# BUSBAR_18650_12S.net
KiCad netlist of a schematic drawn in Altium Designer
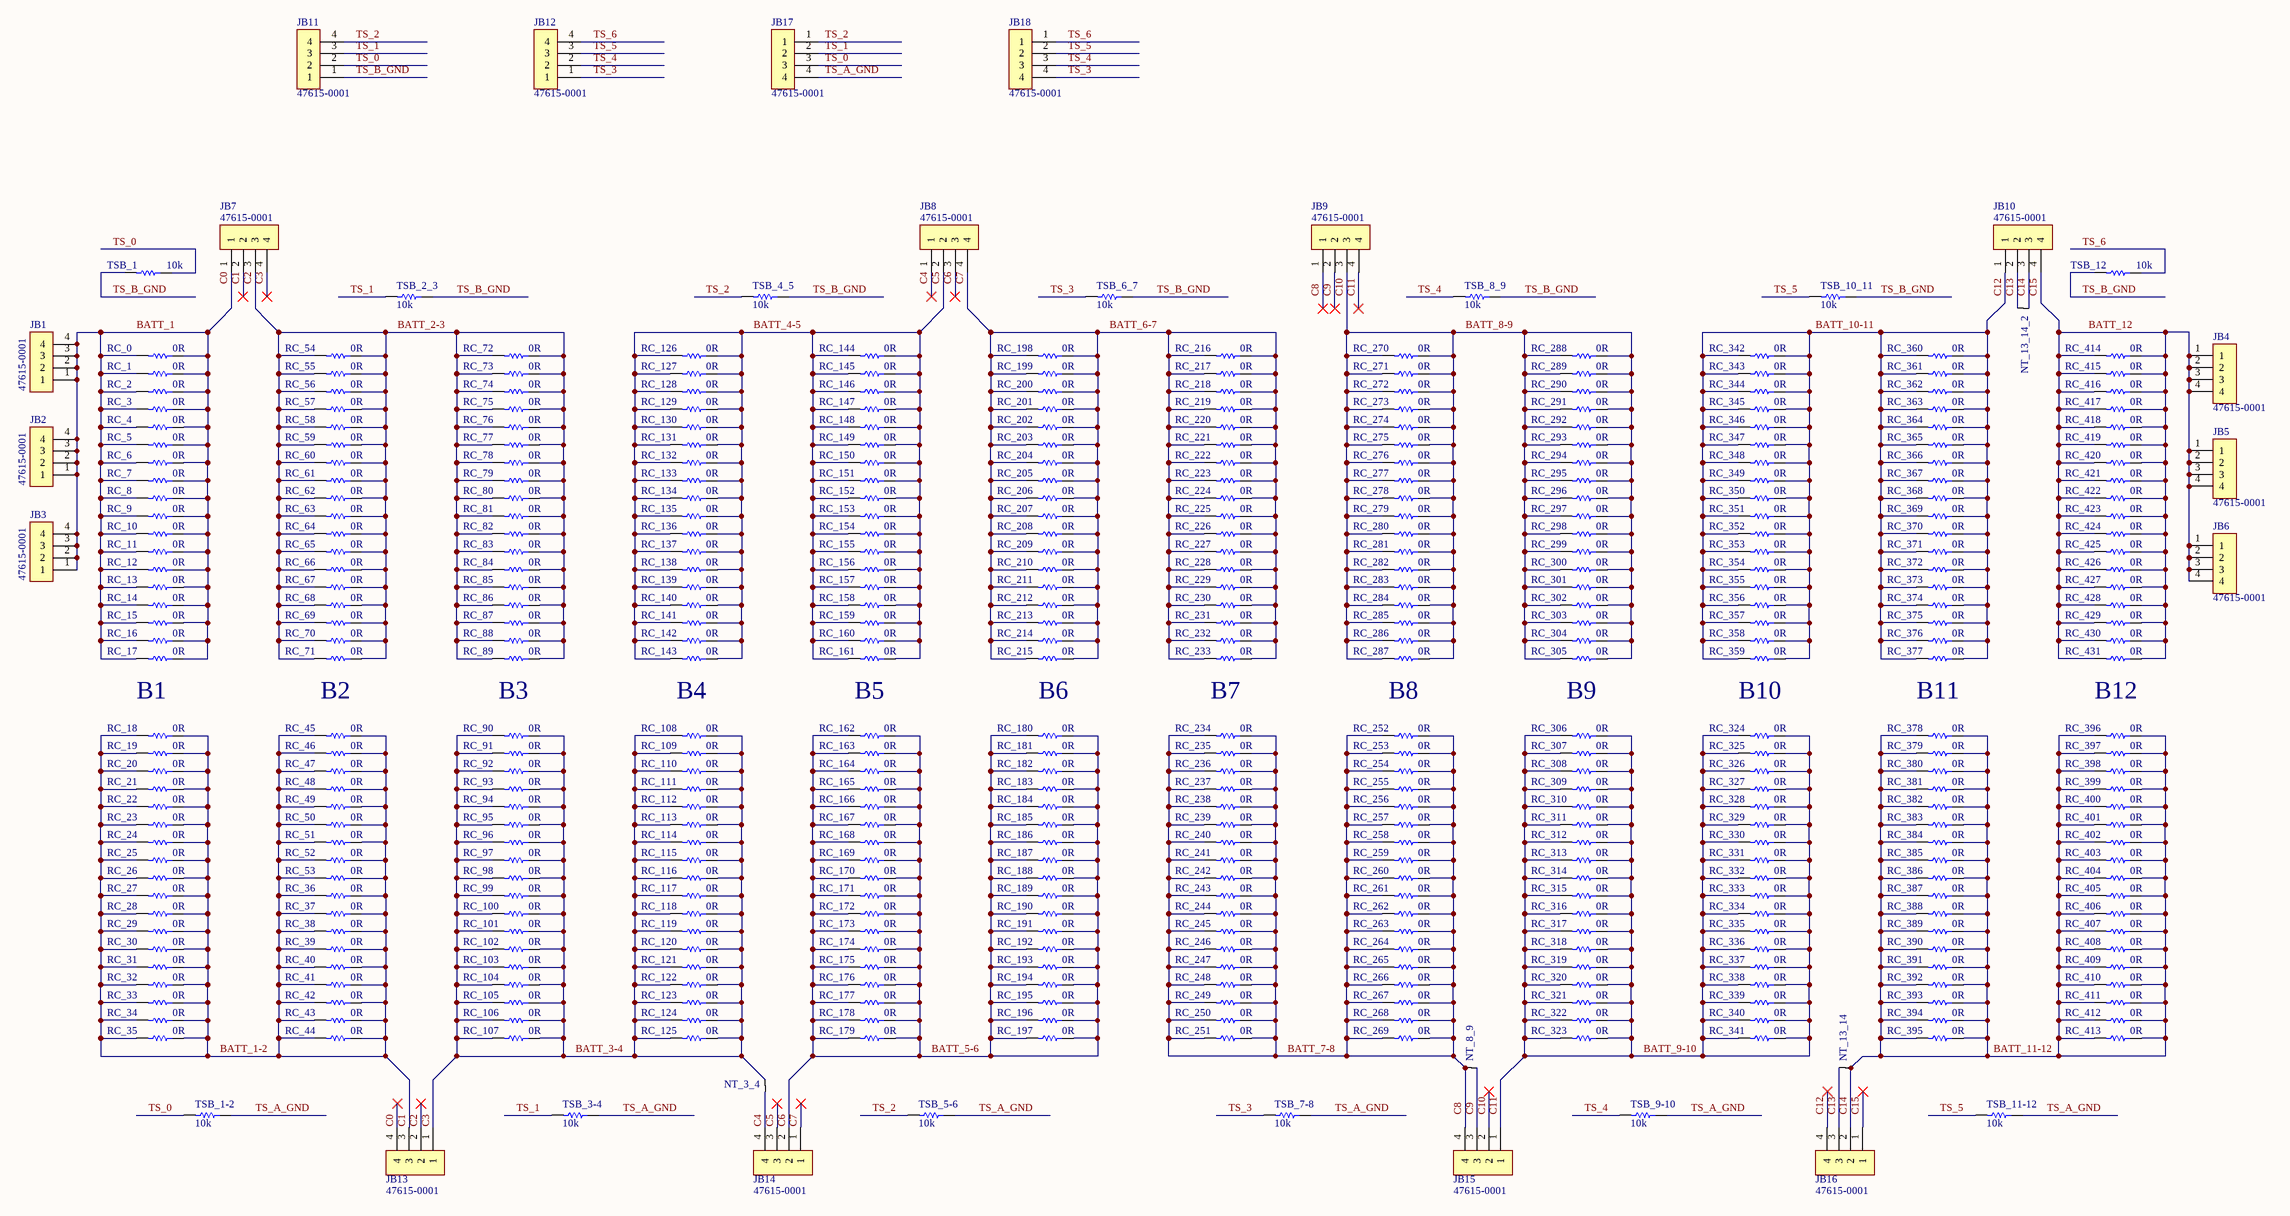
[diagram p0: BUSBAR_18650_12S.SchDoc]

(export (version "E")
  (design (tool "Eeschema 10.0.6"))
  (components
    (comp (ref "JB1")
      (value "47615-0001")
      (footprint "47615-0001")
      (description "Battery Spring x4")
      (libsource (lib "") (part "47615-0001_2"))
    )
    (comp (ref "JB2")
      (value "47615-0001")
      (footprint "47615-0001")
      (description "Battery Spring x4")
      (libsource (lib "") (part "47615-0001_2"))
    )
    (comp (ref "JB3")
      (value "47615-0001")
      (footprint "47615-0001")
      (description "Battery Spring x4")
      (libsource (lib "") (part "47615-0001_2"))
    )
    (comp (ref "JB4")
      (value "47615-0001")
      (footprint "47615-0001")
      (description "Battery Spring x4")
      (libsource (lib "") (part "47615-0001_3"))
    )
    (comp (ref "JB5")
      (value "47615-0001")
      (footprint "47615-0001")
      (description "Battery Spring x4")
      (libsource (lib "") (part "47615-0001_3"))
    )
    (comp (ref "JB6")
      (value "47615-0001")
      (footprint "47615-0001")
      (description "Battery Spring x4")
      (libsource (lib "") (part "47615-0001_3"))
    )
    (comp (ref "JB7")
      (value "47615-0001")
      (footprint "47615-0001")
      (description "Battery Spring x4")
      (libsource (lib "") (part "47615-0001_1"))
    )
    (comp (ref "JB8")
      (value "47615-0001")
      (footprint "47615-0001")
      (description "Battery Spring x4")
      (libsource (lib "") (part "47615-0001_1"))
    )
    (comp (ref "JB9")
      (value "47615-0001")
      (footprint "47615-0001")
      (description "Battery Spring x4")
      (libsource (lib "") (part "47615-0001_1"))
    )
    (comp (ref "JB10")
      (value "47615-0001")
      (footprint "47615-0001")
      (description "Battery Spring x4")
      (libsource (lib "") (part "47615-0001_1"))
    )
    (comp (ref "JB11")
      (value "47615-0001")
      (footprint "47615-0001")
      (description "Battery Spring x4")
      (libsource (lib "") (part "47615-0001_2"))
    )
    (comp (ref "JB12")
      (value "47615-0001")
      (footprint "47615-0001")
      (description "Battery Spring x4")
      (libsource (lib "") (part "47615-0001_2"))
    )
    (comp (ref "JB13")
      (value "47615-0001")
      (footprint "47615-0001")
      (description "Battery Spring x4")
      (libsource (lib "J") (part "47615-0001"))
    )
    (comp (ref "JB14")
      (value "47615-0001")
      (footprint "47615-0001")
      (description "Battery Spring x4")
      (libsource (lib "J") (part "47615-0001"))
    )
    (comp (ref "JB15")
      (value "47615-0001")
      (footprint "47615-0001")
      (description "Battery Spring x4")
      (libsource (lib "J") (part "47615-0001"))
    )
    (comp (ref "JB16")
      (value "47615-0001")
      (footprint "47615-0001")
      (description "Battery Spring x4")
      (libsource (lib "J") (part "47615-0001"))
    )
    (comp (ref "JB17")
      (value "47615-0001")
      (footprint "47615-0001")
      (description "Battery Spring x4")
      (libsource (lib "J") (part "47615-0001"))
    )
    (comp (ref "JB18")
      (value "47615-0001")
      (footprint "47615-0001")
      (description "Battery Spring x4")
      (libsource (lib "J") (part "47615-0001"))
    )
    (comp (ref "NT_3_4")
      (value "0")
      (footprint "NET_TIE")
      (description "R - Net Tie")
      (libsource (lib "JLC_PCB") (part "NET_TIE"))
    )
    (comp (ref "NT_8_9")
      (value "0")
      (footprint "NET_TIE")
      (description "R - Net Tie")
      (libsource (lib "JLC_PCB") (part "NET_TIE"))
    )
    (comp (ref "NT_13_14")
      (value "0")
      (footprint "NET_TIE")
      (description "R - Net Tie")
      (libsource (lib "JLC_PCB") (part "NET_TIE"))
    )
    (comp (ref "NT_13_14_2")
      (value "0")
      (footprint "NET_TIE")
      (description "R - Net Tie")
      (libsource (lib "JLC_PCB") (part "NET_TIE"))
    )
    (comp (ref "RC_0")
      (value "0R")
      (footprint "R_0603")
      (description "R - RESISTOR - SMD - 0R - 1% - 0603")
      (fields (field (name "LCSC PART #") "C21189") (field (name "Comment") "0603WAF0000T5E"))
      (libsource (lib "JLC_PCB") (part "0603WAF0000T5E"))
    )
    (comp (ref "RC_1")
      (value "0R")
      (footprint "R_0603")
      (description "R - RESISTOR - SMD - 0R - 1% - 0603")
      (fields (field (name "LCSC PART #") "C21189") (field (name "Comment") "0603WAF0000T5E"))
      (libsource (lib "JLC_PCB") (part "0603WAF0000T5E"))
    )
    (comp (ref "RC_2")
      (value "0R")
      (footprint "R_0603")
      (description "R - RESISTOR - SMD - 0R - 1% - 0603")
      (fields (field (name "LCSC PART #") "C21189") (field (name "Comment") "0603WAF0000T5E"))
      (libsource (lib "JLC_PCB") (part "0603WAF0000T5E"))
    )
    (comp (ref "RC_3")
      (value "0R")
      (footprint "R_0603")
      (description "R - RESISTOR - SMD - 0R - 1% - 0603")
      (fields (field (name "LCSC PART #") "C21189") (field (name "Comment") "0603WAF0000T5E"))
      (libsource (lib "JLC_PCB") (part "0603WAF0000T5E"))
    )
    (comp (ref "RC_4")
      (value "0R")
      (footprint "R_0603")
      (description "R - RESISTOR - SMD - 0R - 1% - 0603")
      (fields (field (name "LCSC PART #") "C21189") (field (name "Comment") "0603WAF0000T5E"))
      (libsource (lib "JLC_PCB") (part "0603WAF0000T5E"))
    )
    (comp (ref "RC_5")
      (value "0R")
      (footprint "R_0603")
      (description "R - RESISTOR - SMD - 0R - 1% - 0603")
      (fields (field (name "LCSC PART #") "C21189") (field (name "Comment") "0603WAF0000T5E"))
      (libsource (lib "JLC_PCB") (part "0603WAF0000T5E"))
    )
    (comp (ref "RC_6")
      (value "0R")
      (footprint "R_0603")
      (description "R - RESISTOR - SMD - 0R - 1% - 0603")
      (fields (field (name "LCSC PART #") "C21189") (field (name "Comment") "0603WAF0000T5E"))
      (libsource (lib "JLC_PCB") (part "0603WAF0000T5E"))
    )
    (comp (ref "RC_7")
      (value "0R")
      (footprint "R_0603")
      (description "R - RESISTOR - SMD - 0R - 1% - 0603")
      (fields (field (name "LCSC PART #") "C21189") (field (name "Comment") "0603WAF0000T5E"))
      (libsource (lib "JLC_PCB") (part "0603WAF0000T5E"))
    )
    (comp (ref "RC_8")
      (value "0R")
      (footprint "R_0603")
      (description "R - RESISTOR - SMD - 0R - 1% - 0603")
      (fields (field (name "LCSC PART #") "C21189") (field (name "Comment") "0603WAF0000T5E"))
      (libsource (lib "JLC_PCB") (part "0603WAF0000T5E"))
    )
    (comp (ref "RC_9")
      (value "0R")
      (footprint "R_0603")
      (description "R - RESISTOR - SMD - 0R - 1% - 0603")
      (fields (field (name "LCSC PART #") "C21189") (field (name "Comment") "0603WAF0000T5E"))
      (libsource (lib "JLC_PCB") (part "0603WAF0000T5E"))
    )
    (comp (ref "RC_10")
      (value "0R")
      (footprint "R_0603")
      (description "R - RESISTOR - SMD - 0R - 1% - 0603")
      (fields (field (name "LCSC PART #") "C21189") (field (name "Comment") "0603WAF0000T5E"))
      (libsource (lib "JLC_PCB") (part "0603WAF0000T5E"))
    )
    (comp (ref "RC_11")
      (value "0R")
      (footprint "R_0603")
      (description "R - RESISTOR - SMD - 0R - 1% - 0603")
      (fields (field (name "LCSC PART #") "C21189") (field (name "Comment") "0603WAF0000T5E"))
      (libsource (lib "JLC_PCB") (part "0603WAF0000T5E"))
    )
    (comp (ref "RC_12")
      (value "0R")
      (footprint "R_0603")
      (description "R - RESISTOR - SMD - 0R - 1% - 0603")
      (fields (field (name "LCSC PART #") "C21189") (field (name "Comment") "0603WAF0000T5E"))
      (libsource (lib "JLC_PCB") (part "0603WAF0000T5E"))
    )
    (comp (ref "RC_13")
      (value "0R")
      (footprint "R_0603")
      (description "R - RESISTOR - SMD - 0R - 1% - 0603")
      (fields (field (name "LCSC PART #") "C21189") (field (name "Comment") "0603WAF0000T5E"))
      (libsource (lib "JLC_PCB") (part "0603WAF0000T5E"))
    )
    (comp (ref "RC_14")
      (value "0R")
      (footprint "R_0603")
      (description "R - RESISTOR - SMD - 0R - 1% - 0603")
      (fields (field (name "LCSC PART #") "C21189") (field (name "Comment") "0603WAF0000T5E"))
      (libsource (lib "JLC_PCB") (part "0603WAF0000T5E"))
    )
    (comp (ref "RC_15")
      (value "0R")
      (footprint "R_0603")
      (description "R - RESISTOR - SMD - 0R - 1% - 0603")
      (fields (field (name "LCSC PART #") "C21189") (field (name "Comment") "0603WAF0000T5E"))
      (libsource (lib "JLC_PCB") (part "0603WAF0000T5E"))
    )
    (comp (ref "RC_16")
      (value "0R")
      (footprint "R_0603")
      (description "R - RESISTOR - SMD - 0R - 1% - 0603")
      (fields (field (name "LCSC PART #") "C21189") (field (name "Comment") "0603WAF0000T5E"))
      (libsource (lib "JLC_PCB") (part "0603WAF0000T5E"))
    )
    (comp (ref "RC_17")
      (value "0R")
      (footprint "R_0603")
      (description "R - RESISTOR - SMD - 0R - 1% - 0603")
      (fields (field (name "LCSC PART #") "C21189") (field (name "Comment") "0603WAF0000T5E"))
      (libsource (lib "JLC_PCB") (part "0603WAF0000T5E"))
    )
    (comp (ref "RC_18")
      (value "0R")
      (footprint "R_0603")
      (description "R - RESISTOR - SMD - 0R - 1% - 0603")
      (fields (field (name "LCSC PART #") "C21189") (field (name "Comment") "0603WAF0000T5E"))
      (libsource (lib "JLC_PCB") (part "0603WAF0000T5E"))
    )
    (comp (ref "RC_19")
      (value "0R")
      (footprint "R_0603")
      (description "R - RESISTOR - SMD - 0R - 1% - 0603")
      (fields (field (name "LCSC PART #") "C21189") (field (name "Comment") "0603WAF0000T5E"))
      (libsource (lib "JLC_PCB") (part "0603WAF0000T5E"))
    )
    (comp (ref "RC_20")
      (value "0R")
      (footprint "R_0603")
      (description "R - RESISTOR - SMD - 0R - 1% - 0603")
      (fields (field (name "LCSC PART #") "C21189") (field (name "Comment") "0603WAF0000T5E"))
      (libsource (lib "JLC_PCB") (part "0603WAF0000T5E"))
    )
    (comp (ref "RC_21")
      (value "0R")
      (footprint "R_0603")
      (description "R - RESISTOR - SMD - 0R - 1% - 0603")
      (fields (field (name "LCSC PART #") "C21189") (field (name "Comment") "0603WAF0000T5E"))
      (libsource (lib "JLC_PCB") (part "0603WAF0000T5E"))
    )
    (comp (ref "RC_22")
      (value "0R")
      (footprint "R_0603")
      (description "R - RESISTOR - SMD - 0R - 1% - 0603")
      (fields (field (name "LCSC PART #") "C21189") (field (name "Comment") "0603WAF0000T5E"))
      (libsource (lib "JLC_PCB") (part "0603WAF0000T5E"))
    )
    (comp (ref "RC_23")
      (value "0R")
      (footprint "R_0603")
      (description "R - RESISTOR - SMD - 0R - 1% - 0603")
      (fields (field (name "LCSC PART #") "C21189") (field (name "Comment") "0603WAF0000T5E"))
      (libsource (lib "JLC_PCB") (part "0603WAF0000T5E"))
    )
    (comp (ref "RC_24")
      (value "0R")
      (footprint "R_0603")
      (description "R - RESISTOR - SMD - 0R - 1% - 0603")
      (fields (field (name "LCSC PART #") "C21189") (field (name "Comment") "0603WAF0000T5E"))
      (libsource (lib "JLC_PCB") (part "0603WAF0000T5E"))
    )
    (comp (ref "RC_25")
      (value "0R")
      (footprint "R_0603")
      (description "R - RESISTOR - SMD - 0R - 1% - 0603")
      (fields (field (name "LCSC PART #") "C21189") (field (name "Comment") "0603WAF0000T5E"))
      (libsource (lib "JLC_PCB") (part "0603WAF0000T5E"))
    )
    (comp (ref "RC_26")
      (value "0R")
      (footprint "R_0603")
      (description "R - RESISTOR - SMD - 0R - 1% - 0603")
      (fields (field (name "LCSC PART #") "C21189") (field (name "Comment") "0603WAF0000T5E"))
      (libsource (lib "JLC_PCB") (part "0603WAF0000T5E"))
    )
    (comp (ref "RC_27")
      (value "0R")
      (footprint "R_0603")
      (description "R - RESISTOR - SMD - 0R - 1% - 0603")
      (fields (field (name "LCSC PART #") "C21189") (field (name "Comment") "0603WAF0000T5E"))
      (libsource (lib "JLC_PCB") (part "0603WAF0000T5E"))
    )
    (comp (ref "RC_28")
      (value "0R")
      (footprint "R_0603")
      (description "R - RESISTOR - SMD - 0R - 1% - 0603")
      (fields (field (name "LCSC PART #") "C21189") (field (name "Comment") "0603WAF0000T5E"))
      (libsource (lib "JLC_PCB") (part "0603WAF0000T5E"))
    )
    (comp (ref "RC_29")
      (value "0R")
      (footprint "R_0603")
      (description "R - RESISTOR - SMD - 0R - 1% - 0603")
      (fields (field (name "LCSC PART #") "C21189") (field (name "Comment") "0603WAF0000T5E"))
      (libsource (lib "JLC_PCB") (part "0603WAF0000T5E"))
    )
    (comp (ref "RC_30")
      (value "0R")
      (footprint "R_0603")
      (description "R - RESISTOR - SMD - 0R - 1% - 0603")
      (fields (field (name "LCSC PART #") "C21189") (field (name "Comment") "0603WAF0000T5E"))
      (libsource (lib "JLC_PCB") (part "0603WAF0000T5E"))
    )
    (comp (ref "RC_31")
      (value "0R")
      (footprint "R_0603")
      (description "R - RESISTOR - SMD - 0R - 1% - 0603")
      (fields (field (name "LCSC PART #") "C21189") (field (name "Comment") "0603WAF0000T5E"))
      (libsource (lib "JLC_PCB") (part "0603WAF0000T5E"))
    )
    (comp (ref "RC_32")
      (value "0R")
      (footprint "R_0603")
      (description "R - RESISTOR - SMD - 0R - 1% - 0603")
      (fields (field (name "LCSC PART #") "C21189") (field (name "Comment") "0603WAF0000T5E"))
      (libsource (lib "JLC_PCB") (part "0603WAF0000T5E"))
    )
    (comp (ref "RC_33")
      (value "0R")
      (footprint "R_0603")
      (description "R - RESISTOR - SMD - 0R - 1% - 0603")
      (fields (field (name "LCSC PART #") "C21189") (field (name "Comment") "0603WAF0000T5E"))
      (libsource (lib "JLC_PCB") (part "0603WAF0000T5E"))
    )
    (comp (ref "RC_34")
      (value "0R")
      (footprint "R_0603")
      (description "R - RESISTOR - SMD - 0R - 1% - 0603")
      (fields (field (name "LCSC PART #") "C21189") (field (name "Comment") "0603WAF0000T5E"))
      (libsource (lib "JLC_PCB") (part "0603WAF0000T5E"))
    )
    (comp (ref "RC_35")
      (value "0R")
      (footprint "R_0603")
      (description "R - RESISTOR - SMD - 0R - 1% - 0603")
      (fields (field (name "LCSC PART #") "C21189") (field (name "Comment") "0603WAF0000T5E"))
      (libsource (lib "JLC_PCB") (part "0603WAF0000T5E"))
    )
    (comp (ref "RC_36")
      (value "0R")
      (footprint "R_0603")
      (description "R - RESISTOR - SMD - 0R - 1% - 0603")
      (fields (field (name "LCSC PART #") "C21189") (field (name "Comment") "0603WAF0000T5E"))
      (libsource (lib "JLC_PCB") (part "0603WAF0000T5E"))
    )
    (comp (ref "RC_37")
      (value "0R")
      (footprint "R_0603")
      (description "R - RESISTOR - SMD - 0R - 1% - 0603")
      (fields (field (name "LCSC PART #") "C21189") (field (name "Comment") "0603WAF0000T5E"))
      (libsource (lib "JLC_PCB") (part "0603WAF0000T5E"))
    )
    (comp (ref "RC_38")
      (value "0R")
      (footprint "R_0603")
      (description "R - RESISTOR - SMD - 0R - 1% - 0603")
      (fields (field (name "LCSC PART #") "C21189") (field (name "Comment") "0603WAF0000T5E"))
      (libsource (lib "JLC_PCB") (part "0603WAF0000T5E"))
    )
    (comp (ref "RC_39")
      (value "0R")
      (footprint "R_0603")
      (description "R - RESISTOR - SMD - 0R - 1% - 0603")
      (fields (field (name "LCSC PART #") "C21189") (field (name "Comment") "0603WAF0000T5E"))
      (libsource (lib "JLC_PCB") (part "0603WAF0000T5E"))
    )
    (comp (ref "RC_40")
      (value "0R")
      (footprint "R_0603")
      (description "R - RESISTOR - SMD - 0R - 1% - 0603")
      (fields (field (name "LCSC PART #") "C21189") (field (name "Comment") "0603WAF0000T5E"))
      (libsource (lib "JLC_PCB") (part "0603WAF0000T5E"))
    )
    (comp (ref "RC_41")
      (value "0R")
      (footprint "R_0603")
      (description "R - RESISTOR - SMD - 0R - 1% - 0603")
      (fields (field (name "LCSC PART #") "C21189") (field (name "Comment") "0603WAF0000T5E"))
      (libsource (lib "JLC_PCB") (part "0603WAF0000T5E"))
    )
    (comp (ref "RC_42")
      (value "0R")
      (footprint "R_0603")
      (description "R - RESISTOR - SMD - 0R - 1% - 0603")
      (fields (field (name "LCSC PART #") "C21189") (field (name "Comment") "0603WAF0000T5E"))
      (libsource (lib "JLC_PCB") (part "0603WAF0000T5E"))
    )
    (comp (ref "RC_43")
      (value "0R")
      (footprint "R_0603")
      (description "R - RESISTOR - SMD - 0R - 1% - 0603")
      (fields (field (name "LCSC PART #") "C21189") (field (name "Comment") "0603WAF0000T5E"))
      (libsource (lib "JLC_PCB") (part "0603WAF0000T5E"))
    )
    (comp (ref "RC_44")
      (value "0R")
      (footprint "R_0603")
      (description "R - RESISTOR - SMD - 0R - 1% - 0603")
      (fields (field (name "LCSC PART #") "C21189") (field (name "Comment") "0603WAF0000T5E"))
      (libsource (lib "JLC_PCB") (part "0603WAF0000T5E"))
    )
    (comp (ref "RC_45")
      (value "0R")
      (footprint "R_0603")
      (description "R - RESISTOR - SMD - 0R - 1% - 0603")
      (fields (field (name "LCSC PART #") "C21189") (field (name "Comment") "0603WAF0000T5E"))
      (libsource (lib "JLC_PCB") (part "0603WAF0000T5E"))
    )
    (comp (ref "RC_46")
      (value "0R")
      (footprint "R_0603")
      (description "R - RESISTOR - SMD - 0R - 1% - 0603")
      (fields (field (name "LCSC PART #") "C21189") (field (name "Comment") "0603WAF0000T5E"))
      (libsource (lib "JLC_PCB") (part "0603WAF0000T5E"))
    )
    (comp (ref "RC_47")
      (value "0R")
      (footprint "R_0603")
      (description "R - RESISTOR - SMD - 0R - 1% - 0603")
      (fields (field (name "LCSC PART #") "C21189") (field (name "Comment") "0603WAF0000T5E"))
      (libsource (lib "JLC_PCB") (part "0603WAF0000T5E"))
    )
    (comp (ref "RC_48")
      (value "0R")
      (footprint "R_0603")
      (description "R - RESISTOR - SMD - 0R - 1% - 0603")
      (fields (field (name "LCSC PART #") "C21189") (field (name "Comment") "0603WAF0000T5E"))
      (libsource (lib "JLC_PCB") (part "0603WAF0000T5E"))
    )
    (comp (ref "RC_49")
      (value "0R")
      (footprint "R_0603")
      (description "R - RESISTOR - SMD - 0R - 1% - 0603")
      (fields (field (name "LCSC PART #") "C21189") (field (name "Comment") "0603WAF0000T5E"))
      (libsource (lib "JLC_PCB") (part "0603WAF0000T5E"))
    )
    (comp (ref "RC_50")
      (value "0R")
      (footprint "R_0603")
      (description "R - RESISTOR - SMD - 0R - 1% - 0603")
      (fields (field (name "LCSC PART #") "C21189") (field (name "Comment") "0603WAF0000T5E"))
      (libsource (lib "JLC_PCB") (part "0603WAF0000T5E"))
    )
    (comp (ref "RC_51")
      (value "0R")
      (footprint "R_0603")
      (description "R - RESISTOR - SMD - 0R - 1% - 0603")
      (fields (field (name "LCSC PART #") "C21189") (field (name "Comment") "0603WAF0000T5E"))
      (libsource (lib "JLC_PCB") (part "0603WAF0000T5E"))
    )
    (comp (ref "RC_52")
      (value "0R")
      (footprint "R_0603")
      (description "R - RESISTOR - SMD - 0R - 1% - 0603")
      (fields (field (name "LCSC PART #") "C21189") (field (name "Comment") "0603WAF0000T5E"))
      (libsource (lib "JLC_PCB") (part "0603WAF0000T5E"))
    )
    (comp (ref "RC_53")
      (value "0R")
      (footprint "R_0603")
      (description "R - RESISTOR - SMD - 0R - 1% - 0603")
      (fields (field (name "LCSC PART #") "C21189") (field (name "Comment") "0603WAF0000T5E"))
      (libsource (lib "JLC_PCB") (part "0603WAF0000T5E"))
    )
    (comp (ref "RC_54")
      (value "0R")
      (footprint "R_0603")
      (description "R - RESISTOR - SMD - 0R - 1% - 0603")
      (fields (field (name "LCSC PART #") "C21189") (field (name "Comment") "0603WAF0000T5E"))
      (libsource (lib "JLC_PCB") (part "0603WAF0000T5E"))
    )
    (comp (ref "RC_55")
      (value "0R")
      (footprint "R_0603")
      (description "R - RESISTOR - SMD - 0R - 1% - 0603")
      (fields (field (name "LCSC PART #") "C21189") (field (name "Comment") "0603WAF0000T5E"))
      (libsource (lib "JLC_PCB") (part "0603WAF0000T5E"))
    )
    (comp (ref "RC_56")
      (value "0R")
      (footprint "R_0603")
      (description "R - RESISTOR - SMD - 0R - 1% - 0603")
      (fields (field (name "LCSC PART #") "C21189") (field (name "Comment") "0603WAF0000T5E"))
      (libsource (lib "JLC_PCB") (part "0603WAF0000T5E"))
    )
    (comp (ref "RC_57")
      (value "0R")
      (footprint "R_0603")
      (description "R - RESISTOR - SMD - 0R - 1% - 0603")
      (fields (field (name "LCSC PART #") "C21189") (field (name "Comment") "0603WAF0000T5E"))
      (libsource (lib "JLC_PCB") (part "0603WAF0000T5E"))
    )
    (comp (ref "RC_58")
      (value "0R")
      (footprint "R_0603")
      (description "R - RESISTOR - SMD - 0R - 1% - 0603")
      (fields (field (name "LCSC PART #") "C21189") (field (name "Comment") "0603WAF0000T5E"))
      (libsource (lib "JLC_PCB") (part "0603WAF0000T5E"))
    )
    (comp (ref "RC_59")
      (value "0R")
      (footprint "R_0603")
      (description "R - RESISTOR - SMD - 0R - 1% - 0603")
      (fields (field (name "LCSC PART #") "C21189") (field (name "Comment") "0603WAF0000T5E"))
      (libsource (lib "JLC_PCB") (part "0603WAF0000T5E"))
    )
    (comp (ref "RC_60")
      (value "0R")
      (footprint "R_0603")
      (description "R - RESISTOR - SMD - 0R - 1% - 0603")
      (fields (field (name "LCSC PART #") "C21189") (field (name "Comment") "0603WAF0000T5E"))
      (libsource (lib "JLC_PCB") (part "0603WAF0000T5E"))
    )
    (comp (ref "RC_61")
      (value "0R")
      (footprint "R_0603")
      (description "R - RESISTOR - SMD - 0R - 1% - 0603")
      (fields (field (name "LCSC PART #") "C21189") (field (name "Comment") "0603WAF0000T5E"))
      (libsource (lib "JLC_PCB") (part "0603WAF0000T5E"))
    )
    (comp (ref "RC_62")
      (value "0R")
      (footprint "R_0603")
      (description "R - RESISTOR - SMD - 0R - 1% - 0603")
      (fields (field (name "LCSC PART #") "C21189") (field (name "Comment") "0603WAF0000T5E"))
      (libsource (lib "JLC_PCB") (part "0603WAF0000T5E"))
    )
    (comp (ref "RC_63")
      (value "0R")
      (footprint "R_0603")
      (description "R - RESISTOR - SMD - 0R - 1% - 0603")
      (fields (field (name "LCSC PART #") "C21189") (field (name "Comment") "0603WAF0000T5E"))
      (libsource (lib "JLC_PCB") (part "0603WAF0000T5E"))
    )
    (comp (ref "RC_64")
      (value "0R")
      (footprint "R_0603")
      (description "R - RESISTOR - SMD - 0R - 1% - 0603")
      (fields (field (name "LCSC PART #") "C21189") (field (name "Comment") "0603WAF0000T5E"))
      (libsource (lib "JLC_PCB") (part "0603WAF0000T5E"))
    )
    (comp (ref "RC_65")
      (value "0R")
      (footprint "R_0603")
      (description "R - RESISTOR - SMD - 0R - 1% - 0603")
      (fields (field (name "LCSC PART #") "C21189") (field (name "Comment") "0603WAF0000T5E"))
      (libsource (lib "JLC_PCB") (part "0603WAF0000T5E"))
    )
    (comp (ref "RC_66")
      (value "0R")
      (footprint "R_0603")
      (description "R - RESISTOR - SMD - 0R - 1% - 0603")
      (fields (field (name "LCSC PART #") "C21189") (field (name "Comment") "0603WAF0000T5E"))
      (libsource (lib "JLC_PCB") (part "0603WAF0000T5E"))
    )
    (comp (ref "RC_67")
      (value "0R")
      (footprint "R_0603")
      (description "R - RESISTOR - SMD - 0R - 1% - 0603")
      (fields (field (name "LCSC PART #") "C21189") (field (name "Comment") "0603WAF0000T5E"))
      (libsource (lib "JLC_PCB") (part "0603WAF0000T5E"))
    )
    (comp (ref "RC_68")
      (value "0R")
      (footprint "R_0603")
      (description "R - RESISTOR - SMD - 0R - 1% - 0603")
      (fields (field (name "LCSC PART #") "C21189") (field (name "Comment") "0603WAF0000T5E"))
      (libsource (lib "JLC_PCB") (part "0603WAF0000T5E"))
    )
    (comp (ref "RC_69")
      (value "0R")
      (footprint "R_0603")
      (description "R - RESISTOR - SMD - 0R - 1% - 0603")
      (fields (field (name "LCSC PART #") "C21189") (field (name "Comment") "0603WAF0000T5E"))
      (libsource (lib "JLC_PCB") (part "0603WAF0000T5E"))
    )
    (comp (ref "RC_70")
      (value "0R")
      (footprint "R_0603")
      (description "R - RESISTOR - SMD - 0R - 1% - 0603")
      (fields (field (name "LCSC PART #") "C21189") (field (name "Comment") "0603WAF0000T5E"))
      (libsource (lib "JLC_PCB") (part "0603WAF0000T5E"))
    )
    (comp (ref "RC_71")
      (value "0R")
      (footprint "R_0603")
      (description "R - RESISTOR - SMD - 0R - 1% - 0603")
      (fields (field (name "LCSC PART #") "C21189") (field (name "Comment") "0603WAF0000T5E"))
      (libsource (lib "JLC_PCB") (part "0603WAF0000T5E"))
    )
    (comp (ref "RC_72")
      (value "0R")
      (footprint "R_0603")
      (description "R - RESISTOR - SMD - 0R - 1% - 0603")
      (fields (field (name "LCSC PART #") "C21189") (field (name "Comment") "0603WAF0000T5E"))
      (libsource (lib "JLC_PCB") (part "0603WAF0000T5E"))
    )
    (comp (ref "RC_73")
      (value "0R")
      (footprint "R_0603")
      (description "R - RESISTOR - SMD - 0R - 1% - 0603")
      (fields (field (name "LCSC PART #") "C21189") (field (name "Comment") "0603WAF0000T5E"))
      (libsource (lib "JLC_PCB") (part "0603WAF0000T5E"))
    )
    (comp (ref "RC_74")
      (value "0R")
      (footprint "R_0603")
      (description "R - RESISTOR - SMD - 0R - 1% - 0603")
      (fields (field (name "LCSC PART #") "C21189") (field (name "Comment") "0603WAF0000T5E"))
      (libsource (lib "JLC_PCB") (part "0603WAF0000T5E"))
    )
    (comp (ref "RC_75")
      (value "0R")
      (footprint "R_0603")
      (description "R - RESISTOR - SMD - 0R - 1% - 0603")
      (fields (field (name "LCSC PART #") "C21189") (field (name "Comment") "0603WAF0000T5E"))
      (libsource (lib "JLC_PCB") (part "0603WAF0000T5E"))
    )
    (comp (ref "RC_76")
      (value "0R")
      (footprint "R_0603")
      (description "R - RESISTOR - SMD - 0R - 1% - 0603")
      (fields (field (name "LCSC PART #") "C21189") (field (name "Comment") "0603WAF0000T5E"))
      (libsource (lib "JLC_PCB") (part "0603WAF0000T5E"))
    )
    (comp (ref "RC_77")
      (value "0R")
      (footprint "R_0603")
      (description "R - RESISTOR - SMD - 0R - 1% - 0603")
      (fields (field (name "LCSC PART #") "C21189") (field (name "Comment") "0603WAF0000T5E"))
      (libsource (lib "JLC_PCB") (part "0603WAF0000T5E"))
    )
    (comp (ref "RC_78")
      (value "0R")
      (footprint "R_0603")
      (description "R - RESISTOR - SMD - 0R - 1% - 0603")
      (fields (field (name "LCSC PART #") "C21189") (field (name "Comment") "0603WAF0000T5E"))
      (libsource (lib "JLC_PCB") (part "0603WAF0000T5E"))
    )
    (comp (ref "RC_79")
      (value "0R")
      (footprint "R_0603")
      (description "R - RESISTOR - SMD - 0R - 1% - 0603")
      (fields (field (name "LCSC PART #") "C21189") (field (name "Comment") "0603WAF0000T5E"))
      (libsource (lib "JLC_PCB") (part "0603WAF0000T5E"))
    )
    (comp (ref "RC_80")
      (value "0R")
      (footprint "R_0603")
      (description "R - RESISTOR - SMD - 0R - 1% - 0603")
      (fields (field (name "LCSC PART #") "C21189") (field (name "Comment") "0603WAF0000T5E"))
      (libsource (lib "JLC_PCB") (part "0603WAF0000T5E"))
    )
    (comp (ref "RC_81")
      (value "0R")
      (footprint "R_0603")
      (description "R - RESISTOR - SMD - 0R - 1% - 0603")
      (fields (field (name "LCSC PART #") "C21189") (field (name "Comment") "0603WAF0000T5E"))
      (libsource (lib "JLC_PCB") (part "0603WAF0000T5E"))
    )
    (comp (ref "RC_82")
      (value "0R")
      (footprint "R_0603")
      (description "R - RESISTOR - SMD - 0R - 1% - 0603")
      (fields (field (name "LCSC PART #") "C21189") (field (name "Comment") "0603WAF0000T5E"))
      (libsource (lib "JLC_PCB") (part "0603WAF0000T5E"))
    )
    (comp (ref "RC_83")
      (value "0R")
      (footprint "R_0603")
      (description "R - RESISTOR - SMD - 0R - 1% - 0603")
      (fields (field (name "LCSC PART #") "C21189") (field (name "Comment") "0603WAF0000T5E"))
      (libsource (lib "JLC_PCB") (part "0603WAF0000T5E"))
    )
    (comp (ref "RC_84")
      (value "0R")
      (footprint "R_0603")
      (description "R - RESISTOR - SMD - 0R - 1% - 0603")
      (fields (field (name "LCSC PART #") "C21189") (field (name "Comment") "0603WAF0000T5E"))
      (libsource (lib "JLC_PCB") (part "0603WAF0000T5E"))
    )
    (comp (ref "RC_85")
      (value "0R")
      (footprint "R_0603")
      (description "R - RESISTOR - SMD - 0R - 1% - 0603")
      (fields (field (name "LCSC PART #") "C21189") (field (name "Comment") "0603WAF0000T5E"))
      (libsource (lib "JLC_PCB") (part "0603WAF0000T5E"))
    )
    (comp (ref "RC_86")
      (value "0R")
      (footprint "R_0603")
      (description "R - RESISTOR - SMD - 0R - 1% - 0603")
      (fields (field (name "LCSC PART #") "C21189") (field (name "Comment") "0603WAF0000T5E"))
      (libsource (lib "JLC_PCB") (part "0603WAF0000T5E"))
    )
    (comp (ref "RC_87")
      (value "0R")
      (footprint "R_0603")
      (description "R - RESISTOR - SMD - 0R - 1% - 0603")
      (fields (field (name "LCSC PART #") "C21189") (field (name "Comment") "0603WAF0000T5E"))
      (libsource (lib "JLC_PCB") (part "0603WAF0000T5E"))
    )
    (comp (ref "RC_88")
      (value "0R")
      (footprint "R_0603")
      (description "R - RESISTOR - SMD - 0R - 1% - 0603")
      (fields (field (name "LCSC PART #") "C21189") (field (name "Comment") "0603WAF0000T5E"))
      (libsource (lib "JLC_PCB") (part "0603WAF0000T5E"))
    )
    (comp (ref "RC_89")
      (value "0R")
      (footprint "R_0603")
      (description "R - RESISTOR - SMD - 0R - 1% - 0603")
      (fields (field (name "LCSC PART #") "C21189") (field (name "Comment") "0603WAF0000T5E"))
      (libsource (lib "JLC_PCB") (part "0603WAF0000T5E"))
    )
    (comp (ref "RC_90")
      (value "0R")
      (footprint "R_0603")
      (description "R - RESISTOR - SMD - 0R - 1% - 0603")
      (fields (field (name "LCSC PART #") "C21189") (field (name "Comment") "0603WAF0000T5E"))
      (libsource (lib "JLC_PCB") (part "0603WAF0000T5E"))
    )
    (comp (ref "RC_91")
      (value "0R")
      (footprint "R_0603")
      (description "R - RESISTOR - SMD - 0R - 1% - 0603")
      (fields (field (name "LCSC PART #") "C21189") (field (name "Comment") "0603WAF0000T5E"))
      (libsource (lib "JLC_PCB") (part "0603WAF0000T5E"))
    )
    (comp (ref "RC_92")
      (value "0R")
      (footprint "R_0603")
      (description "R - RESISTOR - SMD - 0R - 1% - 0603")
      (fields (field (name "LCSC PART #") "C21189") (field (name "Comment") "0603WAF0000T5E"))
      (libsource (lib "JLC_PCB") (part "0603WAF0000T5E"))
    )
    (comp (ref "RC_93")
      (value "0R")
      (footprint "R_0603")
      (description "R - RESISTOR - SMD - 0R - 1% - 0603")
      (fields (field (name "LCSC PART #") "C21189") (field (name "Comment") "0603WAF0000T5E"))
      (libsource (lib "JLC_PCB") (part "0603WAF0000T5E"))
    )
    (comp (ref "RC_94")
      (value "0R")
      (footprint "R_0603")
      (description "R - RESISTOR - SMD - 0R - 1% - 0603")
      (fields (field (name "LCSC PART #") "C21189") (field (name "Comment") "0603WAF0000T5E"))
      (libsource (lib "JLC_PCB") (part "0603WAF0000T5E"))
    )
    (comp (ref "RC_95")
      (value "0R")
      (footprint "R_0603")
      (description "R - RESISTOR - SMD - 0R - 1% - 0603")
      (fields (field (name "LCSC PART #") "C21189") (field (name "Comment") "0603WAF0000T5E"))
      (libsource (lib "JLC_PCB") (part "0603WAF0000T5E"))
    )
    (comp (ref "RC_96")
      (value "0R")
      (footprint "R_0603")
      (description "R - RESISTOR - SMD - 0R - 1% - 0603")
      (fields (field (name "LCSC PART #") "C21189") (field (name "Comment") "0603WAF0000T5E"))
      (libsource (lib "JLC_PCB") (part "0603WAF0000T5E"))
    )
    (comp (ref "RC_97")
      (value "0R")
      (footprint "R_0603")
      (description "R - RESISTOR - SMD - 0R - 1% - 0603")
      (fields (field (name "LCSC PART #") "C21189") (field (name "Comment") "0603WAF0000T5E"))
      (libsource (lib "JLC_PCB") (part "0603WAF0000T5E"))
    )
    (comp (ref "RC_98")
      (value "0R")
      (footprint "R_0603")
      (description "R - RESISTOR - SMD - 0R - 1% - 0603")
      (fields (field (name "LCSC PART #") "C21189") (field (name "Comment") "0603WAF0000T5E"))
      (libsource (lib "JLC_PCB") (part "0603WAF0000T5E"))
    )
    (comp (ref "RC_99")
      (value "0R")
      (footprint "R_0603")
      (description "R - RESISTOR - SMD - 0R - 1% - 0603")
      (fields (field (name "LCSC PART #") "C21189") (field (name "Comment") "0603WAF0000T5E"))
      (libsource (lib "JLC_PCB") (part "0603WAF0000T5E"))
    )
    (comp (ref "RC_100")
      (value "0R")
      (footprint "R_0603")
      (description "R - RESISTOR - SMD - 0R - 1% - 0603")
      (fields (field (name "LCSC PART #") "C21189") (field (name "Comment") "0603WAF0000T5E"))
      (libsource (lib "JLC_PCB") (part "0603WAF0000T5E"))
    )
    (comp (ref "RC_101")
      (value "0R")
      (footprint "R_0603")
      (description "R - RESISTOR - SMD - 0R - 1% - 0603")
      (fields (field (name "LCSC PART #") "C21189") (field (name "Comment") "0603WAF0000T5E"))
      (libsource (lib "JLC_PCB") (part "0603WAF0000T5E"))
    )
    (comp (ref "RC_102")
      (value "0R")
      (footprint "R_0603")
      (description "R - RESISTOR - SMD - 0R - 1% - 0603")
      (fields (field (name "LCSC PART #") "C21189") (field (name "Comment") "0603WAF0000T5E"))
      (libsource (lib "JLC_PCB") (part "0603WAF0000T5E"))
    )
    (comp (ref "RC_103")
      (value "0R")
      (footprint "R_0603")
      (description "R - RESISTOR - SMD - 0R - 1% - 0603")
      (fields (field (name "LCSC PART #") "C21189") (field (name "Comment") "0603WAF0000T5E"))
      (libsource (lib "JLC_PCB") (part "0603WAF0000T5E"))
    )
    (comp (ref "RC_104")
      (value "0R")
      (footprint "R_0603")
      (description "R - RESISTOR - SMD - 0R - 1% - 0603")
      (fields (field (name "LCSC PART #") "C21189") (field (name "Comment") "0603WAF0000T5E"))
      (libsource (lib "JLC_PCB") (part "0603WAF0000T5E"))
    )
    (comp (ref "RC_105")
      (value "0R")
      (footprint "R_0603")
      (description "R - RESISTOR - SMD - 0R - 1% - 0603")
      (fields (field (name "LCSC PART #") "C21189") (field (name "Comment") "0603WAF0000T5E"))
      (libsource (lib "JLC_PCB") (part "0603WAF0000T5E"))
    )
    (comp (ref "RC_106")
      (value "0R")
      (footprint "R_0603")
      (description "R - RESISTOR - SMD - 0R - 1% - 0603")
      (fields (field (name "LCSC PART #") "C21189") (field (name "Comment") "0603WAF0000T5E"))
      (libsource (lib "JLC_PCB") (part "0603WAF0000T5E"))
    )
    (comp (ref "RC_107")
      (value "0R")
      (footprint "R_0603")
      (description "R - RESISTOR - SMD - 0R - 1% - 0603")
      (fields (field (name "LCSC PART #") "C21189") (field (name "Comment") "0603WAF0000T5E"))
      (libsource (lib "JLC_PCB") (part "0603WAF0000T5E"))
    )
    (comp (ref "RC_108")
      (value "0R")
      (footprint "R_0603")
      (description "R - RESISTOR - SMD - 0R - 1% - 0603")
      (fields (field (name "LCSC PART #") "C21189") (field (name "Comment") "0603WAF0000T5E"))
      (libsource (lib "JLC_PCB") (part "0603WAF0000T5E"))
    )
    (comp (ref "RC_109")
      (value "0R")
      (footprint "R_0603")
      (description "R - RESISTOR - SMD - 0R - 1% - 0603")
      (fields (field (name "LCSC PART #") "C21189") (field (name "Comment") "0603WAF0000T5E"))
      (libsource (lib "JLC_PCB") (part "0603WAF0000T5E"))
    )
    (comp (ref "RC_110")
      (value "0R")
      (footprint "R_0603")
      (description "R - RESISTOR - SMD - 0R - 1% - 0603")
      (fields (field (name "LCSC PART #") "C21189") (field (name "Comment") "0603WAF0000T5E"))
      (libsource (lib "JLC_PCB") (part "0603WAF0000T5E"))
    )
    (comp (ref "RC_111")
      (value "0R")
      (footprint "R_0603")
      (description "R - RESISTOR - SMD - 0R - 1% - 0603")
      (fields (field (name "LCSC PART #") "C21189") (field (name "Comment") "0603WAF0000T5E"))
      (libsource (lib "JLC_PCB") (part "0603WAF0000T5E"))
    )
    (comp (ref "RC_112")
      (value "0R")
      (footprint "R_0603")
      (description "R - RESISTOR - SMD - 0R - 1% - 0603")
      (fields (field (name "LCSC PART #") "C21189") (field (name "Comment") "0603WAF0000T5E"))
      (libsource (lib "JLC_PCB") (part "0603WAF0000T5E"))
    )
    (comp (ref "RC_113")
      (value "0R")
      (footprint "R_0603")
      (description "R - RESISTOR - SMD - 0R - 1% - 0603")
      (fields (field (name "LCSC PART #") "C21189") (field (name "Comment") "0603WAF0000T5E"))
      (libsource (lib "JLC_PCB") (part "0603WAF0000T5E"))
    )
    (comp (ref "RC_114")
      (value "0R")
      (footprint "R_0603")
      (description "R - RESISTOR - SMD - 0R - 1% - 0603")
      (fields (field (name "LCSC PART #") "C21189") (field (name "Comment") "0603WAF0000T5E"))
      (libsource (lib "JLC_PCB") (part "0603WAF0000T5E"))
    )
    (comp (ref "RC_115")
      (value "0R")
      (footprint "R_0603")
      (description "R - RESISTOR - SMD - 0R - 1% - 0603")
      (fields (field (name "LCSC PART #") "C21189") (field (name "Comment") "0603WAF0000T5E"))
      (libsource (lib "JLC_PCB") (part "0603WAF0000T5E"))
    )
    (comp (ref "RC_116")
      (value "0R")
      (footprint "R_0603")
      (description "R - RESISTOR - SMD - 0R - 1% - 0603")
      (fields (field (name "LCSC PART #") "C21189") (field (name "Comment") "0603WAF0000T5E"))
      (libsource (lib "JLC_PCB") (part "0603WAF0000T5E"))
    )
    (comp (ref "RC_117")
      (value "0R")
      (footprint "R_0603")
      (description "R - RESISTOR - SMD - 0R - 1% - 0603")
      (fields (field (name "LCSC PART #") "C21189") (field (name "Comment") "0603WAF0000T5E"))
      (libsource (lib "JLC_PCB") (part "0603WAF0000T5E"))
    )
    (comp (ref "RC_118")
      (value "0R")
      (footprint "R_0603")
      (description "R - RESISTOR - SMD - 0R - 1% - 0603")
      (fields (field (name "LCSC PART #") "C21189") (field (name "Comment") "0603WAF0000T5E"))
      (libsource (lib "JLC_PCB") (part "0603WAF0000T5E"))
    )
    (comp (ref "RC_119")
      (value "0R")
      (footprint "R_0603")
      (description "R - RESISTOR - SMD - 0R - 1% - 0603")
      (fields (field (name "LCSC PART #") "C21189") (field (name "Comment") "0603WAF0000T5E"))
      (libsource (lib "JLC_PCB") (part "0603WAF0000T5E"))
    )
    (comp (ref "RC_120")
      (value "0R")
      (footprint "R_0603")
      (description "R - RESISTOR - SMD - 0R - 1% - 0603")
      (fields (field (name "LCSC PART #") "C21189") (field (name "Comment") "0603WAF0000T5E"))
      (libsource (lib "JLC_PCB") (part "0603WAF0000T5E"))
    )
    (comp (ref "RC_121")
      (value "0R")
      (footprint "R_0603")
      (description "R - RESISTOR - SMD - 0R - 1% - 0603")
      (fields (field (name "LCSC PART #") "C21189") (field (name "Comment") "0603WAF0000T5E"))
      (libsource (lib "JLC_PCB") (part "0603WAF0000T5E"))
    )
    (comp (ref "RC_122")
      (value "0R")
      (footprint "R_0603")
      (description "R - RESISTOR - SMD - 0R - 1% - 0603")
      (fields (field (name "LCSC PART #") "C21189") (field (name "Comment") "0603WAF0000T5E"))
      (libsource (lib "JLC_PCB") (part "0603WAF0000T5E"))
    )
    (comp (ref "RC_123")
      (value "0R")
      (footprint "R_0603")
      (description "R - RESISTOR - SMD - 0R - 1% - 0603")
      (fields (field (name "LCSC PART #") "C21189") (field (name "Comment") "0603WAF0000T5E"))
      (libsource (lib "JLC_PCB") (part "0603WAF0000T5E"))
    )
    (comp (ref "RC_124")
      (value "0R")
      (footprint "R_0603")
      (description "R - RESISTOR - SMD - 0R - 1% - 0603")
      (fields (field (name "LCSC PART #") "C21189") (field (name "Comment") "0603WAF0000T5E"))
      (libsource (lib "JLC_PCB") (part "0603WAF0000T5E"))
    )
    (comp (ref "RC_125")
      (value "0R")
      (footprint "R_0603")
      (description "R - RESISTOR - SMD - 0R - 1% - 0603")
      (fields (field (name "LCSC PART #") "C21189") (field (name "Comment") "0603WAF0000T5E"))
      (libsource (lib "JLC_PCB") (part "0603WAF0000T5E"))
    )
    (comp (ref "RC_126")
      (value "0R")
      (footprint "R_0603")
      (description "R - RESISTOR - SMD - 0R - 1% - 0603")
      (fields (field (name "LCSC PART #") "C21189") (field (name "Comment") "0603WAF0000T5E"))
      (libsource (lib "JLC_PCB") (part "0603WAF0000T5E"))
    )
    (comp (ref "RC_127")
      (value "0R")
      (footprint "R_0603")
      (description "R - RESISTOR - SMD - 0R - 1% - 0603")
      (fields (field (name "LCSC PART #") "C21189") (field (name "Comment") "0603WAF0000T5E"))
      (libsource (lib "JLC_PCB") (part "0603WAF0000T5E"))
    )
    (comp (ref "RC_128")
      (value "0R")
      (footprint "R_0603")
      (description "R - RESISTOR - SMD - 0R - 1% - 0603")
      (fields (field (name "LCSC PART #") "C21189") (field (name "Comment") "0603WAF0000T5E"))
      (libsource (lib "JLC_PCB") (part "0603WAF0000T5E"))
    )
    (comp (ref "RC_129")
      (value "0R")
      (footprint "R_0603")
      (description "R - RESISTOR - SMD - 0R - 1% - 0603")
      (fields (field (name "LCSC PART #") "C21189") (field (name "Comment") "0603WAF0000T5E"))
      (libsource (lib "JLC_PCB") (part "0603WAF0000T5E"))
    )
    (comp (ref "RC_130")
      (value "0R")
      (footprint "R_0603")
      (description "R - RESISTOR - SMD - 0R - 1% - 0603")
      (fields (field (name "LCSC PART #") "C21189") (field (name "Comment") "0603WAF0000T5E"))
      (libsource (lib "JLC_PCB") (part "0603WAF0000T5E"))
    )
    (comp (ref "RC_131")
      (value "0R")
      (footprint "R_0603")
      (description "R - RESISTOR - SMD - 0R - 1% - 0603")
      (fields (field (name "LCSC PART #") "C21189") (field (name "Comment") "0603WAF0000T5E"))
      (libsource (lib "JLC_PCB") (part "0603WAF0000T5E"))
    )
    (comp (ref "RC_132")
      (value "0R")
      (footprint "R_0603")
      (description "R - RESISTOR - SMD - 0R - 1% - 0603")
      (fields (field (name "LCSC PART #") "C21189") (field (name "Comment") "0603WAF0000T5E"))
      (libsource (lib "JLC_PCB") (part "0603WAF0000T5E"))
    )
    (comp (ref "RC_133")
      (value "0R")
      (footprint "R_0603")
      (description "R - RESISTOR - SMD - 0R - 1% - 0603")
      (fields (field (name "LCSC PART #") "C21189") (field (name "Comment") "0603WAF0000T5E"))
      (libsource (lib "JLC_PCB") (part "0603WAF0000T5E"))
    )
    (comp (ref "RC_134")
      (value "0R")
      (footprint "R_0603")
      (description "R - RESISTOR - SMD - 0R - 1% - 0603")
      (fields (field (name "LCSC PART #") "C21189") (field (name "Comment") "0603WAF0000T5E"))
      (libsource (lib "JLC_PCB") (part "0603WAF0000T5E"))
    )
    (comp (ref "RC_135")
      (value "0R")
      (footprint "R_0603")
      (description "R - RESISTOR - SMD - 0R - 1% - 0603")
      (fields (field (name "LCSC PART #") "C21189") (field (name "Comment") "0603WAF0000T5E"))
      (libsource (lib "JLC_PCB") (part "0603WAF0000T5E"))
    )
    (comp (ref "RC_136")
      (value "0R")
      (footprint "R_0603")
      (description "R - RESISTOR - SMD - 0R - 1% - 0603")
      (fields (field (name "LCSC PART #") "C21189") (field (name "Comment") "0603WAF0000T5E"))
      (libsource (lib "JLC_PCB") (part "0603WAF0000T5E"))
    )
    (comp (ref "RC_137")
      (value "0R")
      (footprint "R_0603")
      (description "R - RESISTOR - SMD - 0R - 1% - 0603")
      (fields (field (name "LCSC PART #") "C21189") (field (name "Comment") "0603WAF0000T5E"))
      (libsource (lib "JLC_PCB") (part "0603WAF0000T5E"))
    )
    (comp (ref "RC_138")
      (value "0R")
      (footprint "R_0603")
      (description "R - RESISTOR - SMD - 0R - 1% - 0603")
      (fields (field (name "LCSC PART #") "C21189") (field (name "Comment") "0603WAF0000T5E"))
      (libsource (lib "JLC_PCB") (part "0603WAF0000T5E"))
    )
    (comp (ref "RC_139")
      (value "0R")
      (footprint "R_0603")
      (description "R - RESISTOR - SMD - 0R - 1% - 0603")
      (fields (field (name "LCSC PART #") "C21189") (field (name "Comment") "0603WAF0000T5E"))
      (libsource (lib "JLC_PCB") (part "0603WAF0000T5E"))
    )
    (comp (ref "RC_140")
      (value "0R")
      (footprint "R_0603")
      (description "R - RESISTOR - SMD - 0R - 1% - 0603")
      (fields (field (name "LCSC PART #") "C21189") (field (name "Comment") "0603WAF0000T5E"))
      (libsource (lib "JLC_PCB") (part "0603WAF0000T5E"))
    )
    (comp (ref "RC_141")
      (value "0R")
      (footprint "R_0603")
      (description "R - RESISTOR - SMD - 0R - 1% - 0603")
      (fields (field (name "LCSC PART #") "C21189") (field (name "Comment") "0603WAF0000T5E"))
      (libsource (lib "JLC_PCB") (part "0603WAF0000T5E"))
    )
    (comp (ref "RC_142")
      (value "0R")
      (footprint "R_0603")
      (description "R - RESISTOR - SMD - 0R - 1% - 0603")
      (fields (field (name "LCSC PART #") "C21189") (field (name "Comment") "0603WAF0000T5E"))
      (libsource (lib "JLC_PCB") (part "0603WAF0000T5E"))
    )
    (comp (ref "RC_143")
      (value "0R")
      (footprint "R_0603")
      (description "R - RESISTOR - SMD - 0R - 1% - 0603")
      (fields (field (name "LCSC PART #") "C21189") (field (name "Comment") "0603WAF0000T5E"))
      (libsource (lib "JLC_PCB") (part "0603WAF0000T5E"))
    )
    (comp (ref "RC_144")
      (value "0R")
      (footprint "R_0603")
      (description "R - RESISTOR - SMD - 0R - 1% - 0603")
      (fields (field (name "LCSC PART #") "C21189") (field (name "Comment") "0603WAF0000T5E"))
      (libsource (lib "JLC_PCB") (part "0603WAF0000T5E"))
    )
    (comp (ref "RC_145")
      (value "0R")
      (footprint "R_0603")
      (description "R - RESISTOR - SMD - 0R - 1% - 0603")
      (fields (field (name "LCSC PART #") "C21189") (field (name "Comment") "0603WAF0000T5E"))
      (libsource (lib "JLC_PCB") (part "0603WAF0000T5E"))
    )
    (comp (ref "RC_146")
      (value "0R")
      (footprint "R_0603")
      (description "R - RESISTOR - SMD - 0R - 1% - 0603")
      (fields (field (name "LCSC PART #") "C21189") (field (name "Comment") "0603WAF0000T5E"))
      (libsource (lib "JLC_PCB") (part "0603WAF0000T5E"))
    )
    (comp (ref "RC_147")
      (value "0R")
      (footprint "R_0603")
      (description "R - RESISTOR - SMD - 0R - 1% - 0603")
      (fields (field (name "LCSC PART #") "C21189") (field (name "Comment") "0603WAF0000T5E"))
      (libsource (lib "JLC_PCB") (part "0603WAF0000T5E"))
    )
    (comp (ref "RC_148")
      (value "0R")
      (footprint "R_0603")
      (description "R - RESISTOR - SMD - 0R - 1% - 0603")
      (fields (field (name "LCSC PART #") "C21189") (field (name "Comment") "0603WAF0000T5E"))
      (libsource (lib "JLC_PCB") (part "0603WAF0000T5E"))
    )
    (comp (ref "RC_149")
      (value "0R")
      (footprint "R_0603")
      (description "R - RESISTOR - SMD - 0R - 1% - 0603")
      (fields (field (name "LCSC PART #") "C21189") (field (name "Comment") "0603WAF0000T5E"))
      (libsource (lib "JLC_PCB") (part "0603WAF0000T5E"))
    )
    (comp (ref "RC_150")
      (value "0R")
      (footprint "R_0603")
      (description "R - RESISTOR - SMD - 0R - 1% - 0603")
      (fields (field (name "LCSC PART #") "C21189") (field (name "Comment") "0603WAF0000T5E"))
      (libsource (lib "JLC_PCB") (part "0603WAF0000T5E"))
    )
    (comp (ref "RC_151")
      (value "0R")
      (footprint "R_0603")
      (description "R - RESISTOR - SMD - 0R - 1% - 0603")
      (fields (field (name "LCSC PART #") "C21189") (field (name "Comment") "0603WAF0000T5E"))
      (libsource (lib "JLC_PCB") (part "0603WAF0000T5E"))
    )
    (comp (ref "RC_152")
      (value "0R")
      (footprint "R_0603")
      (description "R - RESISTOR - SMD - 0R - 1% - 0603")
      (fields (field (name "LCSC PART #") "C21189") (field (name "Comment") "0603WAF0000T5E"))
      (libsource (lib "JLC_PCB") (part "0603WAF0000T5E"))
    )
    (comp (ref "RC_153")
      (value "0R")
      (footprint "R_0603")
      (description "R - RESISTOR - SMD - 0R - 1% - 0603")
      (fields (field (name "LCSC PART #") "C21189") (field (name "Comment") "0603WAF0000T5E"))
      (libsource (lib "JLC_PCB") (part "0603WAF0000T5E"))
    )
    (comp (ref "RC_154")
      (value "0R")
      (footprint "R_0603")
      (description "R - RESISTOR - SMD - 0R - 1% - 0603")
      (fields (field (name "LCSC PART #") "C21189") (field (name "Comment") "0603WAF0000T5E"))
      (libsource (lib "JLC_PCB") (part "0603WAF0000T5E"))
    )
    (comp (ref "RC_155")
      (value "0R")
      (footprint "R_0603")
      (description "R - RESISTOR - SMD - 0R - 1% - 0603")
      (fields (field (name "LCSC PART #") "C21189") (field (name "Comment") "0603WAF0000T5E"))
      (libsource (lib "JLC_PCB") (part "0603WAF0000T5E"))
    )
    (comp (ref "RC_156")
      (value "0R")
      (footprint "R_0603")
      (description "R - RESISTOR - SMD - 0R - 1% - 0603")
      (fields (field (name "LCSC PART #") "C21189") (field (name "Comment") "0603WAF0000T5E"))
      (libsource (lib "JLC_PCB") (part "0603WAF0000T5E"))
    )
    (comp (ref "RC_157")
      (value "0R")
      (footprint "R_0603")
      (description "R - RESISTOR - SMD - 0R - 1% - 0603")
      (fields (field (name "LCSC PART #") "C21189") (field (name "Comment") "0603WAF0000T5E"))
      (libsource (lib "JLC_PCB") (part "0603WAF0000T5E"))
    )
    (comp (ref "RC_158")
      (value "0R")
      (footprint "R_0603")
      (description "R - RESISTOR - SMD - 0R - 1% - 0603")
      (fields (field (name "LCSC PART #") "C21189") (field (name "Comment") "0603WAF0000T5E"))
      (libsource (lib "JLC_PCB") (part "0603WAF0000T5E"))
    )
    (comp (ref "RC_159")
      (value "0R")
      (footprint "R_0603")
      (description "R - RESISTOR - SMD - 0R - 1% - 0603")
      (fields (field (name "LCSC PART #") "C21189") (field (name "Comment") "0603WAF0000T5E"))
      (libsource (lib "JLC_PCB") (part "0603WAF0000T5E"))
    )
    (comp (ref "RC_160")
      (value "0R")
      (footprint "R_0603")
      (description "R - RESISTOR - SMD - 0R - 1% - 0603")
      (fields (field (name "LCSC PART #") "C21189") (field (name "Comment") "0603WAF0000T5E"))
      (libsource (lib "JLC_PCB") (part "0603WAF0000T5E"))
    )
    (comp (ref "RC_161")
      (value "0R")
      (footprint "R_0603")
      (description "R - RESISTOR - SMD - 0R - 1% - 0603")
      (fields (field (name "LCSC PART #") "C21189") (field (name "Comment") "0603WAF0000T5E"))
      (libsource (lib "JLC_PCB") (part "0603WAF0000T5E"))
    )
    (comp (ref "RC_162")
      (value "0R")
      (footprint "R_0603")
      (description "R - RESISTOR - SMD - 0R - 1% - 0603")
      (fields (field (name "LCSC PART #") "C21189") (field (name "Comment") "0603WAF0000T5E"))
      (libsource (lib "JLC_PCB") (part "0603WAF0000T5E"))
    )
    (comp (ref "RC_163")
      (value "0R")
      (footprint "R_0603")
      (description "R - RESISTOR - SMD - 0R - 1% - 0603")
      (fields (field (name "LCSC PART #") "C21189") (field (name "Comment") "0603WAF0000T5E"))
      (libsource (lib "JLC_PCB") (part "0603WAF0000T5E"))
    )
    (comp (ref "RC_164")
      (value "0R")
      (footprint "R_0603")
      (description "R - RESISTOR - SMD - 0R - 1% - 0603")
      (fields (field (name "LCSC PART #") "C21189") (field (name "Comment") "0603WAF0000T5E"))
      (libsource (lib "JLC_PCB") (part "0603WAF0000T5E"))
    )
    (comp (ref "RC_165")
      (value "0R")
      (footprint "R_0603")
      (description "R - RESISTOR - SMD - 0R - 1% - 0603")
      (fields (field (name "LCSC PART #") "C21189") (field (name "Comment") "0603WAF0000T5E"))
      (libsource (lib "JLC_PCB") (part "0603WAF0000T5E"))
    )
    (comp (ref "RC_166")
      (value "0R")
      (footprint "R_0603")
      (description "R - RESISTOR - SMD - 0R - 1% - 0603")
      (fields (field (name "LCSC PART #") "C21189") (field (name "Comment") "0603WAF0000T5E"))
      (libsource (lib "JLC_PCB") (part "0603WAF0000T5E"))
    )
    (comp (ref "RC_167")
      (value "0R")
      (footprint "R_0603")
      (description "R - RESISTOR - SMD - 0R - 1% - 0603")
      (fields (field (name "LCSC PART #") "C21189") (field (name "Comment") "0603WAF0000T5E"))
      (libsource (lib "JLC_PCB") (part "0603WAF0000T5E"))
    )
    (comp (ref "RC_168")
      (value "0R")
      (footprint "R_0603")
      (description "R - RESISTOR - SMD - 0R - 1% - 0603")
      (fields (field (name "LCSC PART #") "C21189") (field (name "Comment") "0603WAF0000T5E"))
      (libsource (lib "JLC_PCB") (part "0603WAF0000T5E"))
    )
    (comp (ref "RC_169")
      (value "0R")
      (footprint "R_0603")
      (description "R - RESISTOR - SMD - 0R - 1% - 0603")
      (fields (field (name "LCSC PART #") "C21189") (field (name "Comment") "0603WAF0000T5E"))
      (libsource (lib "JLC_PCB") (part "0603WAF0000T5E"))
    )
    (comp (ref "RC_170")
      (value "0R")
      (footprint "R_0603")
      (description "R - RESISTOR - SMD - 0R - 1% - 0603")
      (fields (field (name "LCSC PART #") "C21189") (field (name "Comment") "0603WAF0000T5E"))
      (libsource (lib "JLC_PCB") (part "0603WAF0000T5E"))
    )
    (comp (ref "RC_171")
      (value "0R")
      (footprint "R_0603")
      (description "R - RESISTOR - SMD - 0R - 1% - 0603")
      (fields (field (name "LCSC PART #") "C21189") (field (name "Comment") "0603WAF0000T5E"))
      (libsource (lib "JLC_PCB") (part "0603WAF0000T5E"))
    )
    (comp (ref "RC_172")
      (value "0R")
      (footprint "R_0603")
      (description "R - RESISTOR - SMD - 0R - 1% - 0603")
      (fields (field (name "LCSC PART #") "C21189") (field (name "Comment") "0603WAF0000T5E"))
      (libsource (lib "JLC_PCB") (part "0603WAF0000T5E"))
    )
    (comp (ref "RC_173")
      (value "0R")
      (footprint "R_0603")
      (description "R - RESISTOR - SMD - 0R - 1% - 0603")
      (fields (field (name "LCSC PART #") "C21189") (field (name "Comment") "0603WAF0000T5E"))
      (libsource (lib "JLC_PCB") (part "0603WAF0000T5E"))
    )
    (comp (ref "RC_174")
      (value "0R")
      (footprint "R_0603")
      (description "R - RESISTOR - SMD - 0R - 1% - 0603")
      (fields (field (name "LCSC PART #") "C21189") (field (name "Comment") "0603WAF0000T5E"))
      (libsource (lib "JLC_PCB") (part "0603WAF0000T5E"))
    )
    (comp (ref "RC_175")
      (value "0R")
      (footprint "R_0603")
      (description "R - RESISTOR - SMD - 0R - 1% - 0603")
      (fields (field (name "LCSC PART #") "C21189") (field (name "Comment") "0603WAF0000T5E"))
      (libsource (lib "JLC_PCB") (part "0603WAF0000T5E"))
    )
    (comp (ref "RC_176")
      (value "0R")
      (footprint "R_0603")
      (description "R - RESISTOR - SMD - 0R - 1% - 0603")
      (fields (field (name "LCSC PART #") "C21189") (field (name "Comment") "0603WAF0000T5E"))
      (libsource (lib "JLC_PCB") (part "0603WAF0000T5E"))
    )
    (comp (ref "RC_177")
      (value "0R")
      (footprint "R_0603")
      (description "R - RESISTOR - SMD - 0R - 1% - 0603")
      (fields (field (name "LCSC PART #") "C21189") (field (name "Comment") "0603WAF0000T5E"))
      (libsource (lib "JLC_PCB") (part "0603WAF0000T5E"))
    )
    (comp (ref "RC_178")
      (value "0R")
      (footprint "R_0603")
      (description "R - RESISTOR - SMD - 0R - 1% - 0603")
      (fields (field (name "LCSC PART #") "C21189") (field (name "Comment") "0603WAF0000T5E"))
      (libsource (lib "JLC_PCB") (part "0603WAF0000T5E"))
    )
    (comp (ref "RC_179")
      (value "0R")
      (footprint "R_0603")
      (description "R - RESISTOR - SMD - 0R - 1% - 0603")
      (fields (field (name "LCSC PART #") "C21189") (field (name "Comment") "0603WAF0000T5E"))
      (libsource (lib "JLC_PCB") (part "0603WAF0000T5E"))
    )
    (comp (ref "RC_180")
      (value "0R")
      (footprint "R_0603")
      (description "R - RESISTOR - SMD - 0R - 1% - 0603")
      (fields (field (name "LCSC PART #") "C21189") (field (name "Comment") "0603WAF0000T5E"))
      (libsource (lib "JLC_PCB") (part "0603WAF0000T5E"))
    )
    (comp (ref "RC_181")
      (value "0R")
      (footprint "R_0603")
      (description "R - RESISTOR - SMD - 0R - 1% - 0603")
      (fields (field (name "LCSC PART #") "C21189") (field (name "Comment") "0603WAF0000T5E"))
      (libsource (lib "JLC_PCB") (part "0603WAF0000T5E"))
    )
    (comp (ref "RC_182")
      (value "0R")
      (footprint "R_0603")
      (description "R - RESISTOR - SMD - 0R - 1% - 0603")
      (fields (field (name "LCSC PART #") "C21189") (field (name "Comment") "0603WAF0000T5E"))
      (libsource (lib "JLC_PCB") (part "0603WAF0000T5E"))
    )
    (comp (ref "RC_183")
      (value "0R")
      (footprint "R_0603")
      (description "R - RESISTOR - SMD - 0R - 1% - 0603")
      (fields (field (name "LCSC PART #") "C21189") (field (name "Comment") "0603WAF0000T5E"))
      (libsource (lib "JLC_PCB") (part "0603WAF0000T5E"))
    )
    (comp (ref "RC_184")
      (value "0R")
      (footprint "R_0603")
      (description "R - RESISTOR - SMD - 0R - 1% - 0603")
      (fields (field (name "LCSC PART #") "C21189") (field (name "Comment") "0603WAF0000T5E"))
      (libsource (lib "JLC_PCB") (part "0603WAF0000T5E"))
    )
    (comp (ref "RC_185")
      (value "0R")
      (footprint "R_0603")
      (description "R - RESISTOR - SMD - 0R - 1% - 0603")
      (fields (field (name "LCSC PART #") "C21189") (field (name "Comment") "0603WAF0000T5E"))
      (libsource (lib "JLC_PCB") (part "0603WAF0000T5E"))
    )
    (comp (ref "RC_186")
      (value "0R")
      (footprint "R_0603")
      (description "R - RESISTOR - SMD - 0R - 1% - 0603")
      (fields (field (name "LCSC PART #") "C21189") (field (name "Comment") "0603WAF0000T5E"))
      (libsource (lib "JLC_PCB") (part "0603WAF0000T5E"))
    )
    (comp (ref "RC_187")
      (value "0R")
      (footprint "R_0603")
      (description "R - RESISTOR - SMD - 0R - 1% - 0603")
      (fields (field (name "LCSC PART #") "C21189") (field (name "Comment") "0603WAF0000T5E"))
      (libsource (lib "JLC_PCB") (part "0603WAF0000T5E"))
    )
    (comp (ref "RC_188")
      (value "0R")
      (footprint "R_0603")
      (description "R - RESISTOR - SMD - 0R - 1% - 0603")
      (fields (field (name "LCSC PART #") "C21189") (field (name "Comment") "0603WAF0000T5E"))
      (libsource (lib "JLC_PCB") (part "0603WAF0000T5E"))
    )
    (comp (ref "RC_189")
      (value "0R")
      (footprint "R_0603")
      (description "R - RESISTOR - SMD - 0R - 1% - 0603")
      (fields (field (name "LCSC PART #") "C21189") (field (name "Comment") "0603WAF0000T5E"))
      (libsource (lib "JLC_PCB") (part "0603WAF0000T5E"))
    )
    (comp (ref "RC_190")
      (value "0R")
      (footprint "R_0603")
      (description "R - RESISTOR - SMD - 0R - 1% - 0603")
      (fields (field (name "LCSC PART #") "C21189") (field (name "Comment") "0603WAF0000T5E"))
      (libsource (lib "JLC_PCB") (part "0603WAF0000T5E"))
    )
    (comp (ref "RC_191")
      (value "0R")
      (footprint "R_0603")
      (description "R - RESISTOR - SMD - 0R - 1% - 0603")
      (fields (field (name "LCSC PART #") "C21189") (field (name "Comment") "0603WAF0000T5E"))
      (libsource (lib "JLC_PCB") (part "0603WAF0000T5E"))
    )
    (comp (ref "RC_192")
      (value "0R")
      (footprint "R_0603")
      (description "R - RESISTOR - SMD - 0R - 1% - 0603")
      (fields (field (name "LCSC PART #") "C21189") (field (name "Comment") "0603WAF0000T5E"))
      (libsource (lib "JLC_PCB") (part "0603WAF0000T5E"))
    )
    (comp (ref "RC_193")
      (value "0R")
      (footprint "R_0603")
      (description "R - RESISTOR - SMD - 0R - 1% - 0603")
      (fields (field (name "LCSC PART #") "C21189") (field (name "Comment") "0603WAF0000T5E"))
      (libsource (lib "JLC_PCB") (part "0603WAF0000T5E"))
    )
    (comp (ref "RC_194")
      (value "0R")
      (footprint "R_0603")
      (description "R - RESISTOR - SMD - 0R - 1% - 0603")
      (fields (field (name "LCSC PART #") "C21189") (field (name "Comment") "0603WAF0000T5E"))
      (libsource (lib "JLC_PCB") (part "0603WAF0000T5E"))
    )
    (comp (ref "RC_195")
      (value "0R")
      (footprint "R_0603")
      (description "R - RESISTOR - SMD - 0R - 1% - 0603")
      (fields (field (name "LCSC PART #") "C21189") (field (name "Comment") "0603WAF0000T5E"))
      (libsource (lib "JLC_PCB") (part "0603WAF0000T5E"))
    )
    (comp (ref "RC_196")
      (value "0R")
      (footprint "R_0603")
      (description "R - RESISTOR - SMD - 0R - 1% - 0603")
      (fields (field (name "LCSC PART #") "C21189") (field (name "Comment") "0603WAF0000T5E"))
      (libsource (lib "JLC_PCB") (part "0603WAF0000T5E"))
    )
    (comp (ref "RC_197")
      (value "0R")
      (footprint "R_0603")
      (description "R - RESISTOR - SMD - 0R - 1% - 0603")
      (fields (field (name "LCSC PART #") "C21189") (field (name "Comment") "0603WAF0000T5E"))
      (libsource (lib "JLC_PCB") (part "0603WAF0000T5E"))
    )
    (comp (ref "RC_198")
      (value "0R")
      (footprint "R_0603")
      (description "R - RESISTOR - SMD - 0R - 1% - 0603")
      (fields (field (name "LCSC PART #") "C21189") (field (name "Comment") "0603WAF0000T5E"))
      (libsource (lib "JLC_PCB") (part "0603WAF0000T5E"))
    )
    (comp (ref "RC_199")
      (value "0R")
      (footprint "R_0603")
      (description "R - RESISTOR - SMD - 0R - 1% - 0603")
      (fields (field (name "LCSC PART #") "C21189") (field (name "Comment") "0603WAF0000T5E"))
      (libsource (lib "JLC_PCB") (part "0603WAF0000T5E"))
    )
    (comp (ref "RC_200")
      (value "0R")
      (footprint "R_0603")
      (description "R - RESISTOR - SMD - 0R - 1% - 0603")
      (fields (field (name "LCSC PART #") "C21189") (field (name "Comment") "0603WAF0000T5E"))
      (libsource (lib "JLC_PCB") (part "0603WAF0000T5E"))
    )
    (comp (ref "RC_201")
      (value "0R")
      (footprint "R_0603")
      (description "R - RESISTOR - SMD - 0R - 1% - 0603")
      (fields (field (name "LCSC PART #") "C21189") (field (name "Comment") "0603WAF0000T5E"))
      (libsource (lib "JLC_PCB") (part "0603WAF0000T5E"))
    )
    (comp (ref "RC_202")
      (value "0R")
      (footprint "R_0603")
      (description "R - RESISTOR - SMD - 0R - 1% - 0603")
      (fields (field (name "LCSC PART #") "C21189") (field (name "Comment") "0603WAF0000T5E"))
      (libsource (lib "JLC_PCB") (part "0603WAF0000T5E"))
    )
    (comp (ref "RC_203")
      (value "0R")
      (footprint "R_0603")
      (description "R - RESISTOR - SMD - 0R - 1% - 0603")
      (fields (field (name "LCSC PART #") "C21189") (field (name "Comment") "0603WAF0000T5E"))
      (libsource (lib "JLC_PCB") (part "0603WAF0000T5E"))
    )
    (comp (ref "RC_204")
      (value "0R")
      (footprint "R_0603")
      (description "R - RESISTOR - SMD - 0R - 1% - 0603")
      (fields (field (name "LCSC PART #") "C21189") (field (name "Comment") "0603WAF0000T5E"))
      (libsource (lib "JLC_PCB") (part "0603WAF0000T5E"))
    )
    (comp (ref "RC_205")
      (value "0R")
      (footprint "R_0603")
      (description "R - RESISTOR - SMD - 0R - 1% - 0603")
      (fields (field (name "LCSC PART #") "C21189") (field (name "Comment") "0603WAF0000T5E"))
      (libsource (lib "JLC_PCB") (part "0603WAF0000T5E"))
    )
    (comp (ref "RC_206")
      (value "0R")
      (footprint "R_0603")
      (description "R - RESISTOR - SMD - 0R - 1% - 0603")
      (fields (field (name "LCSC PART #") "C21189") (field (name "Comment") "0603WAF0000T5E"))
      (libsource (lib "JLC_PCB") (part "0603WAF0000T5E"))
    )
    (comp (ref "RC_207")
      (value "0R")
      (footprint "R_0603")
      (description "R - RESISTOR - SMD - 0R - 1% - 0603")
      (fields (field (name "LCSC PART #") "C21189") (field (name "Comment") "0603WAF0000T5E"))
      (libsource (lib "JLC_PCB") (part "0603WAF0000T5E"))
    )
    (comp (ref "RC_208")
      (value "0R")
      (footprint "R_0603")
      (description "R - RESISTOR - SMD - 0R - 1% - 0603")
      (fields (field (name "LCSC PART #") "C21189") (field (name "Comment") "0603WAF0000T5E"))
      (libsource (lib "JLC_PCB") (part "0603WAF0000T5E"))
    )
    (comp (ref "RC_209")
      (value "0R")
      (footprint "R_0603")
      (description "R - RESISTOR - SMD - 0R - 1% - 0603")
      (fields (field (name "LCSC PART #") "C21189") (field (name "Comment") "0603WAF0000T5E"))
      (libsource (lib "JLC_PCB") (part "0603WAF0000T5E"))
    )
    (comp (ref "RC_210")
      (value "0R")
      (footprint "R_0603")
      (description "R - RESISTOR - SMD - 0R - 1% - 0603")
      (fields (field (name "LCSC PART #") "C21189") (field (name "Comment") "0603WAF0000T5E"))
      (libsource (lib "JLC_PCB") (part "0603WAF0000T5E"))
    )
    (comp (ref "RC_211")
      (value "0R")
      (footprint "R_0603")
      (description "R - RESISTOR - SMD - 0R - 1% - 0603")
      (fields (field (name "LCSC PART #") "C21189") (field (name "Comment") "0603WAF0000T5E"))
      (libsource (lib "JLC_PCB") (part "0603WAF0000T5E"))
    )
    (comp (ref "RC_212")
      (value "0R")
      (footprint "R_0603")
      (description "R - RESISTOR - SMD - 0R - 1% - 0603")
      (fields (field (name "LCSC PART #") "C21189") (field (name "Comment") "0603WAF0000T5E"))
      (libsource (lib "JLC_PCB") (part "0603WAF0000T5E"))
    )
    (comp (ref "RC_213")
      (value "0R")
      (footprint "R_0603")
      (description "R - RESISTOR - SMD - 0R - 1% - 0603")
      (fields (field (name "LCSC PART #") "C21189") (field (name "Comment") "0603WAF0000T5E"))
      (libsource (lib "JLC_PCB") (part "0603WAF0000T5E"))
    )
    (comp (ref "RC_214")
      (value "0R")
      (footprint "R_0603")
      (description "R - RESISTOR - SMD - 0R - 1% - 0603")
      (fields (field (name "LCSC PART #") "C21189") (field (name "Comment") "0603WAF0000T5E"))
      (libsource (lib "JLC_PCB") (part "0603WAF0000T5E"))
    )
    (comp (ref "RC_215")
      (value "0R")
      (footprint "R_0603")
      (description "R - RESISTOR - SMD - 0R - 1% - 0603")
      (fields (field (name "LCSC PART #") "C21189") (field (name "Comment") "0603WAF0000T5E"))
      (libsource (lib "JLC_PCB") (part "0603WAF0000T5E"))
    )
    (comp (ref "RC_216")
      (value "0R")
      (footprint "R_0603")
      (description "R - RESISTOR - SMD - 0R - 1% - 0603")
      (fields (field (name "LCSC PART #") "C21189") (field (name "Comment") "0603WAF0000T5E"))
      (libsource (lib "JLC_PCB") (part "0603WAF0000T5E"))
    )
    (comp (ref "RC_217")
      (value "0R")
      (footprint "R_0603")
      (description "R - RESISTOR - SMD - 0R - 1% - 0603")
      (fields (field (name "LCSC PART #") "C21189") (field (name "Comment") "0603WAF0000T5E"))
      (libsource (lib "JLC_PCB") (part "0603WAF0000T5E"))
    )
    (comp (ref "RC_218")
      (value "0R")
      (footprint "R_0603")
      (description "R - RESISTOR - SMD - 0R - 1% - 0603")
      (fields (field (name "LCSC PART #") "C21189") (field (name "Comment") "0603WAF0000T5E"))
      (libsource (lib "JLC_PCB") (part "0603WAF0000T5E"))
    )
    (comp (ref "RC_219")
      (value "0R")
      (footprint "R_0603")
      (description "R - RESISTOR - SMD - 0R - 1% - 0603")
      (fields (field (name "LCSC PART #") "C21189") (field (name "Comment") "0603WAF0000T5E"))
      (libsource (lib "JLC_PCB") (part "0603WAF0000T5E"))
    )
    (comp (ref "RC_220")
      (value "0R")
      (footprint "R_0603")
      (description "R - RESISTOR - SMD - 0R - 1% - 0603")
      (fields (field (name "LCSC PART #") "C21189") (field (name "Comment") "0603WAF0000T5E"))
      (libsource (lib "JLC_PCB") (part "0603WAF0000T5E"))
    )
    (comp (ref "RC_221")
      (value "0R")
      (footprint "R_0603")
      (description "R - RESISTOR - SMD - 0R - 1% - 0603")
      (fields (field (name "LCSC PART #") "C21189") (field (name "Comment") "0603WAF0000T5E"))
      (libsource (lib "JLC_PCB") (part "0603WAF0000T5E"))
    )
    (comp (ref "RC_222")
      (value "0R")
      (footprint "R_0603")
      (description "R - RESISTOR - SMD - 0R - 1% - 0603")
      (fields (field (name "LCSC PART #") "C21189") (field (name "Comment") "0603WAF0000T5E"))
      (libsource (lib "JLC_PCB") (part "0603WAF0000T5E"))
    )
    (comp (ref "RC_223")
      (value "0R")
      (footprint "R_0603")
      (description "R - RESISTOR - SMD - 0R - 1% - 0603")
      (fields (field (name "LCSC PART #") "C21189") (field (name "Comment") "0603WAF0000T5E"))
      (libsource (lib "JLC_PCB") (part "0603WAF0000T5E"))
    )
    (comp (ref "RC_224")
      (value "0R")
      (footprint "R_0603")
      (description "R - RESISTOR - SMD - 0R - 1% - 0603")
      (fields (field (name "LCSC PART #") "C21189") (field (name "Comment") "0603WAF0000T5E"))
      (libsource (lib "JLC_PCB") (part "0603WAF0000T5E"))
    )
    (comp (ref "RC_225")
      (value "0R")
      (footprint "R_0603")
      (description "R - RESISTOR - SMD - 0R - 1% - 0603")
      (fields (field (name "LCSC PART #") "C21189") (field (name "Comment") "0603WAF0000T5E"))
      (libsource (lib "JLC_PCB") (part "0603WAF0000T5E"))
    )
    (comp (ref "RC_226")
      (value "0R")
      (footprint "R_0603")
      (description "R - RESISTOR - SMD - 0R - 1% - 0603")
      (fields (field (name "LCSC PART #") "C21189") (field (name "Comment") "0603WAF0000T5E"))
      (libsource (lib "JLC_PCB") (part "0603WAF0000T5E"))
    )
    (comp (ref "RC_227")
      (value "0R")
      (footprint "R_0603")
      (description "R - RESISTOR - SMD - 0R - 1% - 0603")
      (fields (field (name "LCSC PART #") "C21189") (field (name "Comment") "0603WAF0000T5E"))
      (libsource (lib "JLC_PCB") (part "0603WAF0000T5E"))
    )
    (comp (ref "RC_228")
      (value "0R")
      (footprint "R_0603")
      (description "R - RESISTOR - SMD - 0R - 1% - 0603")
      (fields (field (name "LCSC PART #") "C21189") (field (name "Comment") "0603WAF0000T5E"))
      (libsource (lib "JLC_PCB") (part "0603WAF0000T5E"))
    )
    (comp (ref "RC_229")
      (value "0R")
      (footprint "R_0603")
      (description "R - RESISTOR - SMD - 0R - 1% - 0603")
      (fields (field (name "LCSC PART #") "C21189") (field (name "Comment") "0603WAF0000T5E"))
      (libsource (lib "JLC_PCB") (part "0603WAF0000T5E"))
    )
    (comp (ref "RC_230")
      (value "0R")
      (footprint "R_0603")
      (description "R - RESISTOR - SMD - 0R - 1% - 0603")
      (fields (field (name "LCSC PART #") "C21189") (field (name "Comment") "0603WAF0000T5E"))
      (libsource (lib "JLC_PCB") (part "0603WAF0000T5E"))
    )
    (comp (ref "RC_231")
      (value "0R")
      (footprint "R_0603")
      (description "R - RESISTOR - SMD - 0R - 1% - 0603")
      (fields (field (name "LCSC PART #") "C21189") (field (name "Comment") "0603WAF0000T5E"))
      (libsource (lib "JLC_PCB") (part "0603WAF0000T5E"))
    )
    (comp (ref "RC_232")
      (value "0R")
      (footprint "R_0603")
      (description "R - RESISTOR - SMD - 0R - 1% - 0603")
      (fields (field (name "LCSC PART #") "C21189") (field (name "Comment") "0603WAF0000T5E"))
      (libsource (lib "JLC_PCB") (part "0603WAF0000T5E"))
    )
    (comp (ref "RC_233")
      (value "0R")
      (footprint "R_0603")
      (description "R - RESISTOR - SMD - 0R - 1% - 0603")
      (fields (field (name "LCSC PART #") "C21189") (field (name "Comment") "0603WAF0000T5E"))
      (libsource (lib "JLC_PCB") (part "0603WAF0000T5E"))
    )
    (comp (ref "RC_234")
      (value "0R")
      (footprint "R_0603")
      (description "R - RESISTOR - SMD - 0R - 1% - 0603")
      (fields (field (name "LCSC PART #") "C21189") (field (name "Comment") "0603WAF0000T5E"))
      (libsource (lib "JLC_PCB") (part "0603WAF0000T5E"))
    )
    (comp (ref "RC_235")
      (value "0R")
      (footprint "R_0603")
      (description "R - RESISTOR - SMD - 0R - 1% - 0603")
      (fields (field (name "LCSC PART #") "C21189") (field (name "Comment") "0603WAF0000T5E"))
      (libsource (lib "JLC_PCB") (part "0603WAF0000T5E"))
    )
    (comp (ref "RC_236")
      (value "0R")
      (footprint "R_0603")
      (description "R - RESISTOR - SMD - 0R - 1% - 0603")
      (fields (field (name "LCSC PART #") "C21189") (field (name "Comment") "0603WAF0000T5E"))
      (libsource (lib "JLC_PCB") (part "0603WAF0000T5E"))
    )
    (comp (ref "RC_237")
      (value "0R")
      (footprint "R_0603")
      (description "R - RESISTOR - SMD - 0R - 1% - 0603")
      (fields (field (name "LCSC PART #") "C21189") (field (name "Comment") "0603WAF0000T5E"))
      (libsource (lib "JLC_PCB") (part "0603WAF0000T5E"))
    )
    (comp (ref "RC_238")
      (value "0R")
      (footprint "R_0603")
      (description "R - RESISTOR - SMD - 0R - 1% - 0603")
      (fields (field (name "LCSC PART #") "C21189") (field (name "Comment") "0603WAF0000T5E"))
      (libsource (lib "JLC_PCB") (part "0603WAF0000T5E"))
    )
    (comp (ref "RC_239")
      (value "0R")
      (footprint "R_0603")
      (description "R - RESISTOR - SMD - 0R - 1% - 0603")
      (fields (field (name "LCSC PART #") "C21189") (field (name "Comment") "0603WAF0000T5E"))
      (libsource (lib "JLC_PCB") (part "0603WAF0000T5E"))
    )
    (comp (ref "RC_240")
      (value "0R")
      (footprint "R_0603")
      (description "R - RESISTOR - SMD - 0R - 1% - 0603")
      (fields (field (name "LCSC PART #") "C21189") (field (name "Comment") "0603WAF0000T5E"))
      (libsource (lib "JLC_PCB") (part "0603WAF0000T5E"))
    )
    (comp (ref "RC_241")
      (value "0R")
      (footprint "R_0603")
      (description "R - RESISTOR - SMD - 0R - 1% - 0603")
      (fields (field (name "LCSC PART #") "C21189") (field (name "Comment") "0603WAF0000T5E"))
      (libsource (lib "JLC_PCB") (part "0603WAF0000T5E"))
    )
    (comp (ref "RC_242")
      (value "0R")
      (footprint "R_0603")
      (description "R - RESISTOR - SMD - 0R - 1% - 0603")
      (fields (field (name "LCSC PART #") "C21189") (field (name "Comment") "0603WAF0000T5E"))
      (libsource (lib "JLC_PCB") (part "0603WAF0000T5E"))
    )
    (comp (ref "RC_243")
      (value "0R")
      (footprint "R_0603")
      (description "R - RESISTOR - SMD - 0R - 1% - 0603")
      (fields (field (name "LCSC PART #") "C21189") (field (name "Comment") "0603WAF0000T5E"))
      (libsource (lib "JLC_PCB") (part "0603WAF0000T5E"))
    )
    (comp (ref "RC_244")
      (value "0R")
      (footprint "R_0603")
      (description "R - RESISTOR - SMD - 0R - 1% - 0603")
      (fields (field (name "LCSC PART #") "C21189") (field (name "Comment") "0603WAF0000T5E"))
      (libsource (lib "JLC_PCB") (part "0603WAF0000T5E"))
    )
    (comp (ref "RC_245")
      (value "0R")
      (footprint "R_0603")
      (description "R - RESISTOR - SMD - 0R - 1% - 0603")
      (fields (field (name "LCSC PART #") "C21189") (field (name "Comment") "0603WAF0000T5E"))
      (libsource (lib "JLC_PCB") (part "0603WAF0000T5E"))
    )
    (comp (ref "RC_246")
      (value "0R")
      (footprint "R_0603")
      (description "R - RESISTOR - SMD - 0R - 1% - 0603")
      (fields (field (name "LCSC PART #") "C21189") (field (name "Comment") "0603WAF0000T5E"))
      (libsource (lib "JLC_PCB") (part "0603WAF0000T5E"))
    )
    (comp (ref "RC_247")
      (value "0R")
      (footprint "R_0603")
      (description "R - RESISTOR - SMD - 0R - 1% - 0603")
      (fields (field (name "LCSC PART #") "C21189") (field (name "Comment") "0603WAF0000T5E"))
      (libsource (lib "JLC_PCB") (part "0603WAF0000T5E"))
    )
    (comp (ref "RC_248")
      (value "0R")
      (footprint "R_0603")
      (description "R - RESISTOR - SMD - 0R - 1% - 0603")
      (fields (field (name "LCSC PART #") "C21189") (field (name "Comment") "0603WAF0000T5E"))
      (libsource (lib "JLC_PCB") (part "0603WAF0000T5E"))
    )
    (comp (ref "RC_249")
      (value "0R")
      (footprint "R_0603")
      (description "R - RESISTOR - SMD - 0R - 1% - 0603")
      (fields (field (name "LCSC PART #") "C21189") (field (name "Comment") "0603WAF0000T5E"))
      (libsource (lib "JLC_PCB") (part "0603WAF0000T5E"))
    )
    (comp (ref "RC_250")
      (value "0R")
      (footprint "R_0603")
      (description "R - RESISTOR - SMD - 0R - 1% - 0603")
      (fields (field (name "LCSC PART #") "C21189") (field (name "Comment") "0603WAF0000T5E"))
      (libsource (lib "JLC_PCB") (part "0603WAF0000T5E"))
    )
    (comp (ref "RC_251")
      (value "0R")
      (footprint "R_0603")
      (description "R - RESISTOR - SMD - 0R - 1% - 0603")
      (fields (field (name "LCSC PART #") "C21189") (field (name "Comment") "0603WAF0000T5E"))
      (libsource (lib "JLC_PCB") (part "0603WAF0000T5E"))
    )
    (comp (ref "RC_252")
      (value "0R")
      (footprint "R_0603")
      (description "R - RESISTOR - SMD - 0R - 1% - 0603")
      (fields (field (name "LCSC PART #") "C21189") (field (name "Comment") "0603WAF0000T5E"))
      (libsource (lib "JLC_PCB") (part "0603WAF0000T5E"))
    )
    (comp (ref "RC_253")
      (value "0R")
      (footprint "R_0603")
      (description "R - RESISTOR - SMD - 0R - 1% - 0603")
      (fields (field (name "LCSC PART #") "C21189") (field (name "Comment") "0603WAF0000T5E"))
      (libsource (lib "JLC_PCB") (part "0603WAF0000T5E"))
    )
    (comp (ref "RC_254")
      (value "0R")
      (footprint "R_0603")
      (description "R - RESISTOR - SMD - 0R - 1% - 0603")
      (fields (field (name "LCSC PART #") "C21189") (field (name "Comment") "0603WAF0000T5E"))
      (libsource (lib "JLC_PCB") (part "0603WAF0000T5E"))
    )
    (comp (ref "RC_255")
      (value "0R")
      (footprint "R_0603")
      (description "R - RESISTOR - SMD - 0R - 1% - 0603")
      (fields (field (name "LCSC PART #") "C21189") (field (name "Comment") "0603WAF0000T5E"))
      (libsource (lib "JLC_PCB") (part "0603WAF0000T5E"))
    )
    (comp (ref "RC_256")
      (value "0R")
      (footprint "R_0603")
      (description "R - RESISTOR - SMD - 0R - 1% - 0603")
      (fields (field (name "LCSC PART #") "C21189") (field (name "Comment") "0603WAF0000T5E"))
      (libsource (lib "JLC_PCB") (part "0603WAF0000T5E"))
    )
    (comp (ref "RC_257")
      (value "0R")
      (footprint "R_0603")
      (description "R - RESISTOR - SMD - 0R - 1% - 0603")
      (fields (field (name "LCSC PART #") "C21189") (field (name "Comment") "0603WAF0000T5E"))
      (libsource (lib "JLC_PCB") (part "0603WAF0000T5E"))
    )
    (comp (ref "RC_258")
      (value "0R")
      (footprint "R_0603")
      (description "R - RESISTOR - SMD - 0R - 1% - 0603")
      (fields (field (name "LCSC PART #") "C21189") (field (name "Comment") "0603WAF0000T5E"))
      (libsource (lib "JLC_PCB") (part "0603WAF0000T5E"))
    )
    (comp (ref "RC_259")
      (value "0R")
      (footprint "R_0603")
      (description "R - RESISTOR - SMD - 0R - 1% - 0603")
      (fields (field (name "LCSC PART #") "C21189") (field (name "Comment") "0603WAF0000T5E"))
      (libsource (lib "JLC_PCB") (part "0603WAF0000T5E"))
    )
    (comp (ref "RC_260")
      (value "0R")
      (footprint "R_0603")
      (description "R - RESISTOR - SMD - 0R - 1% - 0603")
      (fields (field (name "LCSC PART #") "C21189") (field (name "Comment") "0603WAF0000T5E"))
      (libsource (lib "JLC_PCB") (part "0603WAF0000T5E"))
    )
    (comp (ref "RC_261")
      (value "0R")
      (footprint "R_0603")
      (description "R - RESISTOR - SMD - 0R - 1% - 0603")
      (fields (field (name "LCSC PART #") "C21189") (field (name "Comment") "0603WAF0000T5E"))
      (libsource (lib "JLC_PCB") (part "0603WAF0000T5E"))
    )
    (comp (ref "RC_262")
      (value "0R")
      (footprint "R_0603")
      (description "R - RESISTOR - SMD - 0R - 1% - 0603")
      (fields (field (name "LCSC PART #") "C21189") (field (name "Comment") "0603WAF0000T5E"))
      (libsource (lib "JLC_PCB") (part "0603WAF0000T5E"))
    )
    (comp (ref "RC_263")
      (value "0R")
      (footprint "R_0603")
      (description "R - RESISTOR - SMD - 0R - 1% - 0603")
      (fields (field (name "LCSC PART #") "C21189") (field (name "Comment") "0603WAF0000T5E"))
      (libsource (lib "JLC_PCB") (part "0603WAF0000T5E"))
    )
    (comp (ref "RC_264")
      (value "0R")
      (footprint "R_0603")
      (description "R - RESISTOR - SMD - 0R - 1% - 0603")
      (fields (field (name "LCSC PART #") "C21189") (field (name "Comment") "0603WAF0000T5E"))
      (libsource (lib "JLC_PCB") (part "0603WAF0000T5E"))
    )
    (comp (ref "RC_265")
      (value "0R")
      (footprint "R_0603")
      (description "R - RESISTOR - SMD - 0R - 1% - 0603")
      (fields (field (name "LCSC PART #") "C21189") (field (name "Comment") "0603WAF0000T5E"))
      (libsource (lib "JLC_PCB") (part "0603WAF0000T5E"))
    )
    (comp (ref "RC_266")
      (value "0R")
      (footprint "R_0603")
      (description "R - RESISTOR - SMD - 0R - 1% - 0603")
      (fields (field (name "LCSC PART #") "C21189") (field (name "Comment") "0603WAF0000T5E"))
      (libsource (lib "JLC_PCB") (part "0603WAF0000T5E"))
    )
    (comp (ref "RC_267")
      (value "0R")
      (footprint "R_0603")
      (description "R - RESISTOR - SMD - 0R - 1% - 0603")
      (fields (field (name "LCSC PART #") "C21189") (field (name "Comment") "0603WAF0000T5E"))
      (libsource (lib "JLC_PCB") (part "0603WAF0000T5E"))
    )
    (comp (ref "RC_268")
      (value "0R")
      (footprint "R_0603")
      (description "R - RESISTOR - SMD - 0R - 1% - 0603")
      (fields (field (name "LCSC PART #") "C21189") (field (name "Comment") "0603WAF0000T5E"))
      (libsource (lib "JLC_PCB") (part "0603WAF0000T5E"))
    )
    (comp (ref "RC_269")
      (value "0R")
      (footprint "R_0603")
      (description "R - RESISTOR - SMD - 0R - 1% - 0603")
      (fields (field (name "LCSC PART #") "C21189") (field (name "Comment") "0603WAF0000T5E"))
      (libsource (lib "JLC_PCB") (part "0603WAF0000T5E"))
    )
    (comp (ref "RC_270")
      (value "0R")
      (footprint "R_0603")
      (description "R - RESISTOR - SMD - 0R - 1% - 0603")
      (fields (field (name "LCSC PART #") "C21189") (field (name "Comment") "0603WAF0000T5E"))
      (libsource (lib "JLC_PCB") (part "0603WAF0000T5E"))
    )
    (comp (ref "RC_271")
      (value "0R")
      (footprint "R_0603")
      (description "R - RESISTOR - SMD - 0R - 1% - 0603")
      (fields (field (name "LCSC PART #") "C21189") (field (name "Comment") "0603WAF0000T5E"))
      (libsource (lib "JLC_PCB") (part "0603WAF0000T5E"))
    )
    (comp (ref "RC_272")
      (value "0R")
      (footprint "R_0603")
      (description "R - RESISTOR - SMD - 0R - 1% - 0603")
      (fields (field (name "LCSC PART #") "C21189") (field (name "Comment") "0603WAF0000T5E"))
      (libsource (lib "JLC_PCB") (part "0603WAF0000T5E"))
    )
    (comp (ref "RC_273")
      (value "0R")
      (footprint "R_0603")
      (description "R - RESISTOR - SMD - 0R - 1% - 0603")
      (fields (field (name "LCSC PART #") "C21189") (field (name "Comment") "0603WAF0000T5E"))
      (libsource (lib "JLC_PCB") (part "0603WAF0000T5E"))
    )
    (comp (ref "RC_274")
      (value "0R")
      (footprint "R_0603")
      (description "R - RESISTOR - SMD - 0R - 1% - 0603")
      (fields (field (name "LCSC PART #") "C21189") (field (name "Comment") "0603WAF0000T5E"))
      (libsource (lib "JLC_PCB") (part "0603WAF0000T5E"))
    )
    (comp (ref "RC_275")
      (value "0R")
      (footprint "R_0603")
      (description "R - RESISTOR - SMD - 0R - 1% - 0603")
      (fields (field (name "LCSC PART #") "C21189") (field (name "Comment") "0603WAF0000T5E"))
      (libsource (lib "JLC_PCB") (part "0603WAF0000T5E"))
    )
    (comp (ref "RC_276")
      (value "0R")
      (footprint "R_0603")
      (description "R - RESISTOR - SMD - 0R - 1% - 0603")
      (fields (field (name "LCSC PART #") "C21189") (field (name "Comment") "0603WAF0000T5E"))
      (libsource (lib "JLC_PCB") (part "0603WAF0000T5E"))
    )
    (comp (ref "RC_277")
      (value "0R")
      (footprint "R_0603")
      (description "R - RESISTOR - SMD - 0R - 1% - 0603")
      (fields (field (name "LCSC PART #") "C21189") (field (name "Comment") "0603WAF0000T5E"))
      (libsource (lib "JLC_PCB") (part "0603WAF0000T5E"))
    )
    (comp (ref "RC_278")
      (value "0R")
      (footprint "R_0603")
      (description "R - RESISTOR - SMD - 0R - 1% - 0603")
      (fields (field (name "LCSC PART #") "C21189") (field (name "Comment") "0603WAF0000T5E"))
      (libsource (lib "JLC_PCB") (part "0603WAF0000T5E"))
    )
    (comp (ref "RC_279")
      (value "0R")
      (footprint "R_0603")
      (description "R - RESISTOR - SMD - 0R - 1% - 0603")
      (fields (field (name "LCSC PART #") "C21189") (field (name "Comment") "0603WAF0000T5E"))
      (libsource (lib "JLC_PCB") (part "0603WAF0000T5E"))
    )
    (comp (ref "RC_280")
      (value "0R")
      (footprint "R_0603")
      (description "R - RESISTOR - SMD - 0R - 1% - 0603")
      (fields (field (name "LCSC PART #") "C21189") (field (name "Comment") "0603WAF0000T5E"))
      (libsource (lib "JLC_PCB") (part "0603WAF0000T5E"))
    )
    (comp (ref "RC_281")
      (value "0R")
      (footprint "R_0603")
      (description "R - RESISTOR - SMD - 0R - 1% - 0603")
      (fields (field (name "LCSC PART #") "C21189") (field (name "Comment") "0603WAF0000T5E"))
      (libsource (lib "JLC_PCB") (part "0603WAF0000T5E"))
    )
    (comp (ref "RC_282")
      (value "0R")
      (footprint "R_0603")
      (description "R - RESISTOR - SMD - 0R - 1% - 0603")
      (fields (field (name "LCSC PART #") "C21189") (field (name "Comment") "0603WAF0000T5E"))
      (libsource (lib "JLC_PCB") (part "0603WAF0000T5E"))
    )
    (comp (ref "RC_283")
      (value "0R")
      (footprint "R_0603")
      (description "R - RESISTOR - SMD - 0R - 1% - 0603")
      (fields (field (name "LCSC PART #") "C21189") (field (name "Comment") "0603WAF0000T5E"))
      (libsource (lib "JLC_PCB") (part "0603WAF0000T5E"))
    )
    (comp (ref "RC_284")
      (value "0R")
      (footprint "R_0603")
      (description "R - RESISTOR - SMD - 0R - 1% - 0603")
      (fields (field (name "LCSC PART #") "C21189") (field (name "Comment") "0603WAF0000T5E"))
      (libsource (lib "JLC_PCB") (part "0603WAF0000T5E"))
    )
    (comp (ref "RC_285")
      (value "0R")
      (footprint "R_0603")
      (description "R - RESISTOR - SMD - 0R - 1% - 0603")
      (fields (field (name "LCSC PART #") "C21189") (field (name "Comment") "0603WAF0000T5E"))
      (libsource (lib "JLC_PCB") (part "0603WAF0000T5E"))
    )
    (comp (ref "RC_286")
      (value "0R")
      (footprint "R_0603")
      (description "R - RESISTOR - SMD - 0R - 1% - 0603")
      (fields (field (name "LCSC PART #") "C21189") (field (name "Comment") "0603WAF0000T5E"))
      (libsource (lib "JLC_PCB") (part "0603WAF0000T5E"))
    )
    (comp (ref "RC_287")
      (value "0R")
      (footprint "R_0603")
      (description "R - RESISTOR - SMD - 0R - 1% - 0603")
      (fields (field (name "LCSC PART #") "C21189") (field (name "Comment") "0603WAF0000T5E"))
      (libsource (lib "JLC_PCB") (part "0603WAF0000T5E"))
    )
    (comp (ref "RC_288")
      (value "0R")
      (footprint "R_0603")
      (description "R - RESISTOR - SMD - 0R - 1% - 0603")
      (fields (field (name "LCSC PART #") "C21189") (field (name "Comment") "0603WAF0000T5E"))
      (libsource (lib "JLC_PCB") (part "0603WAF0000T5E"))
    )
    (comp (ref "RC_289")
      (value "0R")
      (footprint "R_0603")
      (description "R - RESISTOR - SMD - 0R - 1% - 0603")
      (fields (field (name "LCSC PART #") "C21189") (field (name "Comment") "0603WAF0000T5E"))
      (libsource (lib "JLC_PCB") (part "0603WAF0000T5E"))
    )
    (comp (ref "RC_290")
      (value "0R")
      (footprint "R_0603")
      (description "R - RESISTOR - SMD - 0R - 1% - 0603")
      (fields (field (name "LCSC PART #") "C21189") (field (name "Comment") "0603WAF0000T5E"))
      (libsource (lib "JLC_PCB") (part "0603WAF0000T5E"))
    )
    (comp (ref "RC_291")
      (value "0R")
      (footprint "R_0603")
      (description "R - RESISTOR - SMD - 0R - 1% - 0603")
      (fields (field (name "LCSC PART #") "C21189") (field (name "Comment") "0603WAF0000T5E"))
      (libsource (lib "JLC_PCB") (part "0603WAF0000T5E"))
    )
    (comp (ref "RC_292")
      (value "0R")
      (footprint "R_0603")
      (description "R - RESISTOR - SMD - 0R - 1% - 0603")
      (fields (field (name "LCSC PART #") "C21189") (field (name "Comment") "0603WAF0000T5E"))
      (libsource (lib "JLC_PCB") (part "0603WAF0000T5E"))
    )
    (comp (ref "RC_293")
      (value "0R")
      (footprint "R_0603")
      (description "R - RESISTOR - SMD - 0R - 1% - 0603")
      (fields (field (name "LCSC PART #") "C21189") (field (name "Comment") "0603WAF0000T5E"))
      (libsource (lib "JLC_PCB") (part "0603WAF0000T5E"))
    )
    (comp (ref "RC_294")
      (value "0R")
      (footprint "R_0603")
      (description "R - RESISTOR - SMD - 0R - 1% - 0603")
      (fields (field (name "LCSC PART #") "C21189") (field (name "Comment") "0603WAF0000T5E"))
      (libsource (lib "JLC_PCB") (part "0603WAF0000T5E"))
    )
    (comp (ref "RC_295")
      (value "0R")
      (footprint "R_0603")
      (description "R - RESISTOR - SMD - 0R - 1% - 0603")
      (fields (field (name "LCSC PART #") "C21189") (field (name "Comment") "0603WAF0000T5E"))
      (libsource (lib "JLC_PCB") (part "0603WAF0000T5E"))
    )
    (comp (ref "RC_296")
      (value "0R")
      (footprint "R_0603")
      (description "R - RESISTOR - SMD - 0R - 1% - 0603")
      (fields (field (name "LCSC PART #") "C21189") (field (name "Comment") "0603WAF0000T5E"))
      (libsource (lib "JLC_PCB") (part "0603WAF0000T5E"))
    )
    (comp (ref "RC_297")
      (value "0R")
      (footprint "R_0603")
      (description "R - RESISTOR - SMD - 0R - 1% - 0603")
      (fields (field (name "LCSC PART #") "C21189") (field (name "Comment") "0603WAF0000T5E"))
      (libsource (lib "JLC_PCB") (part "0603WAF0000T5E"))
    )
    (comp (ref "RC_298")
      (value "0R")
      (footprint "R_0603")
      (description "R - RESISTOR - SMD - 0R - 1% - 0603")
      (fields (field (name "LCSC PART #") "C21189") (field (name "Comment") "0603WAF0000T5E"))
      (libsource (lib "JLC_PCB") (part "0603WAF0000T5E"))
    )
    (comp (ref "RC_299")
      (value "0R")
      (footprint "R_0603")
      (description "R - RESISTOR - SMD - 0R - 1% - 0603")
      (fields (field (name "LCSC PART #") "C21189") (field (name "Comment") "0603WAF0000T5E"))
      (libsource (lib "JLC_PCB") (part "0603WAF0000T5E"))
    )
    (comp (ref "RC_300")
      (value "0R")
      (footprint "R_0603")
      (description "R - RESISTOR - SMD - 0R - 1% - 0603")
      (fields (field (name "LCSC PART #") "C21189") (field (name "Comment") "0603WAF0000T5E"))
      (libsource (lib "JLC_PCB") (part "0603WAF0000T5E"))
    )
    (comp (ref "RC_301")
      (value "0R")
      (footprint "R_0603")
      (description "R - RESISTOR - SMD - 0R - 1% - 0603")
      (fields (field (name "LCSC PART #") "C21189") (field (name "Comment") "0603WAF0000T5E"))
      (libsource (lib "JLC_PCB") (part "0603WAF0000T5E"))
    )
    (comp (ref "RC_302")
      (value "0R")
      (footprint "R_0603")
      (description "R - RESISTOR - SMD - 0R - 1% - 0603")
      (fields (field (name "LCSC PART #") "C21189") (field (name "Comment") "0603WAF0000T5E"))
      (libsource (lib "JLC_PCB") (part "0603WAF0000T5E"))
    )
    (comp (ref "RC_303")
      (value "0R")
      (footprint "R_0603")
      (description "R - RESISTOR - SMD - 0R - 1% - 0603")
      (fields (field (name "LCSC PART #") "C21189") (field (name "Comment") "0603WAF0000T5E"))
      (libsource (lib "JLC_PCB") (part "0603WAF0000T5E"))
    )
    (comp (ref "RC_304")
      (value "0R")
      (footprint "R_0603")
      (description "R - RESISTOR - SMD - 0R - 1% - 0603")
      (fields (field (name "LCSC PART #") "C21189") (field (name "Comment") "0603WAF0000T5E"))
      (libsource (lib "JLC_PCB") (part "0603WAF0000T5E"))
    )
    (comp (ref "RC_305")
      (value "0R")
      (footprint "R_0603")
      (description "R - RESISTOR - SMD - 0R - 1% - 0603")
      (fields (field (name "LCSC PART #") "C21189") (field (name "Comment") "0603WAF0000T5E"))
      (libsource (lib "JLC_PCB") (part "0603WAF0000T5E"))
    )
    (comp (ref "RC_306")
      (value "0R")
      (footprint "R_0603")
      (description "R - RESISTOR - SMD - 0R - 1% - 0603")
      (fields (field (name "LCSC PART #") "C21189") (field (name "Comment") "0603WAF0000T5E"))
      (libsource (lib "JLC_PCB") (part "0603WAF0000T5E"))
    )
    (comp (ref "RC_307")
      (value "0R")
      (footprint "R_0603")
      (description "R - RESISTOR - SMD - 0R - 1% - 0603")
      (fields (field (name "LCSC PART #") "C21189") (field (name "Comment") "0603WAF0000T5E"))
      (libsource (lib "JLC_PCB") (part "0603WAF0000T5E"))
    )
    (comp (ref "RC_308")
      (value "0R")
      (footprint "R_0603")
      (description "R - RESISTOR - SMD - 0R - 1% - 0603")
      (fields (field (name "LCSC PART #") "C21189") (field (name "Comment") "0603WAF0000T5E"))
      (libsource (lib "JLC_PCB") (part "0603WAF0000T5E"))
    )
    (comp (ref "RC_309")
      (value "0R")
      (footprint "R_0603")
      (description "R - RESISTOR - SMD - 0R - 1% - 0603")
      (fields (field (name "LCSC PART #") "C21189") (field (name "Comment") "0603WAF0000T5E"))
      (libsource (lib "JLC_PCB") (part "0603WAF0000T5E"))
    )
    (comp (ref "RC_310")
      (value "0R")
      (footprint "R_0603")
      (description "R - RESISTOR - SMD - 0R - 1% - 0603")
      (fields (field (name "LCSC PART #") "C21189") (field (name "Comment") "0603WAF0000T5E"))
      (libsource (lib "JLC_PCB") (part "0603WAF0000T5E"))
    )
    (comp (ref "RC_311")
      (value "0R")
      (footprint "R_0603")
      (description "R - RESISTOR - SMD - 0R - 1% - 0603")
      (fields (field (name "LCSC PART #") "C21189") (field (name "Comment") "0603WAF0000T5E"))
      (libsource (lib "JLC_PCB") (part "0603WAF0000T5E"))
    )
    (comp (ref "RC_312")
      (value "0R")
      (footprint "R_0603")
      (description "R - RESISTOR - SMD - 0R - 1% - 0603")
      (fields (field (name "LCSC PART #") "C21189") (field (name "Comment") "0603WAF0000T5E"))
      (libsource (lib "JLC_PCB") (part "0603WAF0000T5E"))
    )
    (comp (ref "RC_313")
      (value "0R")
      (footprint "R_0603")
      (description "R - RESISTOR - SMD - 0R - 1% - 0603")
      (fields (field (name "LCSC PART #") "C21189") (field (name "Comment") "0603WAF0000T5E"))
      (libsource (lib "JLC_PCB") (part "0603WAF0000T5E"))
    )
    (comp (ref "RC_314")
      (value "0R")
      (footprint "R_0603")
      (description "R - RESISTOR - SMD - 0R - 1% - 0603")
      (fields (field (name "LCSC PART #") "C21189") (field (name "Comment") "0603WAF0000T5E"))
      (libsource (lib "JLC_PCB") (part "0603WAF0000T5E"))
    )
    (comp (ref "RC_315")
      (value "0R")
      (footprint "R_0603")
      (description "R - RESISTOR - SMD - 0R - 1% - 0603")
      (fields (field (name "LCSC PART #") "C21189") (field (name "Comment") "0603WAF0000T5E"))
      (libsource (lib "JLC_PCB") (part "0603WAF0000T5E"))
    )
    (comp (ref "RC_316")
      (value "0R")
      (footprint "R_0603")
      (description "R - RESISTOR - SMD - 0R - 1% - 0603")
      (fields (field (name "LCSC PART #") "C21189") (field (name "Comment") "0603WAF0000T5E"))
      (libsource (lib "JLC_PCB") (part "0603WAF0000T5E"))
    )
    (comp (ref "RC_317")
      (value "0R")
      (footprint "R_0603")
      (description "R - RESISTOR - SMD - 0R - 1% - 0603")
      (fields (field (name "LCSC PART #") "C21189") (field (name "Comment") "0603WAF0000T5E"))
      (libsource (lib "JLC_PCB") (part "0603WAF0000T5E"))
    )
    (comp (ref "RC_318")
      (value "0R")
      (footprint "R_0603")
      (description "R - RESISTOR - SMD - 0R - 1% - 0603")
      (fields (field (name "LCSC PART #") "C21189") (field (name "Comment") "0603WAF0000T5E"))
      (libsource (lib "JLC_PCB") (part "0603WAF0000T5E"))
    )
    (comp (ref "RC_319")
      (value "0R")
      (footprint "R_0603")
      (description "R - RESISTOR - SMD - 0R - 1% - 0603")
      (fields (field (name "LCSC PART #") "C21189") (field (name "Comment") "0603WAF0000T5E"))
      (libsource (lib "JLC_PCB") (part "0603WAF0000T5E"))
    )
    (comp (ref "RC_320")
      (value "0R")
      (footprint "R_0603")
      (description "R - RESISTOR - SMD - 0R - 1% - 0603")
      (fields (field (name "LCSC PART #") "C21189") (field (name "Comment") "0603WAF0000T5E"))
      (libsource (lib "JLC_PCB") (part "0603WAF0000T5E"))
    )
    (comp (ref "RC_321")
      (value "0R")
      (footprint "R_0603")
      (description "R - RESISTOR - SMD - 0R - 1% - 0603")
      (fields (field (name "LCSC PART #") "C21189") (field (name "Comment") "0603WAF0000T5E"))
      (libsource (lib "JLC_PCB") (part "0603WAF0000T5E"))
    )
    (comp (ref "RC_322")
      (value "0R")
      (footprint "R_0603")
      (description "R - RESISTOR - SMD - 0R - 1% - 0603")
      (fields (field (name "LCSC PART #") "C21189") (field (name "Comment") "0603WAF0000T5E"))
      (libsource (lib "JLC_PCB") (part "0603WAF0000T5E"))
    )
    (comp (ref "RC_323")
      (value "0R")
      (footprint "R_0603")
      (description "R - RESISTOR - SMD - 0R - 1% - 0603")
      (fields (field (name "LCSC PART #") "C21189") (field (name "Comment") "0603WAF0000T5E"))
      (libsource (lib "JLC_PCB") (part "0603WAF0000T5E"))
    )
    (comp (ref "RC_324")
      (value "0R")
      (footprint "R_0603")
      (description "R - RESISTOR - SMD - 0R - 1% - 0603")
      (fields (field (name "LCSC PART #") "C21189") (field (name "Comment") "0603WAF0000T5E"))
      (libsource (lib "JLC_PCB") (part "0603WAF0000T5E"))
    )
    (comp (ref "RC_325")
      (value "0R")
      (footprint "R_0603")
      (description "R - RESISTOR - SMD - 0R - 1% - 0603")
      (fields (field (name "LCSC PART #") "C21189") (field (name "Comment") "0603WAF0000T5E"))
      (libsource (lib "JLC_PCB") (part "0603WAF0000T5E"))
    )
    (comp (ref "RC_326")
      (value "0R")
      (footprint "R_0603")
      (description "R - RESISTOR - SMD - 0R - 1% - 0603")
      (fields (field (name "LCSC PART #") "C21189") (field (name "Comment") "0603WAF0000T5E"))
      (libsource (lib "JLC_PCB") (part "0603WAF0000T5E"))
    )
    (comp (ref "RC_327")
      (value "0R")
      (footprint "R_0603")
      (description "R - RESISTOR - SMD - 0R - 1% - 0603")
      (fields (field (name "LCSC PART #") "C21189") (field (name "Comment") "0603WAF0000T5E"))
      (libsource (lib "JLC_PCB") (part "0603WAF0000T5E"))
    )
    (comp (ref "RC_328")
      (value "0R")
      (footprint "R_0603")
      (description "R - RESISTOR - SMD - 0R - 1% - 0603")
      (fields (field (name "LCSC PART #") "C21189") (field (name "Comment") "0603WAF0000T5E"))
      (libsource (lib "JLC_PCB") (part "0603WAF0000T5E"))
    )
    (comp (ref "RC_329")
      (value "0R")
      (footprint "R_0603")
      (description "R - RESISTOR - SMD - 0R - 1% - 0603")
      (fields (field (name "LCSC PART #") "C21189") (field (name "Comment") "0603WAF0000T5E"))
      (libsource (lib "JLC_PCB") (part "0603WAF0000T5E"))
    )
    (comp (ref "RC_330")
      (value "0R")
      (footprint "R_0603")
      (description "R - RESISTOR - SMD - 0R - 1% - 0603")
      (fields (field (name "LCSC PART #") "C21189") (field (name "Comment") "0603WAF0000T5E"))
      (libsource (lib "JLC_PCB") (part "0603WAF0000T5E"))
    )
    (comp (ref "RC_331")
      (value "0R")
      (footprint "R_0603")
      (description "R - RESISTOR - SMD - 0R - 1% - 0603")
      (fields (field (name "LCSC PART #") "C21189") (field (name "Comment") "0603WAF0000T5E"))
      (libsource (lib "JLC_PCB") (part "0603WAF0000T5E"))
    )
    (comp (ref "RC_332")
      (value "0R")
      (footprint "R_0603")
      (description "R - RESISTOR - SMD - 0R - 1% - 0603")
      (fields (field (name "LCSC PART #") "C21189") (field (name "Comment") "0603WAF0000T5E"))
      (libsource (lib "JLC_PCB") (part "0603WAF0000T5E"))
    )
    (comp (ref "RC_333")
      (value "0R")
      (footprint "R_0603")
      (description "R - RESISTOR - SMD - 0R - 1% - 0603")
      (fields (field (name "LCSC PART #") "C21189") (field (name "Comment") "0603WAF0000T5E"))
      (libsource (lib "JLC_PCB") (part "0603WAF0000T5E"))
    )
    (comp (ref "RC_334")
      (value "0R")
      (footprint "R_0603")
      (description "R - RESISTOR - SMD - 0R - 1% - 0603")
      (fields (field (name "LCSC PART #") "C21189") (field (name "Comment") "0603WAF0000T5E"))
      (libsource (lib "JLC_PCB") (part "0603WAF0000T5E"))
    )
    (comp (ref "RC_335")
      (value "0R")
      (footprint "R_0603")
      (description "R - RESISTOR - SMD - 0R - 1% - 0603")
      (fields (field (name "LCSC PART #") "C21189") (field (name "Comment") "0603WAF0000T5E"))
      (libsource (lib "JLC_PCB") (part "0603WAF0000T5E"))
    )
    (comp (ref "RC_336")
      (value "0R")
      (footprint "R_0603")
      (description "R - RESISTOR - SMD - 0R - 1% - 0603")
      (fields (field (name "LCSC PART #") "C21189") (field (name "Comment") "0603WAF0000T5E"))
      (libsource (lib "JLC_PCB") (part "0603WAF0000T5E"))
    )
    (comp (ref "RC_337")
      (value "0R")
      (footprint "R_0603")
      (description "R - RESISTOR - SMD - 0R - 1% - 0603")
      (fields (field (name "LCSC PART #") "C21189") (field (name "Comment") "0603WAF0000T5E"))
      (libsource (lib "JLC_PCB") (part "0603WAF0000T5E"))
    )
    (comp (ref "RC_338")
      (value "0R")
      (footprint "R_0603")
      (description "R - RESISTOR - SMD - 0R - 1% - 0603")
      (fields (field (name "LCSC PART #") "C21189") (field (name "Comment") "0603WAF0000T5E"))
      (libsource (lib "JLC_PCB") (part "0603WAF0000T5E"))
    )
    (comp (ref "RC_339")
      (value "0R")
      (footprint "R_0603")
      (description "R - RESISTOR - SMD - 0R - 1% - 0603")
      (fields (field (name "LCSC PART #") "C21189") (field (name "Comment") "0603WAF0000T5E"))
      (libsource (lib "JLC_PCB") (part "0603WAF0000T5E"))
    )
    (comp (ref "RC_340")
      (value "0R")
      (footprint "R_0603")
      (description "R - RESISTOR - SMD - 0R - 1% - 0603")
      (fields (field (name "LCSC PART #") "C21189") (field (name "Comment") "0603WAF0000T5E"))
      (libsource (lib "JLC_PCB") (part "0603WAF0000T5E"))
    )
    (comp (ref "RC_341")
      (value "0R")
      (footprint "R_0603")
      (description "R - RESISTOR - SMD - 0R - 1% - 0603")
      (fields (field (name "LCSC PART #") "C21189") (field (name "Comment") "0603WAF0000T5E"))
      (libsource (lib "JLC_PCB") (part "0603WAF0000T5E"))
    )
    (comp (ref "RC_342")
      (value "0R")
      (footprint "R_0603")
      (description "R - RESISTOR - SMD - 0R - 1% - 0603")
      (fields (field (name "LCSC PART #") "C21189") (field (name "Comment") "0603WAF0000T5E"))
      (libsource (lib "JLC_PCB") (part "0603WAF0000T5E"))
    )
    (comp (ref "RC_343")
      (value "0R")
      (footprint "R_0603")
      (description "R - RESISTOR - SMD - 0R - 1% - 0603")
      (fields (field (name "LCSC PART #") "C21189") (field (name "Comment") "0603WAF0000T5E"))
      (libsource (lib "JLC_PCB") (part "0603WAF0000T5E"))
    )
    (comp (ref "RC_344")
      (value "0R")
      (footprint "R_0603")
      (description "R - RESISTOR - SMD - 0R - 1% - 0603")
      (fields (field (name "LCSC PART #") "C21189") (field (name "Comment") "0603WAF0000T5E"))
      (libsource (lib "JLC_PCB") (part "0603WAF0000T5E"))
    )
    (comp (ref "RC_345")
      (value "0R")
      (footprint "R_0603")
      (description "R - RESISTOR - SMD - 0R - 1% - 0603")
      (fields (field (name "LCSC PART #") "C21189") (field (name "Comment") "0603WAF0000T5E"))
      (libsource (lib "JLC_PCB") (part "0603WAF0000T5E"))
    )
    (comp (ref "RC_346")
      (value "0R")
      (footprint "R_0603")
      (description "R - RESISTOR - SMD - 0R - 1% - 0603")
      (fields (field (name "LCSC PART #") "C21189") (field (name "Comment") "0603WAF0000T5E"))
      (libsource (lib "JLC_PCB") (part "0603WAF0000T5E"))
    )
    (comp (ref "RC_347")
      (value "0R")
      (footprint "R_0603")
      (description "R - RESISTOR - SMD - 0R - 1% - 0603")
      (fields (field (name "LCSC PART #") "C21189") (field (name "Comment") "0603WAF0000T5E"))
      (libsource (lib "JLC_PCB") (part "0603WAF0000T5E"))
    )
    (comp (ref "RC_348")
      (value "0R")
      (footprint "R_0603")
      (description "R - RESISTOR - SMD - 0R - 1% - 0603")
      (fields (field (name "LCSC PART #") "C21189") (field (name "Comment") "0603WAF0000T5E"))
      (libsource (lib "JLC_PCB") (part "0603WAF0000T5E"))
    )
    (comp (ref "RC_349")
      (value "0R")
      (footprint "R_0603")
      (description "R - RESISTOR - SMD - 0R - 1% - 0603")
      (fields (field (name "LCSC PART #") "C21189") (field (name "Comment") "0603WAF0000T5E"))
      (libsource (lib "JLC_PCB") (part "0603WAF0000T5E"))
    )
    (comp (ref "RC_350")
      (value "0R")
      (footprint "R_0603")
      (description "R - RESISTOR - SMD - 0R - 1% - 0603")
      (fields (field (name "LCSC PART #") "C21189") (field (name "Comment") "0603WAF0000T5E"))
      (libsource (lib "JLC_PCB") (part "0603WAF0000T5E"))
    )
    (comp (ref "RC_351")
      (value "0R")
      (footprint "R_0603")
      (description "R - RESISTOR - SMD - 0R - 1% - 0603")
      (fields (field (name "LCSC PART #") "C21189") (field (name "Comment") "0603WAF0000T5E"))
      (libsource (lib "JLC_PCB") (part "0603WAF0000T5E"))
    )
    (comp (ref "RC_352")
      (value "0R")
      (footprint "R_0603")
      (description "R - RESISTOR - SMD - 0R - 1% - 0603")
      (fields (field (name "LCSC PART #") "C21189") (field (name "Comment") "0603WAF0000T5E"))
      (libsource (lib "JLC_PCB") (part "0603WAF0000T5E"))
    )
    (comp (ref "RC_353")
      (value "0R")
      (footprint "R_0603")
      (description "R - RESISTOR - SMD - 0R - 1% - 0603")
      (fields (field (name "LCSC PART #") "C21189") (field (name "Comment") "0603WAF0000T5E"))
      (libsource (lib "JLC_PCB") (part "0603WAF0000T5E"))
    )
    (comp (ref "RC_354")
      (value "0R")
      (footprint "R_0603")
      (description "R - RESISTOR - SMD - 0R - 1% - 0603")
      (fields (field (name "LCSC PART #") "C21189") (field (name "Comment") "0603WAF0000T5E"))
      (libsource (lib "JLC_PCB") (part "0603WAF0000T5E"))
    )
    (comp (ref "RC_355")
      (value "0R")
      (footprint "R_0603")
      (description "R - RESISTOR - SMD - 0R - 1% - 0603")
      (fields (field (name "LCSC PART #") "C21189") (field (name "Comment") "0603WAF0000T5E"))
      (libsource (lib "JLC_PCB") (part "0603WAF0000T5E"))
    )
    (comp (ref "RC_356")
      (value "0R")
      (footprint "R_0603")
      (description "R - RESISTOR - SMD - 0R - 1% - 0603")
      (fields (field (name "LCSC PART #") "C21189") (field (name "Comment") "0603WAF0000T5E"))
      (libsource (lib "JLC_PCB") (part "0603WAF0000T5E"))
    )
    (comp (ref "RC_357")
      (value "0R")
      (footprint "R_0603")
      (description "R - RESISTOR - SMD - 0R - 1% - 0603")
      (fields (field (name "LCSC PART #") "C21189") (field (name "Comment") "0603WAF0000T5E"))
      (libsource (lib "JLC_PCB") (part "0603WAF0000T5E"))
    )
    (comp (ref "RC_358")
      (value "0R")
      (footprint "R_0603")
      (description "R - RESISTOR - SMD - 0R - 1% - 0603")
      (fields (field (name "LCSC PART #") "C21189") (field (name "Comment") "0603WAF0000T5E"))
      (libsource (lib "JLC_PCB") (part "0603WAF0000T5E"))
    )
    (comp (ref "RC_359")
      (value "0R")
      (footprint "R_0603")
      (description "R - RESISTOR - SMD - 0R - 1% - 0603")
      (fields (field (name "LCSC PART #") "C21189") (field (name "Comment") "0603WAF0000T5E"))
      (libsource (lib "JLC_PCB") (part "0603WAF0000T5E"))
    )
    (comp (ref "RC_360")
      (value "0R")
      (footprint "R_0603")
      (description "R - RESISTOR - SMD - 0R - 1% - 0603")
      (fields (field (name "LCSC PART #") "C21189") (field (name "Comment") "0603WAF0000T5E"))
      (libsource (lib "JLC_PCB") (part "0603WAF0000T5E"))
    )
    (comp (ref "RC_361")
      (value "0R")
      (footprint "R_0603")
      (description "R - RESISTOR - SMD - 0R - 1% - 0603")
      (fields (field (name "LCSC PART #") "C21189") (field (name "Comment") "0603WAF0000T5E"))
      (libsource (lib "JLC_PCB") (part "0603WAF0000T5E"))
    )
    (comp (ref "RC_362")
      (value "0R")
      (footprint "R_0603")
      (description "R - RESISTOR - SMD - 0R - 1% - 0603")
      (fields (field (name "LCSC PART #") "C21189") (field (name "Comment") "0603WAF0000T5E"))
      (libsource (lib "JLC_PCB") (part "0603WAF0000T5E"))
    )
    (comp (ref "RC_363")
      (value "0R")
      (footprint "R_0603")
      (description "R - RESISTOR - SMD - 0R - 1% - 0603")
      (fields (field (name "LCSC PART #") "C21189") (field (name "Comment") "0603WAF0000T5E"))
      (libsource (lib "JLC_PCB") (part "0603WAF0000T5E"))
    )
    (comp (ref "RC_364")
      (value "0R")
      (footprint "R_0603")
      (description "R - RESISTOR - SMD - 0R - 1% - 0603")
      (fields (field (name "LCSC PART #") "C21189") (field (name "Comment") "0603WAF0000T5E"))
      (libsource (lib "JLC_PCB") (part "0603WAF0000T5E"))
    )
    (comp (ref "RC_365")
      (value "0R")
      (footprint "R_0603")
      (description "R - RESISTOR - SMD - 0R - 1% - 0603")
      (fields (field (name "LCSC PART #") "C21189") (field (name "Comment") "0603WAF0000T5E"))
      (libsource (lib "JLC_PCB") (part "0603WAF0000T5E"))
    )
    (comp (ref "RC_366")
      (value "0R")
      (footprint "R_0603")
      (description "R - RESISTOR - SMD - 0R - 1% - 0603")
      (fields (field (name "LCSC PART #") "C21189") (field (name "Comment") "0603WAF0000T5E"))
      (libsource (lib "JLC_PCB") (part "0603WAF0000T5E"))
    )
    (comp (ref "RC_367")
      (value "0R")
      (footprint "R_0603")
      (description "R - RESISTOR - SMD - 0R - 1% - 0603")
      (fields (field (name "LCSC PART #") "C21189") (field (name "Comment") "0603WAF0000T5E"))
      (libsource (lib "JLC_PCB") (part "0603WAF0000T5E"))
    )
    (comp (ref "RC_368")
      (value "0R")
      (footprint "R_0603")
      (description "R - RESISTOR - SMD - 0R - 1% - 0603")
      (fields (field (name "LCSC PART #") "C21189") (field (name "Comment") "0603WAF0000T5E"))
      (libsource (lib "JLC_PCB") (part "0603WAF0000T5E"))
    )
    (comp (ref "RC_369")
      (value "0R")
      (footprint "R_0603")
      (description "R - RESISTOR - SMD - 0R - 1% - 0603")
      (fields (field (name "LCSC PART #") "C21189") (field (name "Comment") "0603WAF0000T5E"))
      (libsource (lib "JLC_PCB") (part "0603WAF0000T5E"))
    )
    (comp (ref "RC_370")
      (value "0R")
      (footprint "R_0603")
      (description "R - RESISTOR - SMD - 0R - 1% - 0603")
      (fields (field (name "LCSC PART #") "C21189") (field (name "Comment") "0603WAF0000T5E"))
      (libsource (lib "JLC_PCB") (part "0603WAF0000T5E"))
    )
    (comp (ref "RC_371")
      (value "0R")
      (footprint "R_0603")
      (description "R - RESISTOR - SMD - 0R - 1% - 0603")
      (fields (field (name "LCSC PART #") "C21189") (field (name "Comment") "0603WAF0000T5E"))
      (libsource (lib "JLC_PCB") (part "0603WAF0000T5E"))
    )
    (comp (ref "RC_372")
      (value "0R")
      (footprint "R_0603")
      (description "R - RESISTOR - SMD - 0R - 1% - 0603")
      (fields (field (name "LCSC PART #") "C21189") (field (name "Comment") "0603WAF0000T5E"))
      (libsource (lib "JLC_PCB") (part "0603WAF0000T5E"))
    )
    (comp (ref "RC_373")
      (value "0R")
      (footprint "R_0603")
      (description "R - RESISTOR - SMD - 0R - 1% - 0603")
      (fields (field (name "LCSC PART #") "C21189") (field (name "Comment") "0603WAF0000T5E"))
      (libsource (lib "JLC_PCB") (part "0603WAF0000T5E"))
    )
    (comp (ref "RC_374")
      (value "0R")
      (footprint "R_0603")
      (description "R - RESISTOR - SMD - 0R - 1% - 0603")
      (fields (field (name "LCSC PART #") "C21189") (field (name "Comment") "0603WAF0000T5E"))
      (libsource (lib "JLC_PCB") (part "0603WAF0000T5E"))
    )
    (comp (ref "RC_375")
      (value "0R")
      (footprint "R_0603")
      (description "R - RESISTOR - SMD - 0R - 1% - 0603")
      (fields (field (name "LCSC PART #") "C21189") (field (name "Comment") "0603WAF0000T5E"))
      (libsource (lib "JLC_PCB") (part "0603WAF0000T5E"))
    )
    (comp (ref "RC_376")
      (value "0R")
      (footprint "R_0603")
      (description "R - RESISTOR - SMD - 0R - 1% - 0603")
      (fields (field (name "LCSC PART #") "C21189") (field (name "Comment") "0603WAF0000T5E"))
      (libsource (lib "JLC_PCB") (part "0603WAF0000T5E"))
    )
    (comp (ref "RC_377")
      (value "0R")
      (footprint "R_0603")
      (description "R - RESISTOR - SMD - 0R - 1% - 0603")
      (fields (field (name "LCSC PART #") "C21189") (field (name "Comment") "0603WAF0000T5E"))
      (libsource (lib "JLC_PCB") (part "0603WAF0000T5E"))
    )
    (comp (ref "RC_378")
      (value "0R")
      (footprint "R_0603")
      (description "R - RESISTOR - SMD - 0R - 1% - 0603")
      (fields (field (name "LCSC PART #") "C21189") (field (name "Comment") "0603WAF0000T5E"))
      (libsource (lib "JLC_PCB") (part "0603WAF0000T5E"))
    )
    (comp (ref "RC_379")
      (value "0R")
      (footprint "R_0603")
      (description "R - RESISTOR - SMD - 0R - 1% - 0603")
      (fields (field (name "LCSC PART #") "C21189") (field (name "Comment") "0603WAF0000T5E"))
      (libsource (lib "JLC_PCB") (part "0603WAF0000T5E"))
    )
    (comp (ref "RC_380")
      (value "0R")
      (footprint "R_0603")
      (description "R - RESISTOR - SMD - 0R - 1% - 0603")
      (fields (field (name "LCSC PART #") "C21189") (field (name "Comment") "0603WAF0000T5E"))
      (libsource (lib "JLC_PCB") (part "0603WAF0000T5E"))
    )
    (comp (ref "RC_381")
      (value "0R")
      (footprint "R_0603")
      (description "R - RESISTOR - SMD - 0R - 1% - 0603")
      (fields (field (name "LCSC PART #") "C21189") (field (name "Comment") "0603WAF0000T5E"))
      (libsource (lib "JLC_PCB") (part "0603WAF0000T5E"))
    )
    (comp (ref "RC_382")
      (value "0R")
      (footprint "R_0603")
      (description "R - RESISTOR - SMD - 0R - 1% - 0603")
      (fields (field (name "LCSC PART #") "C21189") (field (name "Comment") "0603WAF0000T5E"))
      (libsource (lib "JLC_PCB") (part "0603WAF0000T5E"))
    )
    (comp (ref "RC_383")
      (value "0R")
      (footprint "R_0603")
      (description "R - RESISTOR - SMD - 0R - 1% - 0603")
      (fields (field (name "LCSC PART #") "C21189") (field (name "Comment") "0603WAF0000T5E"))
      (libsource (lib "JLC_PCB") (part "0603WAF0000T5E"))
    )
    (comp (ref "RC_384")
      (value "0R")
      (footprint "R_0603")
      (description "R - RESISTOR - SMD - 0R - 1% - 0603")
      (fields (field (name "LCSC PART #") "C21189") (field (name "Comment") "0603WAF0000T5E"))
      (libsource (lib "JLC_PCB") (part "0603WAF0000T5E"))
    )
    (comp (ref "RC_385")
      (value "0R")
      (footprint "R_0603")
      (description "R - RESISTOR - SMD - 0R - 1% - 0603")
      (fields (field (name "LCSC PART #") "C21189") (field (name "Comment") "0603WAF0000T5E"))
      (libsource (lib "JLC_PCB") (part "0603WAF0000T5E"))
    )
    (comp (ref "RC_386")
      (value "0R")
      (footprint "R_0603")
      (description "R - RESISTOR - SMD - 0R - 1% - 0603")
      (fields (field (name "LCSC PART #") "C21189") (field (name "Comment") "0603WAF0000T5E"))
      (libsource (lib "JLC_PCB") (part "0603WAF0000T5E"))
    )
    (comp (ref "RC_387")
      (value "0R")
      (footprint "R_0603")
      (description "R - RESISTOR - SMD - 0R - 1% - 0603")
      (fields (field (name "LCSC PART #") "C21189") (field (name "Comment") "0603WAF0000T5E"))
      (libsource (lib "JLC_PCB") (part "0603WAF0000T5E"))
    )
    (comp (ref "RC_388")
      (value "0R")
      (footprint "R_0603")
      (description "R - RESISTOR - SMD - 0R - 1% - 0603")
      (fields (field (name "LCSC PART #") "C21189") (field (name "Comment") "0603WAF0000T5E"))
      (libsource (lib "JLC_PCB") (part "0603WAF0000T5E"))
    )
    (comp (ref "RC_389")
      (value "0R")
      (footprint "R_0603")
      (description "R - RESISTOR - SMD - 0R - 1% - 0603")
      (fields (field (name "LCSC PART #") "C21189") (field (name "Comment") "0603WAF0000T5E"))
      (libsource (lib "JLC_PCB") (part "0603WAF0000T5E"))
    )
    (comp (ref "RC_390")
      (value "0R")
      (footprint "R_0603")
      (description "R - RESISTOR - SMD - 0R - 1% - 0603")
      (fields (field (name "LCSC PART #") "C21189") (field (name "Comment") "0603WAF0000T5E"))
      (libsource (lib "JLC_PCB") (part "0603WAF0000T5E"))
    )
    (comp (ref "RC_391")
      (value "0R")
      (footprint "R_0603")
      (description "R - RESISTOR - SMD - 0R - 1% - 0603")
      (fields (field (name "LCSC PART #") "C21189") (field (name "Comment") "0603WAF0000T5E"))
      (libsource (lib "JLC_PCB") (part "0603WAF0000T5E"))
    )
    (comp (ref "RC_392")
      (value "0R")
      (footprint "R_0603")
      (description "R - RESISTOR - SMD - 0R - 1% - 0603")
      (fields (field (name "LCSC PART #") "C21189") (field (name "Comment") "0603WAF0000T5E"))
      (libsource (lib "JLC_PCB") (part "0603WAF0000T5E"))
    )
    (comp (ref "RC_393")
      (value "0R")
      (footprint "R_0603")
      (description "R - RESISTOR - SMD - 0R - 1% - 0603")
      (fields (field (name "LCSC PART #") "C21189") (field (name "Comment") "0603WAF0000T5E"))
      (libsource (lib "JLC_PCB") (part "0603WAF0000T5E"))
    )
    (comp (ref "RC_394")
      (value "0R")
      (footprint "R_0603")
      (description "R - RESISTOR - SMD - 0R - 1% - 0603")
      (fields (field (name "LCSC PART #") "C21189") (field (name "Comment") "0603WAF0000T5E"))
      (libsource (lib "JLC_PCB") (part "0603WAF0000T5E"))
    )
    (comp (ref "RC_395")
      (value "0R")
      (footprint "R_0603")
      (description "R - RESISTOR - SMD - 0R - 1% - 0603")
      (fields (field (name "LCSC PART #") "C21189") (field (name "Comment") "0603WAF0000T5E"))
      (libsource (lib "JLC_PCB") (part "0603WAF0000T5E"))
    )
    (comp (ref "RC_396")
      (value "0R")
      (footprint "R_0603")
      (description "R - RESISTOR - SMD - 0R - 1% - 0603")
      (fields (field (name "LCSC PART #") "C21189") (field (name "Comment") "0603WAF0000T5E"))
      (libsource (lib "JLC_PCB") (part "0603WAF0000T5E"))
    )
    (comp (ref "RC_397")
      (value "0R")
      (footprint "R_0603")
      (description "R - RESISTOR - SMD - 0R - 1% - 0603")
      (fields (field (name "LCSC PART #") "C21189") (field (name "Comment") "0603WAF0000T5E"))
      (libsource (lib "JLC_PCB") (part "0603WAF0000T5E"))
    )
    (comp (ref "RC_398")
      (value "0R")
      (footprint "R_0603")
      (description "R - RESISTOR - SMD - 0R - 1% - 0603")
      (fields (field (name "LCSC PART #") "C21189") (field (name "Comment") "0603WAF0000T5E"))
      (libsource (lib "JLC_PCB") (part "0603WAF0000T5E"))
    )
    (comp (ref "RC_399")
      (value "0R")
      (footprint "R_0603")
      (description "R - RESISTOR - SMD - 0R - 1% - 0603")
      (fields (field (name "LCSC PART #") "C21189") (field (name "Comment") "0603WAF0000T5E"))
      (libsource (lib "JLC_PCB") (part "0603WAF0000T5E"))
    )
    (comp (ref "RC_400")
      (value "0R")
      (footprint "R_0603")
      (description "R - RESISTOR - SMD - 0R - 1% - 0603")
      (fields (field (name "LCSC PART #") "C21189") (field (name "Comment") "0603WAF0000T5E"))
      (libsource (lib "JLC_PCB") (part "0603WAF0000T5E"))
    )
    (comp (ref "RC_401")
      (value "0R")
      (footprint "R_0603")
      (description "R - RESISTOR - SMD - 0R - 1% - 0603")
      (fields (field (name "LCSC PART #") "C21189") (field (name "Comment") "0603WAF0000T5E"))
      (libsource (lib "JLC_PCB") (part "0603WAF0000T5E"))
    )
    (comp (ref "RC_402")
      (value "0R")
      (footprint "R_0603")
      (description "R - RESISTOR - SMD - 0R - 1% - 0603")
      (fields (field (name "LCSC PART #") "C21189") (field (name "Comment") "0603WAF0000T5E"))
      (libsource (lib "JLC_PCB") (part "0603WAF0000T5E"))
    )
    (comp (ref "RC_403")
      (value "0R")
      (footprint "R_0603")
      (description "R - RESISTOR - SMD - 0R - 1% - 0603")
      (fields (field (name "LCSC PART #") "C21189") (field (name "Comment") "0603WAF0000T5E"))
      (libsource (lib "JLC_PCB") (part "0603WAF0000T5E"))
    )
    (comp (ref "RC_404")
      (value "0R")
      (footprint "R_0603")
      (description "R - RESISTOR - SMD - 0R - 1% - 0603")
      (fields (field (name "LCSC PART #") "C21189") (field (name "Comment") "0603WAF0000T5E"))
      (libsource (lib "JLC_PCB") (part "0603WAF0000T5E"))
    )
    (comp (ref "RC_405")
      (value "0R")
      (footprint "R_0603")
      (description "R - RESISTOR - SMD - 0R - 1% - 0603")
      (fields (field (name "LCSC PART #") "C21189") (field (name "Comment") "0603WAF0000T5E"))
      (libsource (lib "JLC_PCB") (part "0603WAF0000T5E"))
    )
    (comp (ref "RC_406")
      (value "0R")
      (footprint "R_0603")
      (description "R - RESISTOR - SMD - 0R - 1% - 0603")
      (fields (field (name "LCSC PART #") "C21189") (field (name "Comment") "0603WAF0000T5E"))
      (libsource (lib "JLC_PCB") (part "0603WAF0000T5E"))
    )
    (comp (ref "RC_407")
      (value "0R")
      (footprint "R_0603")
      (description "R - RESISTOR - SMD - 0R - 1% - 0603")
      (fields (field (name "LCSC PART #") "C21189") (field (name "Comment") "0603WAF0000T5E"))
      (libsource (lib "JLC_PCB") (part "0603WAF0000T5E"))
    )
    (comp (ref "RC_408")
      (value "0R")
      (footprint "R_0603")
      (description "R - RESISTOR - SMD - 0R - 1% - 0603")
      (fields (field (name "LCSC PART #") "C21189") (field (name "Comment") "0603WAF0000T5E"))
      (libsource (lib "JLC_PCB") (part "0603WAF0000T5E"))
    )
    (comp (ref "RC_409")
      (value "0R")
      (footprint "R_0603")
      (description "R - RESISTOR - SMD - 0R - 1% - 0603")
      (fields (field (name "LCSC PART #") "C21189") (field (name "Comment") "0603WAF0000T5E"))
      (libsource (lib "JLC_PCB") (part "0603WAF0000T5E"))
    )
    (comp (ref "RC_410")
      (value "0R")
      (footprint "R_0603")
      (description "R - RESISTOR - SMD - 0R - 1% - 0603")
      (fields (field (name "LCSC PART #") "C21189") (field (name "Comment") "0603WAF0000T5E"))
      (libsource (lib "JLC_PCB") (part "0603WAF0000T5E"))
    )
    (comp (ref "RC_411")
      (value "0R")
      (footprint "R_0603")
      (description "R - RESISTOR - SMD - 0R - 1% - 0603")
      (fields (field (name "LCSC PART #") "C21189") (field (name "Comment") "0603WAF0000T5E"))
      (libsource (lib "JLC_PCB") (part "0603WAF0000T5E"))
    )
    (comp (ref "RC_412")
      (value "0R")
      (footprint "R_0603")
      (description "R - RESISTOR - SMD - 0R - 1% - 0603")
      (fields (field (name "LCSC PART #") "C21189") (field (name "Comment") "0603WAF0000T5E"))
      (libsource (lib "JLC_PCB") (part "0603WAF0000T5E"))
    )
    (comp (ref "RC_413")
      (value "0R")
      (footprint "R_0603")
      (description "R - RESISTOR - SMD - 0R - 1% - 0603")
      (fields (field (name "LCSC PART #") "C21189") (field (name "Comment") "0603WAF0000T5E"))
      (libsource (lib "JLC_PCB") (part "0603WAF0000T5E"))
    )
    (comp (ref "RC_414")
      (value "0R")
      (footprint "R_0603")
      (description "R - RESISTOR - SMD - 0R - 1% - 0603")
      (fields (field (name "LCSC PART #") "C21189") (field (name "Comment") "0603WAF0000T5E"))
      (libsource (lib "JLC_PCB") (part "0603WAF0000T5E"))
    )
    (comp (ref "RC_415")
      (value "0R")
      (footprint "R_0603")
      (description "R - RESISTOR - SMD - 0R - 1% - 0603")
      (fields (field (name "LCSC PART #") "C21189") (field (name "Comment") "0603WAF0000T5E"))
      (libsource (lib "JLC_PCB") (part "0603WAF0000T5E"))
    )
    (comp (ref "RC_416")
      (value "0R")
      (footprint "R_0603")
      (description "R - RESISTOR - SMD - 0R - 1% - 0603")
      (fields (field (name "LCSC PART #") "C21189") (field (name "Comment") "0603WAF0000T5E"))
      (libsource (lib "JLC_PCB") (part "0603WAF0000T5E"))
    )
    (comp (ref "RC_417")
      (value "0R")
      (footprint "R_0603")
      (description "R - RESISTOR - SMD - 0R - 1% - 0603")
      (fields (field (name "LCSC PART #") "C21189") (field (name "Comment") "0603WAF0000T5E"))
      (libsource (lib "JLC_PCB") (part "0603WAF0000T5E"))
    )
    (comp (ref "RC_418")
      (value "0R")
      (footprint "R_0603")
      (description "R - RESISTOR - SMD - 0R - 1% - 0603")
      (fields (field (name "LCSC PART #") "C21189") (field (name "Comment") "0603WAF0000T5E"))
      (libsource (lib "JLC_PCB") (part "0603WAF0000T5E"))
    )
    (comp (ref "RC_419")
      (value "0R")
      (footprint "R_0603")
      (description "R - RESISTOR - SMD - 0R - 1% - 0603")
      (fields (field (name "LCSC PART #") "C21189") (field (name "Comment") "0603WAF0000T5E"))
      (libsource (lib "JLC_PCB") (part "0603WAF0000T5E"))
    )
    (comp (ref "RC_420")
      (value "0R")
      (footprint "R_0603")
      (description "R - RESISTOR - SMD - 0R - 1% - 0603")
      (fields (field (name "LCSC PART #") "C21189") (field (name "Comment") "0603WAF0000T5E"))
      (libsource (lib "JLC_PCB") (part "0603WAF0000T5E"))
    )
    (comp (ref "RC_421")
      (value "0R")
      (footprint "R_0603")
      (description "R - RESISTOR - SMD - 0R - 1% - 0603")
      (fields (field (name "LCSC PART #") "C21189") (field (name "Comment") "0603WAF0000T5E"))
      (libsource (lib "JLC_PCB") (part "0603WAF0000T5E"))
    )
    (comp (ref "RC_422")
      (value "0R")
      (footprint "R_0603")
      (description "R - RESISTOR - SMD - 0R - 1% - 0603")
      (fields (field (name "LCSC PART #") "C21189") (field (name "Comment") "0603WAF0000T5E"))
      (libsource (lib "JLC_PCB") (part "0603WAF0000T5E"))
    )
    (comp (ref "RC_423")
      (value "0R")
      (footprint "R_0603")
      (description "R - RESISTOR - SMD - 0R - 1% - 0603")
      (fields (field (name "LCSC PART #") "C21189") (field (name "Comment") "0603WAF0000T5E"))
      (libsource (lib "JLC_PCB") (part "0603WAF0000T5E"))
    )
    (comp (ref "RC_424")
      (value "0R")
      (footprint "R_0603")
      (description "R - RESISTOR - SMD - 0R - 1% - 0603")
      (fields (field (name "LCSC PART #") "C21189") (field (name "Comment") "0603WAF0000T5E"))
      (libsource (lib "JLC_PCB") (part "0603WAF0000T5E"))
    )
    (comp (ref "RC_425")
      (value "0R")
      (footprint "R_0603")
      (description "R - RESISTOR - SMD - 0R - 1% - 0603")
      (fields (field (name "LCSC PART #") "C21189") (field (name "Comment") "0603WAF0000T5E"))
      (libsource (lib "JLC_PCB") (part "0603WAF0000T5E"))
    )
    (comp (ref "RC_426")
      (value "0R")
      (footprint "R_0603")
      (description "R - RESISTOR - SMD - 0R - 1% - 0603")
      (fields (field (name "LCSC PART #") "C21189") (field (name "Comment") "0603WAF0000T5E"))
      (libsource (lib "JLC_PCB") (part "0603WAF0000T5E"))
    )
    (comp (ref "RC_427")
      (value "0R")
      (footprint "R_0603")
      (description "R - RESISTOR - SMD - 0R - 1% - 0603")
      (fields (field (name "LCSC PART #") "C21189") (field (name "Comment") "0603WAF0000T5E"))
      (libsource (lib "JLC_PCB") (part "0603WAF0000T5E"))
    )
    (comp (ref "RC_428")
      (value "0R")
      (footprint "R_0603")
      (description "R - RESISTOR - SMD - 0R - 1% - 0603")
      (fields (field (name "LCSC PART #") "C21189") (field (name "Comment") "0603WAF0000T5E"))
      (libsource (lib "JLC_PCB") (part "0603WAF0000T5E"))
    )
    (comp (ref "RC_429")
      (value "0R")
      (footprint "R_0603")
      (description "R - RESISTOR - SMD - 0R - 1% - 0603")
      (fields (field (name "LCSC PART #") "C21189") (field (name "Comment") "0603WAF0000T5E"))
      (libsource (lib "JLC_PCB") (part "0603WAF0000T5E"))
    )
    (comp (ref "RC_430")
      (value "0R")
      (footprint "R_0603")
      (description "R - RESISTOR - SMD - 0R - 1% - 0603")
      (fields (field (name "LCSC PART #") "C21189") (field (name "Comment") "0603WAF0000T5E"))
      (libsource (lib "JLC_PCB") (part "0603WAF0000T5E"))
    )
    (comp (ref "RC_431")
      (value "0R")
      (footprint "R_0603")
      (description "R - RESISTOR - SMD - 0R - 1% - 0603")
      (fields (field (name "LCSC PART #") "C21189") (field (name "Comment") "0603WAF0000T5E"))
      (libsource (lib "JLC_PCB") (part "0603WAF0000T5E"))
    )
    (comp (ref "TSB_1")
      (value "10k")
      (footprint "R_0402")
      (description "RT - NTC THERMISTOR - 10k - 1% - 0402")
      (fields (field (name "LCSC PART #") "C77131") (field (name "Comment") "NCP15XH103F03RC"))
      (libsource (lib "JLC_PCB") (part "NCP15XH103F03RC"))
    )
    (comp (ref "TSB_1-2")
      (value "10k")
      (footprint "R_0402")
      (description "RT - NTC THERMISTOR - 10k - 1% - 0402")
      (fields (field (name "LCSC PART #") "C77131") (field (name "Comment") "NCP15XH103F03RC"))
      (libsource (lib "JLC_PCB") (part "NCP15XH103F03RC"))
    )
    (comp (ref "TSB_2_3")
      (value "10k")
      (footprint "R_0402")
      (description "RT - NTC THERMISTOR - 10k - 1% - 0402")
      (fields (field (name "LCSC PART #") "C77131") (field (name "Comment") "NCP15XH103F03RC"))
      (libsource (lib "JLC_PCB") (part "NCP15XH103F03RC"))
    )
    (comp (ref "TSB_3-4")
      (value "10k")
      (footprint "R_0402")
      (description "RT - NTC THERMISTOR - 10k - 1% - 0402")
      (fields (field (name "LCSC PART #") "C77131") (field (name "Comment") "NCP15XH103F03RC"))
      (libsource (lib "JLC_PCB") (part "NCP15XH103F03RC"))
    )
    (comp (ref "TSB_4_5")
      (value "10k")
      (footprint "R_0402")
      (description "RT - NTC THERMISTOR - 10k - 1% - 0402")
      (fields (field (name "LCSC PART #") "C77131") (field (name "Comment") "NCP15XH103F03RC"))
      (libsource (lib "JLC_PCB") (part "NCP15XH103F03RC"))
    )
    (comp (ref "TSB_5-6")
      (value "10k")
      (footprint "R_0402")
      (description "RT - NTC THERMISTOR - 10k - 1% - 0402")
      (fields (field (name "LCSC PART #") "C77131") (field (name "Comment") "NCP15XH103F03RC"))
      (libsource (lib "JLC_PCB") (part "NCP15XH103F03RC"))
    )
    (comp (ref "TSB_6_7")
      (value "10k")
      (footprint "R_0402")
      (description "RT - NTC THERMISTOR - 10k - 1% - 0402")
      (fields (field (name "LCSC PART #") "C77131") (field (name "Comment") "NCP15XH103F03RC"))
      (libsource (lib "JLC_PCB") (part "NCP15XH103F03RC"))
    )
    (comp (ref "TSB_7-8")
      (value "10k")
      (footprint "R_0402")
      (description "RT - NTC THERMISTOR - 10k - 1% - 0402")
      (fields (field (name "LCSC PART #") "C77131") (field (name "Comment") "NCP15XH103F03RC"))
      (libsource (lib "JLC_PCB") (part "NCP15XH103F03RC"))
    )
    (comp (ref "TSB_8_9")
      (value "10k")
      (footprint "R_0402")
      (description "RT - NTC THERMISTOR - 10k - 1% - 0402")
      (fields (field (name "LCSC PART #") "C77131") (field (name "Comment") "NCP15XH103F03RC"))
      (libsource (lib "JLC_PCB") (part "NCP15XH103F03RC"))
    )
    (comp (ref "TSB_9-10")
      (value "10k")
      (footprint "R_0402")
      (description "RT - NTC THERMISTOR - 10k - 1% - 0402")
      (fields (field (name "LCSC PART #") "C77131") (field (name "Comment") "NCP15XH103F03RC"))
      (libsource (lib "JLC_PCB") (part "NCP15XH103F03RC"))
    )
    (comp (ref "TSB_10_11")
      (value "10k")
      (footprint "R_0402")
      (description "RT - NTC THERMISTOR - 10k - 1% - 0402")
      (fields (field (name "LCSC PART #") "C77131") (field (name "Comment") "NCP15XH103F03RC"))
      (libsource (lib "JLC_PCB") (part "NCP15XH103F03RC"))
    )
    (comp (ref "TSB_11-12")
      (value "10k")
      (footprint "R_0402")
      (description "RT - NTC THERMISTOR - 10k - 1% - 0402")
      (fields (field (name "LCSC PART #") "C77131") (field (name "Comment") "NCP15XH103F03RC"))
      (libsource (lib "JLC_PCB") (part "NCP15XH103F03RC"))
    )
    (comp (ref "TSB_12")
      (value "10k")
      (footprint "R_0402")
      (description "RT - NTC THERMISTOR - 10k - 1% - 0402")
      (fields (field (name "LCSC PART #") "C77131") (field (name "Comment") "NCP15XH103F03RC"))
      (libsource (lib "JLC_PCB") (part "NCP15XH103F03RC"))
    )
  )
  (nets
    (net (code "1") (name "/BATT_1") (class "Default")
      (node (ref "JB1") (pin "1") (pinfunction "1_1") (pintype "passive"))
      (node (ref "JB1") (pin "2") (pinfunction "2_2") (pintype "passive"))
      (node (ref "JB1") (pin "3") (pinfunction "3_3") (pintype "passive"))
      (node (ref "JB1") (pin "4") (pinfunction "4_4") (pintype "passive"))
      (node (ref "JB13") (pin "4") (pinfunction "4_4") (pintype "passive"))
      (node (ref "JB2") (pin "1") (pinfunction "1_1") (pintype "passive"))
      (node (ref "JB2") (pin "2") (pinfunction "2_2") (pintype "passive"))
      (node (ref "JB2") (pin "3") (pinfunction "3_3") (pintype "passive"))
      (node (ref "JB2") (pin "4") (pinfunction "4_4") (pintype "passive"))
      (node (ref "JB3") (pin "1") (pinfunction "1_1") (pintype "passive"))
      (node (ref "JB3") (pin "2") (pinfunction "2_2") (pintype "passive"))
      (node (ref "JB3") (pin "3") (pinfunction "3_3") (pintype "passive"))
      (node (ref "JB3") (pin "4") (pinfunction "4_4") (pintype "passive"))
      (node (ref "JB7") (pin "1") (pinfunction "1_1") (pintype "passive"))
      (node (ref "RC_0") (pin "1") (pinfunction "1_1") (pintype "passive"))
      (node (ref "RC_0") (pin "2") (pinfunction "2_2") (pintype "passive"))
      (node (ref "RC_1") (pin "1") (pinfunction "1_1") (pintype "passive"))
      (node (ref "RC_1") (pin "2") (pinfunction "2_2") (pintype "passive"))
      (node (ref "RC_10") (pin "1") (pinfunction "1_1") (pintype "passive"))
      (node (ref "RC_10") (pin "2") (pinfunction "2_2") (pintype "passive"))
      (node (ref "RC_11") (pin "1") (pinfunction "1_1") (pintype "passive"))
      (node (ref "RC_11") (pin "2") (pinfunction "2_2") (pintype "passive"))
      (node (ref "RC_12") (pin "1") (pinfunction "1_1") (pintype "passive"))
      (node (ref "RC_12") (pin "2") (pinfunction "2_2") (pintype "passive"))
      (node (ref "RC_13") (pin "1") (pinfunction "1_1") (pintype "passive"))
      (node (ref "RC_13") (pin "2") (pinfunction "2_2") (pintype "passive"))
      (node (ref "RC_14") (pin "1") (pinfunction "1_1") (pintype "passive"))
      (node (ref "RC_14") (pin "2") (pinfunction "2_2") (pintype "passive"))
      (node (ref "RC_15") (pin "1") (pinfunction "1_1") (pintype "passive"))
      (node (ref "RC_15") (pin "2") (pinfunction "2_2") (pintype "passive"))
      (node (ref "RC_16") (pin "1") (pinfunction "1_1") (pintype "passive"))
      (node (ref "RC_16") (pin "2") (pinfunction "2_2") (pintype "passive"))
      (node (ref "RC_17") (pin "1") (pinfunction "1_1") (pintype "passive"))
      (node (ref "RC_17") (pin "2") (pinfunction "2_2") (pintype "passive"))
      (node (ref "RC_2") (pin "1") (pinfunction "1_1") (pintype "passive"))
      (node (ref "RC_2") (pin "2") (pinfunction "2_2") (pintype "passive"))
      (node (ref "RC_3") (pin "1") (pinfunction "1_1") (pintype "passive"))
      (node (ref "RC_3") (pin "2") (pinfunction "2_2") (pintype "passive"))
      (node (ref "RC_4") (pin "1") (pinfunction "1_1") (pintype "passive"))
      (node (ref "RC_4") (pin "2") (pinfunction "2_2") (pintype "passive"))
      (node (ref "RC_5") (pin "1") (pinfunction "1_1") (pintype "passive"))
      (node (ref "RC_5") (pin "2") (pinfunction "2_2") (pintype "passive"))
      (node (ref "RC_6") (pin "1") (pinfunction "1_1") (pintype "passive"))
      (node (ref "RC_6") (pin "2") (pinfunction "2_2") (pintype "passive"))
      (node (ref "RC_7") (pin "1") (pinfunction "1_1") (pintype "passive"))
      (node (ref "RC_7") (pin "2") (pinfunction "2_2") (pintype "passive"))
      (node (ref "RC_8") (pin "1") (pinfunction "1_1") (pintype "passive"))
      (node (ref "RC_8") (pin "2") (pinfunction "2_2") (pintype "passive"))
      (node (ref "RC_9") (pin "1") (pinfunction "1_1") (pintype "passive"))
      (node (ref "RC_9") (pin "2") (pinfunction "2_2") (pintype "passive"))
    )
    (net (code "2") (name "/BATT_1-2") (class "Default")
      (node (ref "JB13") (pin "3") (pinfunction "3_3") (pintype "passive"))
      (node (ref "JB7") (pin "2") (pinfunction "2_2") (pintype "passive"))
      (node (ref "RC_18") (pin "1") (pinfunction "1_1") (pintype "passive"))
      (node (ref "RC_18") (pin "2") (pinfunction "2_2") (pintype "passive"))
      (node (ref "RC_19") (pin "1") (pinfunction "1_1") (pintype "passive"))
      (node (ref "RC_19") (pin "2") (pinfunction "2_2") (pintype "passive"))
      (node (ref "RC_20") (pin "1") (pinfunction "1_1") (pintype "passive"))
      (node (ref "RC_20") (pin "2") (pinfunction "2_2") (pintype "passive"))
      (node (ref "RC_21") (pin "1") (pinfunction "1_1") (pintype "passive"))
      (node (ref "RC_21") (pin "2") (pinfunction "2_2") (pintype "passive"))
      (node (ref "RC_22") (pin "1") (pinfunction "1_1") (pintype "passive"))
      (node (ref "RC_22") (pin "2") (pinfunction "2_2") (pintype "passive"))
      (node (ref "RC_23") (pin "1") (pinfunction "1_1") (pintype "passive"))
      (node (ref "RC_23") (pin "2") (pinfunction "2_2") (pintype "passive"))
      (node (ref "RC_24") (pin "1") (pinfunction "1_1") (pintype "passive"))
      (node (ref "RC_24") (pin "2") (pinfunction "2_2") (pintype "passive"))
      (node (ref "RC_25") (pin "1") (pinfunction "1_1") (pintype "passive"))
      (node (ref "RC_25") (pin "2") (pinfunction "2_2") (pintype "passive"))
      (node (ref "RC_26") (pin "1") (pinfunction "1_1") (pintype "passive"))
      (node (ref "RC_26") (pin "2") (pinfunction "2_2") (pintype "passive"))
      (node (ref "RC_27") (pin "1") (pinfunction "1_1") (pintype "passive"))
      (node (ref "RC_27") (pin "2") (pinfunction "2_2") (pintype "passive"))
      (node (ref "RC_28") (pin "1") (pinfunction "1_1") (pintype "passive"))
      (node (ref "RC_28") (pin "2") (pinfunction "2_2") (pintype "passive"))
      (node (ref "RC_29") (pin "1") (pinfunction "1_1") (pintype "passive"))
      (node (ref "RC_29") (pin "2") (pinfunction "2_2") (pintype "passive"))
      (node (ref "RC_30") (pin "1") (pinfunction "1_1") (pintype "passive"))
      (node (ref "RC_30") (pin "2") (pinfunction "2_2") (pintype "passive"))
      (node (ref "RC_31") (pin "1") (pinfunction "1_1") (pintype "passive"))
      (node (ref "RC_31") (pin "2") (pinfunction "2_2") (pintype "passive"))
      (node (ref "RC_32") (pin "1") (pinfunction "1_1") (pintype "passive"))
      (node (ref "RC_32") (pin "2") (pinfunction "2_2") (pintype "passive"))
      (node (ref "RC_33") (pin "1") (pinfunction "1_1") (pintype "passive"))
      (node (ref "RC_33") (pin "2") (pinfunction "2_2") (pintype "passive"))
      (node (ref "RC_34") (pin "1") (pinfunction "1_1") (pintype "passive"))
      (node (ref "RC_34") (pin "2") (pinfunction "2_2") (pintype "passive"))
      (node (ref "RC_35") (pin "1") (pinfunction "1_1") (pintype "passive"))
      (node (ref "RC_35") (pin "2") (pinfunction "2_2") (pintype "passive"))
      (node (ref "RC_36") (pin "1") (pinfunction "1_1") (pintype "passive"))
      (node (ref "RC_36") (pin "2") (pinfunction "2_2") (pintype "passive"))
      (node (ref "RC_37") (pin "1") (pinfunction "1_1") (pintype "passive"))
      (node (ref "RC_37") (pin "2") (pinfunction "2_2") (pintype "passive"))
      (node (ref "RC_38") (pin "1") (pinfunction "1_1") (pintype "passive"))
      (node (ref "RC_38") (pin "2") (pinfunction "2_2") (pintype "passive"))
      (node (ref "RC_39") (pin "1") (pinfunction "1_1") (pintype "passive"))
      (node (ref "RC_39") (pin "2") (pinfunction "2_2") (pintype "passive"))
      (node (ref "RC_40") (pin "1") (pinfunction "1_1") (pintype "passive"))
      (node (ref "RC_40") (pin "2") (pinfunction "2_2") (pintype "passive"))
      (node (ref "RC_41") (pin "1") (pinfunction "1_1") (pintype "passive"))
      (node (ref "RC_41") (pin "2") (pinfunction "2_2") (pintype "passive"))
      (node (ref "RC_42") (pin "1") (pinfunction "1_1") (pintype "passive"))
      (node (ref "RC_42") (pin "2") (pinfunction "2_2") (pintype "passive"))
      (node (ref "RC_43") (pin "1") (pinfunction "1_1") (pintype "passive"))
      (node (ref "RC_43") (pin "2") (pinfunction "2_2") (pintype "passive"))
      (node (ref "RC_44") (pin "1") (pinfunction "1_1") (pintype "passive"))
      (node (ref "RC_44") (pin "2") (pinfunction "2_2") (pintype "passive"))
      (node (ref "RC_45") (pin "1") (pinfunction "1_1") (pintype "passive"))
      (node (ref "RC_45") (pin "2") (pinfunction "2_2") (pintype "passive"))
      (node (ref "RC_46") (pin "1") (pinfunction "1_1") (pintype "passive"))
      (node (ref "RC_46") (pin "2") (pinfunction "2_2") (pintype "passive"))
      (node (ref "RC_47") (pin "1") (pinfunction "1_1") (pintype "passive"))
      (node (ref "RC_47") (pin "2") (pinfunction "2_2") (pintype "passive"))
      (node (ref "RC_48") (pin "1") (pinfunction "1_1") (pintype "passive"))
      (node (ref "RC_48") (pin "2") (pinfunction "2_2") (pintype "passive"))
      (node (ref "RC_49") (pin "1") (pinfunction "1_1") (pintype "passive"))
      (node (ref "RC_49") (pin "2") (pinfunction "2_2") (pintype "passive"))
      (node (ref "RC_50") (pin "1") (pinfunction "1_1") (pintype "passive"))
      (node (ref "RC_50") (pin "2") (pinfunction "2_2") (pintype "passive"))
      (node (ref "RC_51") (pin "1") (pinfunction "1_1") (pintype "passive"))
      (node (ref "RC_51") (pin "2") (pinfunction "2_2") (pintype "passive"))
      (node (ref "RC_52") (pin "1") (pinfunction "1_1") (pintype "passive"))
      (node (ref "RC_52") (pin "2") (pinfunction "2_2") (pintype "passive"))
      (node (ref "RC_53") (pin "1") (pinfunction "1_1") (pintype "passive"))
      (node (ref "RC_53") (pin "2") (pinfunction "2_2") (pintype "passive"))
    )
    (net (code "3") (name "/BATT_2-3") (class "Default")
      (node (ref "JB13") (pin "2") (pinfunction "2_2") (pintype "passive"))
      (node (ref "JB7") (pin "3") (pinfunction "3_3") (pintype "passive"))
      (node (ref "RC_54") (pin "1") (pinfunction "1_1") (pintype "passive"))
      (node (ref "RC_54") (pin "2") (pinfunction "2_2") (pintype "passive"))
      (node (ref "RC_55") (pin "1") (pinfunction "1_1") (pintype "passive"))
      (node (ref "RC_55") (pin "2") (pinfunction "2_2") (pintype "passive"))
      (node (ref "RC_56") (pin "1") (pinfunction "1_1") (pintype "passive"))
      (node (ref "RC_56") (pin "2") (pinfunction "2_2") (pintype "passive"))
      (node (ref "RC_57") (pin "1") (pinfunction "1_1") (pintype "passive"))
      (node (ref "RC_57") (pin "2") (pinfunction "2_2") (pintype "passive"))
      (node (ref "RC_58") (pin "1") (pinfunction "1_1") (pintype "passive"))
      (node (ref "RC_58") (pin "2") (pinfunction "2_2") (pintype "passive"))
      (node (ref "RC_59") (pin "1") (pinfunction "1_1") (pintype "passive"))
      (node (ref "RC_59") (pin "2") (pinfunction "2_2") (pintype "passive"))
      (node (ref "RC_60") (pin "1") (pinfunction "1_1") (pintype "passive"))
      (node (ref "RC_60") (pin "2") (pinfunction "2_2") (pintype "passive"))
      (node (ref "RC_61") (pin "1") (pinfunction "1_1") (pintype "passive"))
      (node (ref "RC_61") (pin "2") (pinfunction "2_2") (pintype "passive"))
      (node (ref "RC_62") (pin "1") (pinfunction "1_1") (pintype "passive"))
      (node (ref "RC_62") (pin "2") (pinfunction "2_2") (pintype "passive"))
      (node (ref "RC_63") (pin "1") (pinfunction "1_1") (pintype "passive"))
      (node (ref "RC_63") (pin "2") (pinfunction "2_2") (pintype "passive"))
      (node (ref "RC_64") (pin "1") (pinfunction "1_1") (pintype "passive"))
      (node (ref "RC_64") (pin "2") (pinfunction "2_2") (pintype "passive"))
      (node (ref "RC_65") (pin "1") (pinfunction "1_1") (pintype "passive"))
      (node (ref "RC_65") (pin "2") (pinfunction "2_2") (pintype "passive"))
      (node (ref "RC_66") (pin "1") (pinfunction "1_1") (pintype "passive"))
      (node (ref "RC_66") (pin "2") (pinfunction "2_2") (pintype "passive"))
      (node (ref "RC_67") (pin "1") (pinfunction "1_1") (pintype "passive"))
      (node (ref "RC_67") (pin "2") (pinfunction "2_2") (pintype "passive"))
      (node (ref "RC_68") (pin "1") (pinfunction "1_1") (pintype "passive"))
      (node (ref "RC_68") (pin "2") (pinfunction "2_2") (pintype "passive"))
      (node (ref "RC_69") (pin "1") (pinfunction "1_1") (pintype "passive"))
      (node (ref "RC_69") (pin "2") (pinfunction "2_2") (pintype "passive"))
      (node (ref "RC_70") (pin "1") (pinfunction "1_1") (pintype "passive"))
      (node (ref "RC_70") (pin "2") (pinfunction "2_2") (pintype "passive"))
      (node (ref "RC_71") (pin "1") (pinfunction "1_1") (pintype "passive"))
      (node (ref "RC_71") (pin "2") (pinfunction "2_2") (pintype "passive"))
      (node (ref "RC_72") (pin "1") (pinfunction "1_1") (pintype "passive"))
      (node (ref "RC_72") (pin "2") (pinfunction "2_2") (pintype "passive"))
      (node (ref "RC_73") (pin "1") (pinfunction "1_1") (pintype "passive"))
      (node (ref "RC_73") (pin "2") (pinfunction "2_2") (pintype "passive"))
      (node (ref "RC_74") (pin "1") (pinfunction "1_1") (pintype "passive"))
      (node (ref "RC_74") (pin "2") (pinfunction "2_2") (pintype "passive"))
      (node (ref "RC_75") (pin "1") (pinfunction "1_1") (pintype "passive"))
      (node (ref "RC_75") (pin "2") (pinfunction "2_2") (pintype "passive"))
      (node (ref "RC_76") (pin "1") (pinfunction "1_1") (pintype "passive"))
      (node (ref "RC_76") (pin "2") (pinfunction "2_2") (pintype "passive"))
      (node (ref "RC_77") (pin "1") (pinfunction "1_1") (pintype "passive"))
      (node (ref "RC_77") (pin "2") (pinfunction "2_2") (pintype "passive"))
      (node (ref "RC_78") (pin "1") (pinfunction "1_1") (pintype "passive"))
      (node (ref "RC_78") (pin "2") (pinfunction "2_2") (pintype "passive"))
      (node (ref "RC_79") (pin "1") (pinfunction "1_1") (pintype "passive"))
      (node (ref "RC_79") (pin "2") (pinfunction "2_2") (pintype "passive"))
      (node (ref "RC_80") (pin "1") (pinfunction "1_1") (pintype "passive"))
      (node (ref "RC_80") (pin "2") (pinfunction "2_2") (pintype "passive"))
      (node (ref "RC_81") (pin "1") (pinfunction "1_1") (pintype "passive"))
      (node (ref "RC_81") (pin "2") (pinfunction "2_2") (pintype "passive"))
      (node (ref "RC_82") (pin "1") (pinfunction "1_1") (pintype "passive"))
      (node (ref "RC_82") (pin "2") (pinfunction "2_2") (pintype "passive"))
      (node (ref "RC_83") (pin "1") (pinfunction "1_1") (pintype "passive"))
      (node (ref "RC_83") (pin "2") (pinfunction "2_2") (pintype "passive"))
      (node (ref "RC_84") (pin "1") (pinfunction "1_1") (pintype "passive"))
      (node (ref "RC_84") (pin "2") (pinfunction "2_2") (pintype "passive"))
      (node (ref "RC_85") (pin "1") (pinfunction "1_1") (pintype "passive"))
      (node (ref "RC_85") (pin "2") (pinfunction "2_2") (pintype "passive"))
      (node (ref "RC_86") (pin "1") (pinfunction "1_1") (pintype "passive"))
      (node (ref "RC_86") (pin "2") (pinfunction "2_2") (pintype "passive"))
      (node (ref "RC_87") (pin "1") (pinfunction "1_1") (pintype "passive"))
      (node (ref "RC_87") (pin "2") (pinfunction "2_2") (pintype "passive"))
      (node (ref "RC_88") (pin "1") (pinfunction "1_1") (pintype "passive"))
      (node (ref "RC_88") (pin "2") (pinfunction "2_2") (pintype "passive"))
      (node (ref "RC_89") (pin "1") (pinfunction "1_1") (pintype "passive"))
      (node (ref "RC_89") (pin "2") (pinfunction "2_2") (pintype "passive"))
    )
    (net (code "4") (name "/BATT_3-4") (class "Default")
      (node (ref "JB13") (pin "1") (pinfunction "1_1") (pintype "passive"))
      (node (ref "JB7") (pin "4") (pinfunction "4_4") (pintype "passive"))
      (node (ref "NT_3_4") (pin "2") (pinfunction "2_2") (pintype "passive"))
      (node (ref "RC_100") (pin "1") (pinfunction "1_1") (pintype "passive"))
      (node (ref "RC_100") (pin "2") (pinfunction "2_2") (pintype "passive"))
      (node (ref "RC_101") (pin "1") (pinfunction "1_1") (pintype "passive"))
      (node (ref "RC_101") (pin "2") (pinfunction "2_2") (pintype "passive"))
      (node (ref "RC_102") (pin "1") (pinfunction "1_1") (pintype "passive"))
      (node (ref "RC_102") (pin "2") (pinfunction "2_2") (pintype "passive"))
      (node (ref "RC_103") (pin "1") (pinfunction "1_1") (pintype "passive"))
      (node (ref "RC_103") (pin "2") (pinfunction "2_2") (pintype "passive"))
      (node (ref "RC_104") (pin "1") (pinfunction "1_1") (pintype "passive"))
      (node (ref "RC_104") (pin "2") (pinfunction "2_2") (pintype "passive"))
      (node (ref "RC_105") (pin "1") (pinfunction "1_1") (pintype "passive"))
      (node (ref "RC_105") (pin "2") (pinfunction "2_2") (pintype "passive"))
      (node (ref "RC_106") (pin "1") (pinfunction "1_1") (pintype "passive"))
      (node (ref "RC_106") (pin "2") (pinfunction "2_2") (pintype "passive"))
      (node (ref "RC_107") (pin "1") (pinfunction "1_1") (pintype "passive"))
      (node (ref "RC_107") (pin "2") (pinfunction "2_2") (pintype "passive"))
      (node (ref "RC_108") (pin "1") (pinfunction "1_1") (pintype "passive"))
      (node (ref "RC_108") (pin "2") (pinfunction "2_2") (pintype "passive"))
      (node (ref "RC_109") (pin "1") (pinfunction "1_1") (pintype "passive"))
      (node (ref "RC_109") (pin "2") (pinfunction "2_2") (pintype "passive"))
      (node (ref "RC_110") (pin "1") (pinfunction "1_1") (pintype "passive"))
      (node (ref "RC_110") (pin "2") (pinfunction "2_2") (pintype "passive"))
      (node (ref "RC_111") (pin "1") (pinfunction "1_1") (pintype "passive"))
      (node (ref "RC_111") (pin "2") (pinfunction "2_2") (pintype "passive"))
      (node (ref "RC_112") (pin "1") (pinfunction "1_1") (pintype "passive"))
      (node (ref "RC_112") (pin "2") (pinfunction "2_2") (pintype "passive"))
      (node (ref "RC_113") (pin "1") (pinfunction "1_1") (pintype "passive"))
      (node (ref "RC_113") (pin "2") (pinfunction "2_2") (pintype "passive"))
      (node (ref "RC_114") (pin "1") (pinfunction "1_1") (pintype "passive"))
      (node (ref "RC_114") (pin "2") (pinfunction "2_2") (pintype "passive"))
      (node (ref "RC_115") (pin "1") (pinfunction "1_1") (pintype "passive"))
      (node (ref "RC_115") (pin "2") (pinfunction "2_2") (pintype "passive"))
      (node (ref "RC_116") (pin "1") (pinfunction "1_1") (pintype "passive"))
      (node (ref "RC_116") (pin "2") (pinfunction "2_2") (pintype "passive"))
      (node (ref "RC_117") (pin "1") (pinfunction "1_1") (pintype "passive"))
      (node (ref "RC_117") (pin "2") (pinfunction "2_2") (pintype "passive"))
      (node (ref "RC_118") (pin "1") (pinfunction "1_1") (pintype "passive"))
      (node (ref "RC_118") (pin "2") (pinfunction "2_2") (pintype "passive"))
      (node (ref "RC_119") (pin "1") (pinfunction "1_1") (pintype "passive"))
      (node (ref "RC_119") (pin "2") (pinfunction "2_2") (pintype "passive"))
      (node (ref "RC_120") (pin "1") (pinfunction "1_1") (pintype "passive"))
      (node (ref "RC_120") (pin "2") (pinfunction "2_2") (pintype "passive"))
      (node (ref "RC_121") (pin "1") (pinfunction "1_1") (pintype "passive"))
      (node (ref "RC_121") (pin "2") (pinfunction "2_2") (pintype "passive"))
      (node (ref "RC_122") (pin "1") (pinfunction "1_1") (pintype "passive"))
      (node (ref "RC_122") (pin "2") (pinfunction "2_2") (pintype "passive"))
      (node (ref "RC_123") (pin "1") (pinfunction "1_1") (pintype "passive"))
      (node (ref "RC_123") (pin "2") (pinfunction "2_2") (pintype "passive"))
      (node (ref "RC_124") (pin "1") (pinfunction "1_1") (pintype "passive"))
      (node (ref "RC_124") (pin "2") (pinfunction "2_2") (pintype "passive"))
      (node (ref "RC_125") (pin "1") (pinfunction "1_1") (pintype "passive"))
      (node (ref "RC_125") (pin "2") (pinfunction "2_2") (pintype "passive"))
      (node (ref "RC_90") (pin "1") (pinfunction "1_1") (pintype "passive"))
      (node (ref "RC_90") (pin "2") (pinfunction "2_2") (pintype "passive"))
      (node (ref "RC_91") (pin "1") (pinfunction "1_1") (pintype "passive"))
      (node (ref "RC_91") (pin "2") (pinfunction "2_2") (pintype "passive"))
      (node (ref "RC_92") (pin "1") (pinfunction "1_1") (pintype "passive"))
      (node (ref "RC_92") (pin "2") (pinfunction "2_2") (pintype "passive"))
      (node (ref "RC_93") (pin "1") (pinfunction "1_1") (pintype "passive"))
      (node (ref "RC_93") (pin "2") (pinfunction "2_2") (pintype "passive"))
      (node (ref "RC_94") (pin "1") (pinfunction "1_1") (pintype "passive"))
      (node (ref "RC_94") (pin "2") (pinfunction "2_2") (pintype "passive"))
      (node (ref "RC_95") (pin "1") (pinfunction "1_1") (pintype "passive"))
      (node (ref "RC_95") (pin "2") (pinfunction "2_2") (pintype "passive"))
      (node (ref "RC_96") (pin "1") (pinfunction "1_1") (pintype "passive"))
      (node (ref "RC_96") (pin "2") (pinfunction "2_2") (pintype "passive"))
      (node (ref "RC_97") (pin "1") (pinfunction "1_1") (pintype "passive"))
      (node (ref "RC_97") (pin "2") (pinfunction "2_2") (pintype "passive"))
      (node (ref "RC_98") (pin "1") (pinfunction "1_1") (pintype "passive"))
      (node (ref "RC_98") (pin "2") (pinfunction "2_2") (pintype "passive"))
      (node (ref "RC_99") (pin "1") (pinfunction "1_1") (pintype "passive"))
      (node (ref "RC_99") (pin "2") (pinfunction "2_2") (pintype "passive"))
    )
    (net (code "5") (name "/BATT_4-5") (class "Default")
      (node (ref "JB14") (pin "3") (pinfunction "3_3") (pintype "passive"))
      (node (ref "JB8") (pin "2") (pinfunction "2_2") (pintype "passive"))
      (node (ref "RC_126") (pin "1") (pinfunction "1_1") (pintype "passive"))
      (node (ref "RC_126") (pin "2") (pinfunction "2_2") (pintype "passive"))
      (node (ref "RC_127") (pin "1") (pinfunction "1_1") (pintype "passive"))
      (node (ref "RC_127") (pin "2") (pinfunction "2_2") (pintype "passive"))
      (node (ref "RC_128") (pin "1") (pinfunction "1_1") (pintype "passive"))
      (node (ref "RC_128") (pin "2") (pinfunction "2_2") (pintype "passive"))
      (node (ref "RC_129") (pin "1") (pinfunction "1_1") (pintype "passive"))
      (node (ref "RC_129") (pin "2") (pinfunction "2_2") (pintype "passive"))
      (node (ref "RC_130") (pin "1") (pinfunction "1_1") (pintype "passive"))
      (node (ref "RC_130") (pin "2") (pinfunction "2_2") (pintype "passive"))
      (node (ref "RC_131") (pin "1") (pinfunction "1_1") (pintype "passive"))
      (node (ref "RC_131") (pin "2") (pinfunction "2_2") (pintype "passive"))
      (node (ref "RC_132") (pin "1") (pinfunction "1_1") (pintype "passive"))
      (node (ref "RC_132") (pin "2") (pinfunction "2_2") (pintype "passive"))
      (node (ref "RC_133") (pin "1") (pinfunction "1_1") (pintype "passive"))
      (node (ref "RC_133") (pin "2") (pinfunction "2_2") (pintype "passive"))
      (node (ref "RC_134") (pin "1") (pinfunction "1_1") (pintype "passive"))
      (node (ref "RC_134") (pin "2") (pinfunction "2_2") (pintype "passive"))
      (node (ref "RC_135") (pin "1") (pinfunction "1_1") (pintype "passive"))
      (node (ref "RC_135") (pin "2") (pinfunction "2_2") (pintype "passive"))
      (node (ref "RC_136") (pin "1") (pinfunction "1_1") (pintype "passive"))
      (node (ref "RC_136") (pin "2") (pinfunction "2_2") (pintype "passive"))
      (node (ref "RC_137") (pin "1") (pinfunction "1_1") (pintype "passive"))
      (node (ref "RC_137") (pin "2") (pinfunction "2_2") (pintype "passive"))
      (node (ref "RC_138") (pin "1") (pinfunction "1_1") (pintype "passive"))
      (node (ref "RC_138") (pin "2") (pinfunction "2_2") (pintype "passive"))
      (node (ref "RC_139") (pin "1") (pinfunction "1_1") (pintype "passive"))
      (node (ref "RC_139") (pin "2") (pinfunction "2_2") (pintype "passive"))
      (node (ref "RC_140") (pin "1") (pinfunction "1_1") (pintype "passive"))
      (node (ref "RC_140") (pin "2") (pinfunction "2_2") (pintype "passive"))
      (node (ref "RC_141") (pin "1") (pinfunction "1_1") (pintype "passive"))
      (node (ref "RC_141") (pin "2") (pinfunction "2_2") (pintype "passive"))
      (node (ref "RC_142") (pin "1") (pinfunction "1_1") (pintype "passive"))
      (node (ref "RC_142") (pin "2") (pinfunction "2_2") (pintype "passive"))
      (node (ref "RC_143") (pin "1") (pinfunction "1_1") (pintype "passive"))
      (node (ref "RC_143") (pin "2") (pinfunction "2_2") (pintype "passive"))
      (node (ref "RC_144") (pin "1") (pinfunction "1_1") (pintype "passive"))
      (node (ref "RC_144") (pin "2") (pinfunction "2_2") (pintype "passive"))
      (node (ref "RC_145") (pin "1") (pinfunction "1_1") (pintype "passive"))
      (node (ref "RC_145") (pin "2") (pinfunction "2_2") (pintype "passive"))
      (node (ref "RC_146") (pin "1") (pinfunction "1_1") (pintype "passive"))
      (node (ref "RC_146") (pin "2") (pinfunction "2_2") (pintype "passive"))
      (node (ref "RC_147") (pin "1") (pinfunction "1_1") (pintype "passive"))
      (node (ref "RC_147") (pin "2") (pinfunction "2_2") (pintype "passive"))
      (node (ref "RC_148") (pin "1") (pinfunction "1_1") (pintype "passive"))
      (node (ref "RC_148") (pin "2") (pinfunction "2_2") (pintype "passive"))
      (node (ref "RC_149") (pin "1") (pinfunction "1_1") (pintype "passive"))
      (node (ref "RC_149") (pin "2") (pinfunction "2_2") (pintype "passive"))
      (node (ref "RC_150") (pin "1") (pinfunction "1_1") (pintype "passive"))
      (node (ref "RC_150") (pin "2") (pinfunction "2_2") (pintype "passive"))
      (node (ref "RC_151") (pin "1") (pinfunction "1_1") (pintype "passive"))
      (node (ref "RC_151") (pin "2") (pinfunction "2_2") (pintype "passive"))
      (node (ref "RC_152") (pin "1") (pinfunction "1_1") (pintype "passive"))
      (node (ref "RC_152") (pin "2") (pinfunction "2_2") (pintype "passive"))
      (node (ref "RC_153") (pin "1") (pinfunction "1_1") (pintype "passive"))
      (node (ref "RC_153") (pin "2") (pinfunction "2_2") (pintype "passive"))
      (node (ref "RC_154") (pin "1") (pinfunction "1_1") (pintype "passive"))
      (node (ref "RC_154") (pin "2") (pinfunction "2_2") (pintype "passive"))
      (node (ref "RC_155") (pin "1") (pinfunction "1_1") (pintype "passive"))
      (node (ref "RC_155") (pin "2") (pinfunction "2_2") (pintype "passive"))
      (node (ref "RC_156") (pin "1") (pinfunction "1_1") (pintype "passive"))
      (node (ref "RC_156") (pin "2") (pinfunction "2_2") (pintype "passive"))
      (node (ref "RC_157") (pin "1") (pinfunction "1_1") (pintype "passive"))
      (node (ref "RC_157") (pin "2") (pinfunction "2_2") (pintype "passive"))
      (node (ref "RC_158") (pin "1") (pinfunction "1_1") (pintype "passive"))
      (node (ref "RC_158") (pin "2") (pinfunction "2_2") (pintype "passive"))
      (node (ref "RC_159") (pin "1") (pinfunction "1_1") (pintype "passive"))
      (node (ref "RC_159") (pin "2") (pinfunction "2_2") (pintype "passive"))
      (node (ref "RC_160") (pin "1") (pinfunction "1_1") (pintype "passive"))
      (node (ref "RC_160") (pin "2") (pinfunction "2_2") (pintype "passive"))
      (node (ref "RC_161") (pin "1") (pinfunction "1_1") (pintype "passive"))
      (node (ref "RC_161") (pin "2") (pinfunction "2_2") (pintype "passive"))
    )
    (net (code "6") (name "/BATT_5-6") (class "Default")
      (node (ref "JB14") (pin "2") (pinfunction "2_2") (pintype "passive"))
      (node (ref "JB8") (pin "3") (pinfunction "3_3") (pintype "passive"))
      (node (ref "RC_162") (pin "1") (pinfunction "1_1") (pintype "passive"))
      (node (ref "RC_162") (pin "2") (pinfunction "2_2") (pintype "passive"))
      (node (ref "RC_163") (pin "1") (pinfunction "1_1") (pintype "passive"))
      (node (ref "RC_163") (pin "2") (pinfunction "2_2") (pintype "passive"))
      (node (ref "RC_164") (pin "1") (pinfunction "1_1") (pintype "passive"))
      (node (ref "RC_164") (pin "2") (pinfunction "2_2") (pintype "passive"))
      (node (ref "RC_165") (pin "1") (pinfunction "1_1") (pintype "passive"))
      (node (ref "RC_165") (pin "2") (pinfunction "2_2") (pintype "passive"))
      (node (ref "RC_166") (pin "1") (pinfunction "1_1") (pintype "passive"))
      (node (ref "RC_166") (pin "2") (pinfunction "2_2") (pintype "passive"))
      (node (ref "RC_167") (pin "1") (pinfunction "1_1") (pintype "passive"))
      (node (ref "RC_167") (pin "2") (pinfunction "2_2") (pintype "passive"))
      (node (ref "RC_168") (pin "1") (pinfunction "1_1") (pintype "passive"))
      (node (ref "RC_168") (pin "2") (pinfunction "2_2") (pintype "passive"))
      (node (ref "RC_169") (pin "1") (pinfunction "1_1") (pintype "passive"))
      (node (ref "RC_169") (pin "2") (pinfunction "2_2") (pintype "passive"))
      (node (ref "RC_170") (pin "1") (pinfunction "1_1") (pintype "passive"))
      (node (ref "RC_170") (pin "2") (pinfunction "2_2") (pintype "passive"))
      (node (ref "RC_171") (pin "1") (pinfunction "1_1") (pintype "passive"))
      (node (ref "RC_171") (pin "2") (pinfunction "2_2") (pintype "passive"))
      (node (ref "RC_172") (pin "1") (pinfunction "1_1") (pintype "passive"))
      (node (ref "RC_172") (pin "2") (pinfunction "2_2") (pintype "passive"))
      (node (ref "RC_173") (pin "1") (pinfunction "1_1") (pintype "passive"))
      (node (ref "RC_173") (pin "2") (pinfunction "2_2") (pintype "passive"))
      (node (ref "RC_174") (pin "1") (pinfunction "1_1") (pintype "passive"))
      (node (ref "RC_174") (pin "2") (pinfunction "2_2") (pintype "passive"))
      (node (ref "RC_175") (pin "1") (pinfunction "1_1") (pintype "passive"))
      (node (ref "RC_175") (pin "2") (pinfunction "2_2") (pintype "passive"))
      (node (ref "RC_176") (pin "1") (pinfunction "1_1") (pintype "passive"))
      (node (ref "RC_176") (pin "2") (pinfunction "2_2") (pintype "passive"))
      (node (ref "RC_177") (pin "1") (pinfunction "1_1") (pintype "passive"))
      (node (ref "RC_177") (pin "2") (pinfunction "2_2") (pintype "passive"))
      (node (ref "RC_178") (pin "1") (pinfunction "1_1") (pintype "passive"))
      (node (ref "RC_178") (pin "2") (pinfunction "2_2") (pintype "passive"))
      (node (ref "RC_179") (pin "1") (pinfunction "1_1") (pintype "passive"))
      (node (ref "RC_179") (pin "2") (pinfunction "2_2") (pintype "passive"))
      (node (ref "RC_180") (pin "1") (pinfunction "1_1") (pintype "passive"))
      (node (ref "RC_180") (pin "2") (pinfunction "2_2") (pintype "passive"))
      (node (ref "RC_181") (pin "1") (pinfunction "1_1") (pintype "passive"))
      (node (ref "RC_181") (pin "2") (pinfunction "2_2") (pintype "passive"))
      (node (ref "RC_182") (pin "1") (pinfunction "1_1") (pintype "passive"))
      (node (ref "RC_182") (pin "2") (pinfunction "2_2") (pintype "passive"))
      (node (ref "RC_183") (pin "1") (pinfunction "1_1") (pintype "passive"))
      (node (ref "RC_183") (pin "2") (pinfunction "2_2") (pintype "passive"))
      (node (ref "RC_184") (pin "1") (pinfunction "1_1") (pintype "passive"))
      (node (ref "RC_184") (pin "2") (pinfunction "2_2") (pintype "passive"))
      (node (ref "RC_185") (pin "1") (pinfunction "1_1") (pintype "passive"))
      (node (ref "RC_185") (pin "2") (pinfunction "2_2") (pintype "passive"))
      (node (ref "RC_186") (pin "1") (pinfunction "1_1") (pintype "passive"))
      (node (ref "RC_186") (pin "2") (pinfunction "2_2") (pintype "passive"))
      (node (ref "RC_187") (pin "1") (pinfunction "1_1") (pintype "passive"))
      (node (ref "RC_187") (pin "2") (pinfunction "2_2") (pintype "passive"))
      (node (ref "RC_188") (pin "1") (pinfunction "1_1") (pintype "passive"))
      (node (ref "RC_188") (pin "2") (pinfunction "2_2") (pintype "passive"))
      (node (ref "RC_189") (pin "1") (pinfunction "1_1") (pintype "passive"))
      (node (ref "RC_189") (pin "2") (pinfunction "2_2") (pintype "passive"))
      (node (ref "RC_190") (pin "1") (pinfunction "1_1") (pintype "passive"))
      (node (ref "RC_190") (pin "2") (pinfunction "2_2") (pintype "passive"))
      (node (ref "RC_191") (pin "1") (pinfunction "1_1") (pintype "passive"))
      (node (ref "RC_191") (pin "2") (pinfunction "2_2") (pintype "passive"))
      (node (ref "RC_192") (pin "1") (pinfunction "1_1") (pintype "passive"))
      (node (ref "RC_192") (pin "2") (pinfunction "2_2") (pintype "passive"))
      (node (ref "RC_193") (pin "1") (pinfunction "1_1") (pintype "passive"))
      (node (ref "RC_193") (pin "2") (pinfunction "2_2") (pintype "passive"))
      (node (ref "RC_194") (pin "1") (pinfunction "1_1") (pintype "passive"))
      (node (ref "RC_194") (pin "2") (pinfunction "2_2") (pintype "passive"))
      (node (ref "RC_195") (pin "1") (pinfunction "1_1") (pintype "passive"))
      (node (ref "RC_195") (pin "2") (pinfunction "2_2") (pintype "passive"))
      (node (ref "RC_196") (pin "1") (pinfunction "1_1") (pintype "passive"))
      (node (ref "RC_196") (pin "2") (pinfunction "2_2") (pintype "passive"))
      (node (ref "RC_197") (pin "1") (pinfunction "1_1") (pintype "passive"))
      (node (ref "RC_197") (pin "2") (pinfunction "2_2") (pintype "passive"))
    )
    (net (code "7") (name "/BATT_6-7") (class "Default")
      (node (ref "JB14") (pin "1") (pinfunction "1_1") (pintype "passive"))
      (node (ref "JB8") (pin "4") (pinfunction "4_4") (pintype "passive"))
      (node (ref "RC_198") (pin "1") (pinfunction "1_1") (pintype "passive"))
      (node (ref "RC_198") (pin "2") (pinfunction "2_2") (pintype "passive"))
      (node (ref "RC_199") (pin "1") (pinfunction "1_1") (pintype "passive"))
      (node (ref "RC_199") (pin "2") (pinfunction "2_2") (pintype "passive"))
      (node (ref "RC_200") (pin "1") (pinfunction "1_1") (pintype "passive"))
      (node (ref "RC_200") (pin "2") (pinfunction "2_2") (pintype "passive"))
      (node (ref "RC_201") (pin "1") (pinfunction "1_1") (pintype "passive"))
      (node (ref "RC_201") (pin "2") (pinfunction "2_2") (pintype "passive"))
      (node (ref "RC_202") (pin "1") (pinfunction "1_1") (pintype "passive"))
      (node (ref "RC_202") (pin "2") (pinfunction "2_2") (pintype "passive"))
      (node (ref "RC_203") (pin "1") (pinfunction "1_1") (pintype "passive"))
      (node (ref "RC_203") (pin "2") (pinfunction "2_2") (pintype "passive"))
      (node (ref "RC_204") (pin "1") (pinfunction "1_1") (pintype "passive"))
      (node (ref "RC_204") (pin "2") (pinfunction "2_2") (pintype "passive"))
      (node (ref "RC_205") (pin "1") (pinfunction "1_1") (pintype "passive"))
      (node (ref "RC_205") (pin "2") (pinfunction "2_2") (pintype "passive"))
      (node (ref "RC_206") (pin "1") (pinfunction "1_1") (pintype "passive"))
      (node (ref "RC_206") (pin "2") (pinfunction "2_2") (pintype "passive"))
      (node (ref "RC_207") (pin "1") (pinfunction "1_1") (pintype "passive"))
      (node (ref "RC_207") (pin "2") (pinfunction "2_2") (pintype "passive"))
      (node (ref "RC_208") (pin "1") (pinfunction "1_1") (pintype "passive"))
      (node (ref "RC_208") (pin "2") (pinfunction "2_2") (pintype "passive"))
      (node (ref "RC_209") (pin "1") (pinfunction "1_1") (pintype "passive"))
      (node (ref "RC_209") (pin "2") (pinfunction "2_2") (pintype "passive"))
      (node (ref "RC_210") (pin "1") (pinfunction "1_1") (pintype "passive"))
      (node (ref "RC_210") (pin "2") (pinfunction "2_2") (pintype "passive"))
      (node (ref "RC_211") (pin "1") (pinfunction "1_1") (pintype "passive"))
      (node (ref "RC_211") (pin "2") (pinfunction "2_2") (pintype "passive"))
      (node (ref "RC_212") (pin "1") (pinfunction "1_1") (pintype "passive"))
      (node (ref "RC_212") (pin "2") (pinfunction "2_2") (pintype "passive"))
      (node (ref "RC_213") (pin "1") (pinfunction "1_1") (pintype "passive"))
      (node (ref "RC_213") (pin "2") (pinfunction "2_2") (pintype "passive"))
      (node (ref "RC_214") (pin "1") (pinfunction "1_1") (pintype "passive"))
      (node (ref "RC_214") (pin "2") (pinfunction "2_2") (pintype "passive"))
      (node (ref "RC_215") (pin "1") (pinfunction "1_1") (pintype "passive"))
      (node (ref "RC_215") (pin "2") (pinfunction "2_2") (pintype "passive"))
      (node (ref "RC_216") (pin "1") (pinfunction "1_1") (pintype "passive"))
      (node (ref "RC_216") (pin "2") (pinfunction "2_2") (pintype "passive"))
      (node (ref "RC_217") (pin "1") (pinfunction "1_1") (pintype "passive"))
      (node (ref "RC_217") (pin "2") (pinfunction "2_2") (pintype "passive"))
      (node (ref "RC_218") (pin "1") (pinfunction "1_1") (pintype "passive"))
      (node (ref "RC_218") (pin "2") (pinfunction "2_2") (pintype "passive"))
      (node (ref "RC_219") (pin "1") (pinfunction "1_1") (pintype "passive"))
      (node (ref "RC_219") (pin "2") (pinfunction "2_2") (pintype "passive"))
      (node (ref "RC_220") (pin "1") (pinfunction "1_1") (pintype "passive"))
      (node (ref "RC_220") (pin "2") (pinfunction "2_2") (pintype "passive"))
      (node (ref "RC_221") (pin "1") (pinfunction "1_1") (pintype "passive"))
      (node (ref "RC_221") (pin "2") (pinfunction "2_2") (pintype "passive"))
      (node (ref "RC_222") (pin "1") (pinfunction "1_1") (pintype "passive"))
      (node (ref "RC_222") (pin "2") (pinfunction "2_2") (pintype "passive"))
      (node (ref "RC_223") (pin "1") (pinfunction "1_1") (pintype "passive"))
      (node (ref "RC_223") (pin "2") (pinfunction "2_2") (pintype "passive"))
      (node (ref "RC_224") (pin "1") (pinfunction "1_1") (pintype "passive"))
      (node (ref "RC_224") (pin "2") (pinfunction "2_2") (pintype "passive"))
      (node (ref "RC_225") (pin "1") (pinfunction "1_1") (pintype "passive"))
      (node (ref "RC_225") (pin "2") (pinfunction "2_2") (pintype "passive"))
      (node (ref "RC_226") (pin "1") (pinfunction "1_1") (pintype "passive"))
      (node (ref "RC_226") (pin "2") (pinfunction "2_2") (pintype "passive"))
      (node (ref "RC_227") (pin "1") (pinfunction "1_1") (pintype "passive"))
      (node (ref "RC_227") (pin "2") (pinfunction "2_2") (pintype "passive"))
      (node (ref "RC_228") (pin "1") (pinfunction "1_1") (pintype "passive"))
      (node (ref "RC_228") (pin "2") (pinfunction "2_2") (pintype "passive"))
      (node (ref "RC_229") (pin "1") (pinfunction "1_1") (pintype "passive"))
      (node (ref "RC_229") (pin "2") (pinfunction "2_2") (pintype "passive"))
      (node (ref "RC_230") (pin "1") (pinfunction "1_1") (pintype "passive"))
      (node (ref "RC_230") (pin "2") (pinfunction "2_2") (pintype "passive"))
      (node (ref "RC_231") (pin "1") (pinfunction "1_1") (pintype "passive"))
      (node (ref "RC_231") (pin "2") (pinfunction "2_2") (pintype "passive"))
      (node (ref "RC_232") (pin "1") (pinfunction "1_1") (pintype "passive"))
      (node (ref "RC_232") (pin "2") (pinfunction "2_2") (pintype "passive"))
      (node (ref "RC_233") (pin "1") (pinfunction "1_1") (pintype "passive"))
      (node (ref "RC_233") (pin "2") (pinfunction "2_2") (pintype "passive"))
    )
    (net (code "8") (name "/BATT_7-8") (class "Default")
      (node (ref "JB15") (pin "4") (pinfunction "4_4") (pintype "passive"))
      (node (ref "JB9") (pin "1") (pinfunction "1_1") (pintype "passive"))
      (node (ref "NT_8_9") (pin "1") (pinfunction "1_1") (pintype "passive"))
      (node (ref "RC_234") (pin "1") (pinfunction "1_1") (pintype "passive"))
      (node (ref "RC_234") (pin "2") (pinfunction "2_2") (pintype "passive"))
      (node (ref "RC_235") (pin "1") (pinfunction "1_1") (pintype "passive"))
      (node (ref "RC_235") (pin "2") (pinfunction "2_2") (pintype "passive"))
      (node (ref "RC_236") (pin "1") (pinfunction "1_1") (pintype "passive"))
      (node (ref "RC_236") (pin "2") (pinfunction "2_2") (pintype "passive"))
      (node (ref "RC_237") (pin "1") (pinfunction "1_1") (pintype "passive"))
      (node (ref "RC_237") (pin "2") (pinfunction "2_2") (pintype "passive"))
      (node (ref "RC_238") (pin "1") (pinfunction "1_1") (pintype "passive"))
      (node (ref "RC_238") (pin "2") (pinfunction "2_2") (pintype "passive"))
      (node (ref "RC_239") (pin "1") (pinfunction "1_1") (pintype "passive"))
      (node (ref "RC_239") (pin "2") (pinfunction "2_2") (pintype "passive"))
      (node (ref "RC_240") (pin "1") (pinfunction "1_1") (pintype "passive"))
      (node (ref "RC_240") (pin "2") (pinfunction "2_2") (pintype "passive"))
      (node (ref "RC_241") (pin "1") (pinfunction "1_1") (pintype "passive"))
      (node (ref "RC_241") (pin "2") (pinfunction "2_2") (pintype "passive"))
      (node (ref "RC_242") (pin "1") (pinfunction "1_1") (pintype "passive"))
      (node (ref "RC_242") (pin "2") (pinfunction "2_2") (pintype "passive"))
      (node (ref "RC_243") (pin "1") (pinfunction "1_1") (pintype "passive"))
      (node (ref "RC_243") (pin "2") (pinfunction "2_2") (pintype "passive"))
      (node (ref "RC_244") (pin "1") (pinfunction "1_1") (pintype "passive"))
      (node (ref "RC_244") (pin "2") (pinfunction "2_2") (pintype "passive"))
      (node (ref "RC_245") (pin "1") (pinfunction "1_1") (pintype "passive"))
      (node (ref "RC_245") (pin "2") (pinfunction "2_2") (pintype "passive"))
      (node (ref "RC_246") (pin "1") (pinfunction "1_1") (pintype "passive"))
      (node (ref "RC_246") (pin "2") (pinfunction "2_2") (pintype "passive"))
      (node (ref "RC_247") (pin "1") (pinfunction "1_1") (pintype "passive"))
      (node (ref "RC_247") (pin "2") (pinfunction "2_2") (pintype "passive"))
      (node (ref "RC_248") (pin "1") (pinfunction "1_1") (pintype "passive"))
      (node (ref "RC_248") (pin "2") (pinfunction "2_2") (pintype "passive"))
      (node (ref "RC_249") (pin "1") (pinfunction "1_1") (pintype "passive"))
      (node (ref "RC_249") (pin "2") (pinfunction "2_2") (pintype "passive"))
      (node (ref "RC_250") (pin "1") (pinfunction "1_1") (pintype "passive"))
      (node (ref "RC_250") (pin "2") (pinfunction "2_2") (pintype "passive"))
      (node (ref "RC_251") (pin "1") (pinfunction "1_1") (pintype "passive"))
      (node (ref "RC_251") (pin "2") (pinfunction "2_2") (pintype "passive"))
      (node (ref "RC_252") (pin "1") (pinfunction "1_1") (pintype "passive"))
      (node (ref "RC_252") (pin "2") (pinfunction "2_2") (pintype "passive"))
      (node (ref "RC_253") (pin "1") (pinfunction "1_1") (pintype "passive"))
      (node (ref "RC_253") (pin "2") (pinfunction "2_2") (pintype "passive"))
      (node (ref "RC_254") (pin "1") (pinfunction "1_1") (pintype "passive"))
      (node (ref "RC_254") (pin "2") (pinfunction "2_2") (pintype "passive"))
      (node (ref "RC_255") (pin "1") (pinfunction "1_1") (pintype "passive"))
      (node (ref "RC_255") (pin "2") (pinfunction "2_2") (pintype "passive"))
      (node (ref "RC_256") (pin "1") (pinfunction "1_1") (pintype "passive"))
      (node (ref "RC_256") (pin "2") (pinfunction "2_2") (pintype "passive"))
      (node (ref "RC_257") (pin "1") (pinfunction "1_1") (pintype "passive"))
      (node (ref "RC_257") (pin "2") (pinfunction "2_2") (pintype "passive"))
      (node (ref "RC_258") (pin "1") (pinfunction "1_1") (pintype "passive"))
      (node (ref "RC_258") (pin "2") (pinfunction "2_2") (pintype "passive"))
      (node (ref "RC_259") (pin "1") (pinfunction "1_1") (pintype "passive"))
      (node (ref "RC_259") (pin "2") (pinfunction "2_2") (pintype "passive"))
      (node (ref "RC_260") (pin "1") (pinfunction "1_1") (pintype "passive"))
      (node (ref "RC_260") (pin "2") (pinfunction "2_2") (pintype "passive"))
      (node (ref "RC_261") (pin "1") (pinfunction "1_1") (pintype "passive"))
      (node (ref "RC_261") (pin "2") (pinfunction "2_2") (pintype "passive"))
      (node (ref "RC_262") (pin "1") (pinfunction "1_1") (pintype "passive"))
      (node (ref "RC_262") (pin "2") (pinfunction "2_2") (pintype "passive"))
      (node (ref "RC_263") (pin "1") (pinfunction "1_1") (pintype "passive"))
      (node (ref "RC_263") (pin "2") (pinfunction "2_2") (pintype "passive"))
      (node (ref "RC_264") (pin "1") (pinfunction "1_1") (pintype "passive"))
      (node (ref "RC_264") (pin "2") (pinfunction "2_2") (pintype "passive"))
      (node (ref "RC_265") (pin "1") (pinfunction "1_1") (pintype "passive"))
      (node (ref "RC_265") (pin "2") (pinfunction "2_2") (pintype "passive"))
      (node (ref "RC_266") (pin "1") (pinfunction "1_1") (pintype "passive"))
      (node (ref "RC_266") (pin "2") (pinfunction "2_2") (pintype "passive"))
      (node (ref "RC_267") (pin "1") (pinfunction "1_1") (pintype "passive"))
      (node (ref "RC_267") (pin "2") (pinfunction "2_2") (pintype "passive"))
      (node (ref "RC_268") (pin "1") (pinfunction "1_1") (pintype "passive"))
      (node (ref "RC_268") (pin "2") (pinfunction "2_2") (pintype "passive"))
      (node (ref "RC_269") (pin "1") (pinfunction "1_1") (pintype "passive"))
      (node (ref "RC_269") (pin "2") (pinfunction "2_2") (pintype "passive"))
    )
    (net (code "9") (name "/BATT_8-9") (class "Default")
      (node (ref "JB15") (pin "2") (pinfunction "2_2") (pintype "passive"))
      (node (ref "JB9") (pin "3") (pinfunction "3_3") (pintype "passive"))
      (node (ref "RC_270") (pin "1") (pinfunction "1_1") (pintype "passive"))
      (node (ref "RC_270") (pin "2") (pinfunction "2_2") (pintype "passive"))
      (node (ref "RC_271") (pin "1") (pinfunction "1_1") (pintype "passive"))
      (node (ref "RC_271") (pin "2") (pinfunction "2_2") (pintype "passive"))
      (node (ref "RC_272") (pin "1") (pinfunction "1_1") (pintype "passive"))
      (node (ref "RC_272") (pin "2") (pinfunction "2_2") (pintype "passive"))
      (node (ref "RC_273") (pin "1") (pinfunction "1_1") (pintype "passive"))
      (node (ref "RC_273") (pin "2") (pinfunction "2_2") (pintype "passive"))
      (node (ref "RC_274") (pin "1") (pinfunction "1_1") (pintype "passive"))
      (node (ref "RC_274") (pin "2") (pinfunction "2_2") (pintype "passive"))
      (node (ref "RC_275") (pin "1") (pinfunction "1_1") (pintype "passive"))
      (node (ref "RC_275") (pin "2") (pinfunction "2_2") (pintype "passive"))
      (node (ref "RC_276") (pin "1") (pinfunction "1_1") (pintype "passive"))
      (node (ref "RC_276") (pin "2") (pinfunction "2_2") (pintype "passive"))
      (node (ref "RC_277") (pin "1") (pinfunction "1_1") (pintype "passive"))
      (node (ref "RC_277") (pin "2") (pinfunction "2_2") (pintype "passive"))
      (node (ref "RC_278") (pin "1") (pinfunction "1_1") (pintype "passive"))
      (node (ref "RC_278") (pin "2") (pinfunction "2_2") (pintype "passive"))
      (node (ref "RC_279") (pin "1") (pinfunction "1_1") (pintype "passive"))
      (node (ref "RC_279") (pin "2") (pinfunction "2_2") (pintype "passive"))
      (node (ref "RC_280") (pin "1") (pinfunction "1_1") (pintype "passive"))
      (node (ref "RC_280") (pin "2") (pinfunction "2_2") (pintype "passive"))
      (node (ref "RC_281") (pin "1") (pinfunction "1_1") (pintype "passive"))
      (node (ref "RC_281") (pin "2") (pinfunction "2_2") (pintype "passive"))
      (node (ref "RC_282") (pin "1") (pinfunction "1_1") (pintype "passive"))
      (node (ref "RC_282") (pin "2") (pinfunction "2_2") (pintype "passive"))
      (node (ref "RC_283") (pin "1") (pinfunction "1_1") (pintype "passive"))
      (node (ref "RC_283") (pin "2") (pinfunction "2_2") (pintype "passive"))
      (node (ref "RC_284") (pin "1") (pinfunction "1_1") (pintype "passive"))
      (node (ref "RC_284") (pin "2") (pinfunction "2_2") (pintype "passive"))
      (node (ref "RC_285") (pin "1") (pinfunction "1_1") (pintype "passive"))
      (node (ref "RC_285") (pin "2") (pinfunction "2_2") (pintype "passive"))
      (node (ref "RC_286") (pin "1") (pinfunction "1_1") (pintype "passive"))
      (node (ref "RC_286") (pin "2") (pinfunction "2_2") (pintype "passive"))
      (node (ref "RC_287") (pin "1") (pinfunction "1_1") (pintype "passive"))
      (node (ref "RC_287") (pin "2") (pinfunction "2_2") (pintype "passive"))
      (node (ref "RC_288") (pin "1") (pinfunction "1_1") (pintype "passive"))
      (node (ref "RC_288") (pin "2") (pinfunction "2_2") (pintype "passive"))
      (node (ref "RC_289") (pin "1") (pinfunction "1_1") (pintype "passive"))
      (node (ref "RC_289") (pin "2") (pinfunction "2_2") (pintype "passive"))
      (node (ref "RC_290") (pin "1") (pinfunction "1_1") (pintype "passive"))
      (node (ref "RC_290") (pin "2") (pinfunction "2_2") (pintype "passive"))
      (node (ref "RC_291") (pin "1") (pinfunction "1_1") (pintype "passive"))
      (node (ref "RC_291") (pin "2") (pinfunction "2_2") (pintype "passive"))
      (node (ref "RC_292") (pin "1") (pinfunction "1_1") (pintype "passive"))
      (node (ref "RC_292") (pin "2") (pinfunction "2_2") (pintype "passive"))
      (node (ref "RC_293") (pin "1") (pinfunction "1_1") (pintype "passive"))
      (node (ref "RC_293") (pin "2") (pinfunction "2_2") (pintype "passive"))
      (node (ref "RC_294") (pin "1") (pinfunction "1_1") (pintype "passive"))
      (node (ref "RC_294") (pin "2") (pinfunction "2_2") (pintype "passive"))
      (node (ref "RC_295") (pin "1") (pinfunction "1_1") (pintype "passive"))
      (node (ref "RC_295") (pin "2") (pinfunction "2_2") (pintype "passive"))
      (node (ref "RC_296") (pin "1") (pinfunction "1_1") (pintype "passive"))
      (node (ref "RC_296") (pin "2") (pinfunction "2_2") (pintype "passive"))
      (node (ref "RC_297") (pin "1") (pinfunction "1_1") (pintype "passive"))
      (node (ref "RC_297") (pin "2") (pinfunction "2_2") (pintype "passive"))
      (node (ref "RC_298") (pin "1") (pinfunction "1_1") (pintype "passive"))
      (node (ref "RC_298") (pin "2") (pinfunction "2_2") (pintype "passive"))
      (node (ref "RC_299") (pin "1") (pinfunction "1_1") (pintype "passive"))
      (node (ref "RC_299") (pin "2") (pinfunction "2_2") (pintype "passive"))
      (node (ref "RC_300") (pin "1") (pinfunction "1_1") (pintype "passive"))
      (node (ref "RC_300") (pin "2") (pinfunction "2_2") (pintype "passive"))
      (node (ref "RC_301") (pin "1") (pinfunction "1_1") (pintype "passive"))
      (node (ref "RC_301") (pin "2") (pinfunction "2_2") (pintype "passive"))
      (node (ref "RC_302") (pin "1") (pinfunction "1_1") (pintype "passive"))
      (node (ref "RC_302") (pin "2") (pinfunction "2_2") (pintype "passive"))
      (node (ref "RC_303") (pin "1") (pinfunction "1_1") (pintype "passive"))
      (node (ref "RC_303") (pin "2") (pinfunction "2_2") (pintype "passive"))
      (node (ref "RC_304") (pin "1") (pinfunction "1_1") (pintype "passive"))
      (node (ref "RC_304") (pin "2") (pinfunction "2_2") (pintype "passive"))
      (node (ref "RC_305") (pin "1") (pinfunction "1_1") (pintype "passive"))
      (node (ref "RC_305") (pin "2") (pinfunction "2_2") (pintype "passive"))
    )
    (net (code "10") (name "/BATT_9-10") (class "Default")
      (node (ref "JB15") (pin "1") (pinfunction "1_1") (pintype "passive"))
      (node (ref "JB9") (pin "4") (pinfunction "4_4") (pintype "passive"))
      (node (ref "RC_306") (pin "1") (pinfunction "1_1") (pintype "passive"))
      (node (ref "RC_306") (pin "2") (pinfunction "2_2") (pintype "passive"))
      (node (ref "RC_307") (pin "1") (pinfunction "1_1") (pintype "passive"))
      (node (ref "RC_307") (pin "2") (pinfunction "2_2") (pintype "passive"))
      (node (ref "RC_308") (pin "1") (pinfunction "1_1") (pintype "passive"))
      (node (ref "RC_308") (pin "2") (pinfunction "2_2") (pintype "passive"))
      (node (ref "RC_309") (pin "1") (pinfunction "1_1") (pintype "passive"))
      (node (ref "RC_309") (pin "2") (pinfunction "2_2") (pintype "passive"))
      (node (ref "RC_310") (pin "1") (pinfunction "1_1") (pintype "passive"))
      (node (ref "RC_310") (pin "2") (pinfunction "2_2") (pintype "passive"))
      (node (ref "RC_311") (pin "1") (pinfunction "1_1") (pintype "passive"))
      (node (ref "RC_311") (pin "2") (pinfunction "2_2") (pintype "passive"))
      (node (ref "RC_312") (pin "1") (pinfunction "1_1") (pintype "passive"))
      (node (ref "RC_312") (pin "2") (pinfunction "2_2") (pintype "passive"))
      (node (ref "RC_313") (pin "1") (pinfunction "1_1") (pintype "passive"))
      (node (ref "RC_313") (pin "2") (pinfunction "2_2") (pintype "passive"))
      (node (ref "RC_314") (pin "1") (pinfunction "1_1") (pintype "passive"))
      (node (ref "RC_314") (pin "2") (pinfunction "2_2") (pintype "passive"))
      (node (ref "RC_315") (pin "1") (pinfunction "1_1") (pintype "passive"))
      (node (ref "RC_315") (pin "2") (pinfunction "2_2") (pintype "passive"))
      (node (ref "RC_316") (pin "1") (pinfunction "1_1") (pintype "passive"))
      (node (ref "RC_316") (pin "2") (pinfunction "2_2") (pintype "passive"))
      (node (ref "RC_317") (pin "1") (pinfunction "1_1") (pintype "passive"))
      (node (ref "RC_317") (pin "2") (pinfunction "2_2") (pintype "passive"))
      (node (ref "RC_318") (pin "1") (pinfunction "1_1") (pintype "passive"))
      (node (ref "RC_318") (pin "2") (pinfunction "2_2") (pintype "passive"))
      (node (ref "RC_319") (pin "1") (pinfunction "1_1") (pintype "passive"))
      (node (ref "RC_319") (pin "2") (pinfunction "2_2") (pintype "passive"))
      (node (ref "RC_320") (pin "1") (pinfunction "1_1") (pintype "passive"))
      (node (ref "RC_320") (pin "2") (pinfunction "2_2") (pintype "passive"))
      (node (ref "RC_321") (pin "1") (pinfunction "1_1") (pintype "passive"))
      (node (ref "RC_321") (pin "2") (pinfunction "2_2") (pintype "passive"))
      (node (ref "RC_322") (pin "1") (pinfunction "1_1") (pintype "passive"))
      (node (ref "RC_322") (pin "2") (pinfunction "2_2") (pintype "passive"))
      (node (ref "RC_323") (pin "1") (pinfunction "1_1") (pintype "passive"))
      (node (ref "RC_323") (pin "2") (pinfunction "2_2") (pintype "passive"))
      (node (ref "RC_324") (pin "1") (pinfunction "1_1") (pintype "passive"))
      (node (ref "RC_324") (pin "2") (pinfunction "2_2") (pintype "passive"))
      (node (ref "RC_325") (pin "1") (pinfunction "1_1") (pintype "passive"))
      (node (ref "RC_325") (pin "2") (pinfunction "2_2") (pintype "passive"))
      (node (ref "RC_326") (pin "1") (pinfunction "1_1") (pintype "passive"))
      (node (ref "RC_326") (pin "2") (pinfunction "2_2") (pintype "passive"))
      (node (ref "RC_327") (pin "1") (pinfunction "1_1") (pintype "passive"))
      (node (ref "RC_327") (pin "2") (pinfunction "2_2") (pintype "passive"))
      (node (ref "RC_328") (pin "1") (pinfunction "1_1") (pintype "passive"))
      (node (ref "RC_328") (pin "2") (pinfunction "2_2") (pintype "passive"))
      (node (ref "RC_329") (pin "1") (pinfunction "1_1") (pintype "passive"))
      (node (ref "RC_329") (pin "2") (pinfunction "2_2") (pintype "passive"))
      (node (ref "RC_330") (pin "1") (pinfunction "1_1") (pintype "passive"))
      (node (ref "RC_330") (pin "2") (pinfunction "2_2") (pintype "passive"))
      (node (ref "RC_331") (pin "1") (pinfunction "1_1") (pintype "passive"))
      (node (ref "RC_331") (pin "2") (pinfunction "2_2") (pintype "passive"))
      (node (ref "RC_332") (pin "1") (pinfunction "1_1") (pintype "passive"))
      (node (ref "RC_332") (pin "2") (pinfunction "2_2") (pintype "passive"))
      (node (ref "RC_333") (pin "1") (pinfunction "1_1") (pintype "passive"))
      (node (ref "RC_333") (pin "2") (pinfunction "2_2") (pintype "passive"))
      (node (ref "RC_334") (pin "1") (pinfunction "1_1") (pintype "passive"))
      (node (ref "RC_334") (pin "2") (pinfunction "2_2") (pintype "passive"))
      (node (ref "RC_335") (pin "1") (pinfunction "1_1") (pintype "passive"))
      (node (ref "RC_335") (pin "2") (pinfunction "2_2") (pintype "passive"))
      (node (ref "RC_336") (pin "1") (pinfunction "1_1") (pintype "passive"))
      (node (ref "RC_336") (pin "2") (pinfunction "2_2") (pintype "passive"))
      (node (ref "RC_337") (pin "1") (pinfunction "1_1") (pintype "passive"))
      (node (ref "RC_337") (pin "2") (pinfunction "2_2") (pintype "passive"))
      (node (ref "RC_338") (pin "1") (pinfunction "1_1") (pintype "passive"))
      (node (ref "RC_338") (pin "2") (pinfunction "2_2") (pintype "passive"))
      (node (ref "RC_339") (pin "1") (pinfunction "1_1") (pintype "passive"))
      (node (ref "RC_339") (pin "2") (pinfunction "2_2") (pintype "passive"))
      (node (ref "RC_340") (pin "1") (pinfunction "1_1") (pintype "passive"))
      (node (ref "RC_340") (pin "2") (pinfunction "2_2") (pintype "passive"))
      (node (ref "RC_341") (pin "1") (pinfunction "1_1") (pintype "passive"))
      (node (ref "RC_341") (pin "2") (pinfunction "2_2") (pintype "passive"))
    )
    (net (code "11") (name "/BATT_10-11") (class "Default")
      (node (ref "JB10") (pin "1") (pinfunction "1_1") (pintype "passive"))
      (node (ref "JB16") (pin "4") (pinfunction "4_4") (pintype "passive"))
      (node (ref "RC_342") (pin "1") (pinfunction "1_1") (pintype "passive"))
      (node (ref "RC_342") (pin "2") (pinfunction "2_2") (pintype "passive"))
      (node (ref "RC_343") (pin "1") (pinfunction "1_1") (pintype "passive"))
      (node (ref "RC_343") (pin "2") (pinfunction "2_2") (pintype "passive"))
      (node (ref "RC_344") (pin "1") (pinfunction "1_1") (pintype "passive"))
      (node (ref "RC_344") (pin "2") (pinfunction "2_2") (pintype "passive"))
      (node (ref "RC_345") (pin "1") (pinfunction "1_1") (pintype "passive"))
      (node (ref "RC_345") (pin "2") (pinfunction "2_2") (pintype "passive"))
      (node (ref "RC_346") (pin "1") (pinfunction "1_1") (pintype "passive"))
      (node (ref "RC_346") (pin "2") (pinfunction "2_2") (pintype "passive"))
      (node (ref "RC_347") (pin "1") (pinfunction "1_1") (pintype "passive"))
      (node (ref "RC_347") (pin "2") (pinfunction "2_2") (pintype "passive"))
      (node (ref "RC_348") (pin "1") (pinfunction "1_1") (pintype "passive"))
      (node (ref "RC_348") (pin "2") (pinfunction "2_2") (pintype "passive"))
      (node (ref "RC_349") (pin "1") (pinfunction "1_1") (pintype "passive"))
      (node (ref "RC_349") (pin "2") (pinfunction "2_2") (pintype "passive"))
      (node (ref "RC_350") (pin "1") (pinfunction "1_1") (pintype "passive"))
      (node (ref "RC_350") (pin "2") (pinfunction "2_2") (pintype "passive"))
      (node (ref "RC_351") (pin "1") (pinfunction "1_1") (pintype "passive"))
      (node (ref "RC_351") (pin "2") (pinfunction "2_2") (pintype "passive"))
      (node (ref "RC_352") (pin "1") (pinfunction "1_1") (pintype "passive"))
      (node (ref "RC_352") (pin "2") (pinfunction "2_2") (pintype "passive"))
      (node (ref "RC_353") (pin "1") (pinfunction "1_1") (pintype "passive"))
      (node (ref "RC_353") (pin "2") (pinfunction "2_2") (pintype "passive"))
      (node (ref "RC_354") (pin "1") (pinfunction "1_1") (pintype "passive"))
      (node (ref "RC_354") (pin "2") (pinfunction "2_2") (pintype "passive"))
      (node (ref "RC_355") (pin "1") (pinfunction "1_1") (pintype "passive"))
      (node (ref "RC_355") (pin "2") (pinfunction "2_2") (pintype "passive"))
      (node (ref "RC_356") (pin "1") (pinfunction "1_1") (pintype "passive"))
      (node (ref "RC_356") (pin "2") (pinfunction "2_2") (pintype "passive"))
      (node (ref "RC_357") (pin "1") (pinfunction "1_1") (pintype "passive"))
      (node (ref "RC_357") (pin "2") (pinfunction "2_2") (pintype "passive"))
      (node (ref "RC_358") (pin "1") (pinfunction "1_1") (pintype "passive"))
      (node (ref "RC_358") (pin "2") (pinfunction "2_2") (pintype "passive"))
      (node (ref "RC_359") (pin "1") (pinfunction "1_1") (pintype "passive"))
      (node (ref "RC_359") (pin "2") (pinfunction "2_2") (pintype "passive"))
      (node (ref "RC_360") (pin "1") (pinfunction "1_1") (pintype "passive"))
      (node (ref "RC_360") (pin "2") (pinfunction "2_2") (pintype "passive"))
      (node (ref "RC_361") (pin "1") (pinfunction "1_1") (pintype "passive"))
      (node (ref "RC_361") (pin "2") (pinfunction "2_2") (pintype "passive"))
      (node (ref "RC_362") (pin "1") (pinfunction "1_1") (pintype "passive"))
      (node (ref "RC_362") (pin "2") (pinfunction "2_2") (pintype "passive"))
      (node (ref "RC_363") (pin "1") (pinfunction "1_1") (pintype "passive"))
      (node (ref "RC_363") (pin "2") (pinfunction "2_2") (pintype "passive"))
      (node (ref "RC_364") (pin "1") (pinfunction "1_1") (pintype "passive"))
      (node (ref "RC_364") (pin "2") (pinfunction "2_2") (pintype "passive"))
      (node (ref "RC_365") (pin "1") (pinfunction "1_1") (pintype "passive"))
      (node (ref "RC_365") (pin "2") (pinfunction "2_2") (pintype "passive"))
      (node (ref "RC_366") (pin "1") (pinfunction "1_1") (pintype "passive"))
      (node (ref "RC_366") (pin "2") (pinfunction "2_2") (pintype "passive"))
      (node (ref "RC_367") (pin "1") (pinfunction "1_1") (pintype "passive"))
      (node (ref "RC_367") (pin "2") (pinfunction "2_2") (pintype "passive"))
      (node (ref "RC_368") (pin "1") (pinfunction "1_1") (pintype "passive"))
      (node (ref "RC_368") (pin "2") (pinfunction "2_2") (pintype "passive"))
      (node (ref "RC_369") (pin "1") (pinfunction "1_1") (pintype "passive"))
      (node (ref "RC_369") (pin "2") (pinfunction "2_2") (pintype "passive"))
      (node (ref "RC_370") (pin "1") (pinfunction "1_1") (pintype "passive"))
      (node (ref "RC_370") (pin "2") (pinfunction "2_2") (pintype "passive"))
      (node (ref "RC_371") (pin "1") (pinfunction "1_1") (pintype "passive"))
      (node (ref "RC_371") (pin "2") (pinfunction "2_2") (pintype "passive"))
      (node (ref "RC_372") (pin "1") (pinfunction "1_1") (pintype "passive"))
      (node (ref "RC_372") (pin "2") (pinfunction "2_2") (pintype "passive"))
      (node (ref "RC_373") (pin "1") (pinfunction "1_1") (pintype "passive"))
      (node (ref "RC_373") (pin "2") (pinfunction "2_2") (pintype "passive"))
      (node (ref "RC_374") (pin "1") (pinfunction "1_1") (pintype "passive"))
      (node (ref "RC_374") (pin "2") (pinfunction "2_2") (pintype "passive"))
      (node (ref "RC_375") (pin "1") (pinfunction "1_1") (pintype "passive"))
      (node (ref "RC_375") (pin "2") (pinfunction "2_2") (pintype "passive"))
      (node (ref "RC_376") (pin "1") (pinfunction "1_1") (pintype "passive"))
      (node (ref "RC_376") (pin "2") (pinfunction "2_2") (pintype "passive"))
      (node (ref "RC_377") (pin "1") (pinfunction "1_1") (pintype "passive"))
      (node (ref "RC_377") (pin "2") (pinfunction "2_2") (pintype "passive"))
    )
    (net (code "12") (name "/BATT_11-12") (class "Default")
      (node (ref "JB10") (pin "3") (pinfunction "3_3") (pintype "passive"))
      (node (ref "JB16") (pin "2") (pinfunction "2_2") (pintype "passive"))
      (node (ref "NT_13_14") (pin "2") (pinfunction "2_2") (pintype "passive"))
      (node (ref "NT_13_14_2") (pin "2") (pinfunction "2_2") (pintype "passive"))
      (node (ref "RC_378") (pin "1") (pinfunction "1_1") (pintype "passive"))
      (node (ref "RC_378") (pin "2") (pinfunction "2_2") (pintype "passive"))
      (node (ref "RC_379") (pin "1") (pinfunction "1_1") (pintype "passive"))
      (node (ref "RC_379") (pin "2") (pinfunction "2_2") (pintype "passive"))
      (node (ref "RC_380") (pin "1") (pinfunction "1_1") (pintype "passive"))
      (node (ref "RC_380") (pin "2") (pinfunction "2_2") (pintype "passive"))
      (node (ref "RC_381") (pin "1") (pinfunction "1_1") (pintype "passive"))
      (node (ref "RC_381") (pin "2") (pinfunction "2_2") (pintype "passive"))
      (node (ref "RC_382") (pin "1") (pinfunction "1_1") (pintype "passive"))
      (node (ref "RC_382") (pin "2") (pinfunction "2_2") (pintype "passive"))
      (node (ref "RC_383") (pin "1") (pinfunction "1_1") (pintype "passive"))
      (node (ref "RC_383") (pin "2") (pinfunction "2_2") (pintype "passive"))
      (node (ref "RC_384") (pin "1") (pinfunction "1_1") (pintype "passive"))
      (node (ref "RC_384") (pin "2") (pinfunction "2_2") (pintype "passive"))
      (node (ref "RC_385") (pin "1") (pinfunction "1_1") (pintype "passive"))
      (node (ref "RC_385") (pin "2") (pinfunction "2_2") (pintype "passive"))
      (node (ref "RC_386") (pin "1") (pinfunction "1_1") (pintype "passive"))
      (node (ref "RC_386") (pin "2") (pinfunction "2_2") (pintype "passive"))
      (node (ref "RC_387") (pin "1") (pinfunction "1_1") (pintype "passive"))
      (node (ref "RC_387") (pin "2") (pinfunction "2_2") (pintype "passive"))
      (node (ref "RC_388") (pin "1") (pinfunction "1_1") (pintype "passive"))
      (node (ref "RC_388") (pin "2") (pinfunction "2_2") (pintype "passive"))
      (node (ref "RC_389") (pin "1") (pinfunction "1_1") (pintype "passive"))
      (node (ref "RC_389") (pin "2") (pinfunction "2_2") (pintype "passive"))
      (node (ref "RC_390") (pin "1") (pinfunction "1_1") (pintype "passive"))
      (node (ref "RC_390") (pin "2") (pinfunction "2_2") (pintype "passive"))
      (node (ref "RC_391") (pin "1") (pinfunction "1_1") (pintype "passive"))
      (node (ref "RC_391") (pin "2") (pinfunction "2_2") (pintype "passive"))
      (node (ref "RC_392") (pin "1") (pinfunction "1_1") (pintype "passive"))
      (node (ref "RC_392") (pin "2") (pinfunction "2_2") (pintype "passive"))
      (node (ref "RC_393") (pin "1") (pinfunction "1_1") (pintype "passive"))
      (node (ref "RC_393") (pin "2") (pinfunction "2_2") (pintype "passive"))
      (node (ref "RC_394") (pin "1") (pinfunction "1_1") (pintype "passive"))
      (node (ref "RC_394") (pin "2") (pinfunction "2_2") (pintype "passive"))
      (node (ref "RC_395") (pin "1") (pinfunction "1_1") (pintype "passive"))
      (node (ref "RC_395") (pin "2") (pinfunction "2_2") (pintype "passive"))
      (node (ref "RC_396") (pin "1") (pinfunction "1_1") (pintype "passive"))
      (node (ref "RC_396") (pin "2") (pinfunction "2_2") (pintype "passive"))
      (node (ref "RC_397") (pin "1") (pinfunction "1_1") (pintype "passive"))
      (node (ref "RC_397") (pin "2") (pinfunction "2_2") (pintype "passive"))
      (node (ref "RC_398") (pin "1") (pinfunction "1_1") (pintype "passive"))
      (node (ref "RC_398") (pin "2") (pinfunction "2_2") (pintype "passive"))
      (node (ref "RC_399") (pin "1") (pinfunction "1_1") (pintype "passive"))
      (node (ref "RC_399") (pin "2") (pinfunction "2_2") (pintype "passive"))
      (node (ref "RC_400") (pin "1") (pinfunction "1_1") (pintype "passive"))
      (node (ref "RC_400") (pin "2") (pinfunction "2_2") (pintype "passive"))
      (node (ref "RC_401") (pin "1") (pinfunction "1_1") (pintype "passive"))
      (node (ref "RC_401") (pin "2") (pinfunction "2_2") (pintype "passive"))
      (node (ref "RC_402") (pin "1") (pinfunction "1_1") (pintype "passive"))
      (node (ref "RC_402") (pin "2") (pinfunction "2_2") (pintype "passive"))
      (node (ref "RC_403") (pin "1") (pinfunction "1_1") (pintype "passive"))
      (node (ref "RC_403") (pin "2") (pinfunction "2_2") (pintype "passive"))
      (node (ref "RC_404") (pin "1") (pinfunction "1_1") (pintype "passive"))
      (node (ref "RC_404") (pin "2") (pinfunction "2_2") (pintype "passive"))
      (node (ref "RC_405") (pin "1") (pinfunction "1_1") (pintype "passive"))
      (node (ref "RC_405") (pin "2") (pinfunction "2_2") (pintype "passive"))
      (node (ref "RC_406") (pin "1") (pinfunction "1_1") (pintype "passive"))
      (node (ref "RC_406") (pin "2") (pinfunction "2_2") (pintype "passive"))
      (node (ref "RC_407") (pin "1") (pinfunction "1_1") (pintype "passive"))
      (node (ref "RC_407") (pin "2") (pinfunction "2_2") (pintype "passive"))
      (node (ref "RC_408") (pin "1") (pinfunction "1_1") (pintype "passive"))
      (node (ref "RC_408") (pin "2") (pinfunction "2_2") (pintype "passive"))
      (node (ref "RC_409") (pin "1") (pinfunction "1_1") (pintype "passive"))
      (node (ref "RC_409") (pin "2") (pinfunction "2_2") (pintype "passive"))
      (node (ref "RC_410") (pin "1") (pinfunction "1_1") (pintype "passive"))
      (node (ref "RC_410") (pin "2") (pinfunction "2_2") (pintype "passive"))
      (node (ref "RC_411") (pin "1") (pinfunction "1_1") (pintype "passive"))
      (node (ref "RC_411") (pin "2") (pinfunction "2_2") (pintype "passive"))
      (node (ref "RC_412") (pin "1") (pinfunction "1_1") (pintype "passive"))
      (node (ref "RC_412") (pin "2") (pinfunction "2_2") (pintype "passive"))
      (node (ref "RC_413") (pin "1") (pinfunction "1_1") (pintype "passive"))
      (node (ref "RC_413") (pin "2") (pinfunction "2_2") (pintype "passive"))
    )
    (net (code "13") (name "/BATT_12") (class "Default")
      (node (ref "JB10") (pin "4") (pinfunction "4_4") (pintype "passive"))
      (node (ref "JB16") (pin "1") (pinfunction "1_1") (pintype "passive"))
      (node (ref "JB4") (pin "1") (pinfunction "1_1") (pintype "passive"))
      (node (ref "JB4") (pin "2") (pinfunction "2_2") (pintype "passive"))
      (node (ref "JB4") (pin "3") (pinfunction "3_3") (pintype "passive"))
      (node (ref "JB4") (pin "4") (pinfunction "4_4") (pintype "passive"))
      (node (ref "JB5") (pin "1") (pinfunction "1_1") (pintype "passive"))
      (node (ref "JB5") (pin "2") (pinfunction "2_2") (pintype "passive"))
      (node (ref "JB5") (pin "3") (pinfunction "3_3") (pintype "passive"))
      (node (ref "JB5") (pin "4") (pinfunction "4_4") (pintype "passive"))
      (node (ref "JB6") (pin "1") (pinfunction "1_1") (pintype "passive"))
      (node (ref "JB6") (pin "2") (pinfunction "2_2") (pintype "passive"))
      (node (ref "JB6") (pin "3") (pinfunction "3_3") (pintype "passive"))
      (node (ref "JB6") (pin "4") (pinfunction "4_4") (pintype "passive"))
      (node (ref "RC_414") (pin "1") (pinfunction "1_1") (pintype "passive"))
      (node (ref "RC_414") (pin "2") (pinfunction "2_2") (pintype "passive"))
      (node (ref "RC_415") (pin "1") (pinfunction "1_1") (pintype "passive"))
      (node (ref "RC_415") (pin "2") (pinfunction "2_2") (pintype "passive"))
      (node (ref "RC_416") (pin "1") (pinfunction "1_1") (pintype "passive"))
      (node (ref "RC_416") (pin "2") (pinfunction "2_2") (pintype "passive"))
      (node (ref "RC_417") (pin "1") (pinfunction "1_1") (pintype "passive"))
      (node (ref "RC_417") (pin "2") (pinfunction "2_2") (pintype "passive"))
      (node (ref "RC_418") (pin "1") (pinfunction "1_1") (pintype "passive"))
      (node (ref "RC_418") (pin "2") (pinfunction "2_2") (pintype "passive"))
      (node (ref "RC_419") (pin "1") (pinfunction "1_1") (pintype "passive"))
      (node (ref "RC_419") (pin "2") (pinfunction "2_2") (pintype "passive"))
      (node (ref "RC_420") (pin "1") (pinfunction "1_1") (pintype "passive"))
      (node (ref "RC_420") (pin "2") (pinfunction "2_2") (pintype "passive"))
      (node (ref "RC_421") (pin "1") (pinfunction "1_1") (pintype "passive"))
      (node (ref "RC_421") (pin "2") (pinfunction "2_2") (pintype "passive"))
      (node (ref "RC_422") (pin "1") (pinfunction "1_1") (pintype "passive"))
      (node (ref "RC_422") (pin "2") (pinfunction "2_2") (pintype "passive"))
      (node (ref "RC_423") (pin "1") (pinfunction "1_1") (pintype "passive"))
      (node (ref "RC_423") (pin "2") (pinfunction "2_2") (pintype "passive"))
      (node (ref "RC_424") (pin "1") (pinfunction "1_1") (pintype "passive"))
      (node (ref "RC_424") (pin "2") (pinfunction "2_2") (pintype "passive"))
      (node (ref "RC_425") (pin "1") (pinfunction "1_1") (pintype "passive"))
      (node (ref "RC_425") (pin "2") (pinfunction "2_2") (pintype "passive"))
      (node (ref "RC_426") (pin "1") (pinfunction "1_1") (pintype "passive"))
      (node (ref "RC_426") (pin "2") (pinfunction "2_2") (pintype "passive"))
      (node (ref "RC_427") (pin "1") (pinfunction "1_1") (pintype "passive"))
      (node (ref "RC_427") (pin "2") (pinfunction "2_2") (pintype "passive"))
      (node (ref "RC_428") (pin "1") (pinfunction "1_1") (pintype "passive"))
      (node (ref "RC_428") (pin "2") (pinfunction "2_2") (pintype "passive"))
      (node (ref "RC_429") (pin "1") (pinfunction "1_1") (pintype "passive"))
      (node (ref "RC_429") (pin "2") (pinfunction "2_2") (pintype "passive"))
      (node (ref "RC_430") (pin "1") (pinfunction "1_1") (pintype "passive"))
      (node (ref "RC_430") (pin "2") (pinfunction "2_2") (pintype "passive"))
      (node (ref "RC_431") (pin "1") (pinfunction "1_1") (pintype "passive"))
      (node (ref "RC_431") (pin "2") (pinfunction "2_2") (pintype "passive"))
    )
    (net (code "14") (name "/C4") (class "Default")
      (node (ref "JB14") (pin "4") (pinfunction "4_4") (pintype "passive"))
      (node (ref "JB8") (pin "1") (pinfunction "1_1") (pintype "passive"))
      (node (ref "NT_3_4") (pin "1") (pinfunction "1_1") (pintype "passive"))
    )
    (net (code "15") (name "/C9") (class "Default")
      (node (ref "JB15") (pin "3") (pinfunction "3_3") (pintype "passive"))
      (node (ref "JB9") (pin "2") (pinfunction "2_2") (pintype "passive"))
      (node (ref "NT_8_9") (pin "2") (pinfunction "2_2") (pintype "passive"))
    )
    (net (code "16") (name "/C13") (class "Default")
      (node (ref "JB10") (pin "2") (pinfunction "2_2") (pintype "passive"))
      (node (ref "JB16") (pin "3") (pinfunction "3_3") (pintype "passive"))
      (node (ref "NT_13_14") (pin "1") (pinfunction "1_1") (pintype "passive"))
      (node (ref "NT_13_14_2") (pin "1") (pinfunction "1_1") (pintype "passive"))
    )
    (net (code "17") (name "/TS_0") (class "Default")
      (node (ref "JB11") (pin "2") (pinfunction "2_2") (pintype "passive"))
      (node (ref "JB17") (pin "3") (pinfunction "3_3") (pintype "passive"))
      (node (ref "TSB_1") (pin "1") (pinfunction "1_1") (pintype "passive"))
      (node (ref "TSB_1-2") (pin "2") (pinfunction "2_2") (pintype "passive"))
    )
    (net (code "18") (name "/TS_1") (class "Default")
      (node (ref "JB11") (pin "3") (pinfunction "3_3") (pintype "passive"))
      (node (ref "JB17") (pin "2") (pinfunction "2_2") (pintype "passive"))
      (node (ref "TSB_2_3") (pin "2") (pinfunction "2_2") (pintype "passive"))
      (node (ref "TSB_3-4") (pin "2") (pinfunction "2_2") (pintype "passive"))
    )
    (net (code "19") (name "/TS_2") (class "Default")
      (node (ref "JB11") (pin "4") (pinfunction "4_4") (pintype "passive"))
      (node (ref "JB17") (pin "1") (pinfunction "1_1") (pintype "passive"))
      (node (ref "TSB_4_5") (pin "2") (pinfunction "2_2") (pintype "passive"))
      (node (ref "TSB_5-6") (pin "2") (pinfunction "2_2") (pintype "passive"))
    )
    (net (code "20") (name "/TS_3") (class "Default")
      (node (ref "JB12") (pin "1") (pinfunction "1_1") (pintype "passive"))
      (node (ref "JB18") (pin "4") (pinfunction "4_4") (pintype "passive"))
      (node (ref "TSB_6_7") (pin "2") (pinfunction "2_2") (pintype "passive"))
      (node (ref "TSB_7-8") (pin "2") (pinfunction "2_2") (pintype "passive"))
    )
    (net (code "21") (name "/TS_4") (class "Default")
      (node (ref "JB12") (pin "2") (pinfunction "2_2") (pintype "passive"))
      (node (ref "JB18") (pin "3") (pinfunction "3_3") (pintype "passive"))
      (node (ref "TSB_8_9") (pin "2") (pinfunction "2_2") (pintype "passive"))
      (node (ref "TSB_9-10") (pin "2") (pinfunction "2_2") (pintype "passive"))
    )
    (net (code "22") (name "/TS_5") (class "Default")
      (node (ref "JB12") (pin "3") (pinfunction "3_3") (pintype "passive"))
      (node (ref "JB18") (pin "2") (pinfunction "2_2") (pintype "passive"))
      (node (ref "TSB_10_11") (pin "2") (pinfunction "2_2") (pintype "passive"))
      (node (ref "TSB_11-12") (pin "2") (pinfunction "2_2") (pintype "passive"))
    )
    (net (code "23") (name "/TS_6") (class "Default")
      (node (ref "JB12") (pin "4") (pinfunction "4_4") (pintype "passive"))
      (node (ref "JB18") (pin "1") (pinfunction "1_1") (pintype "passive"))
      (node (ref "TSB_12") (pin "1") (pinfunction "1_1") (pintype "passive"))
    )
    (net (code "24") (name "/TS_A_GND") (class "Default")
      (node (ref "JB17") (pin "4") (pinfunction "4_4") (pintype "passive"))
      (node (ref "TSB_1-2") (pin "1") (pinfunction "1_1") (pintype "passive"))
      (node (ref "TSB_11-12") (pin "1") (pinfunction "1_1") (pintype "passive"))
      (node (ref "TSB_3-4") (pin "1") (pinfunction "1_1") (pintype "passive"))
      (node (ref "TSB_5-6") (pin "1") (pinfunction "1_1") (pintype "passive"))
      (node (ref "TSB_7-8") (pin "1") (pinfunction "1_1") (pintype "passive"))
      (node (ref "TSB_9-10") (pin "1") (pinfunction "1_1") (pintype "passive"))
    )
    (net (code "25") (name "/TS_B_GND") (class "Default")
      (node (ref "JB11") (pin "1") (pinfunction "1_1") (pintype "passive"))
      (node (ref "TSB_1") (pin "2") (pinfunction "2_2") (pintype "passive"))
      (node (ref "TSB_10_11") (pin "1") (pinfunction "1_1") (pintype "passive"))
      (node (ref "TSB_12") (pin "2") (pinfunction "2_2") (pintype "passive"))
      (node (ref "TSB_2_3") (pin "1") (pinfunction "1_1") (pintype "passive"))
      (node (ref "TSB_4_5") (pin "1") (pinfunction "1_1") (pintype "passive"))
      (node (ref "TSB_6_7") (pin "1") (pinfunction "1_1") (pintype "passive"))
      (node (ref "TSB_8_9") (pin "1") (pinfunction "1_1") (pintype "passive"))
    )
  )
)
